# robot_PI4_F28379D_v1.net
KiCad netlist of a schematic drawn in EAGLE
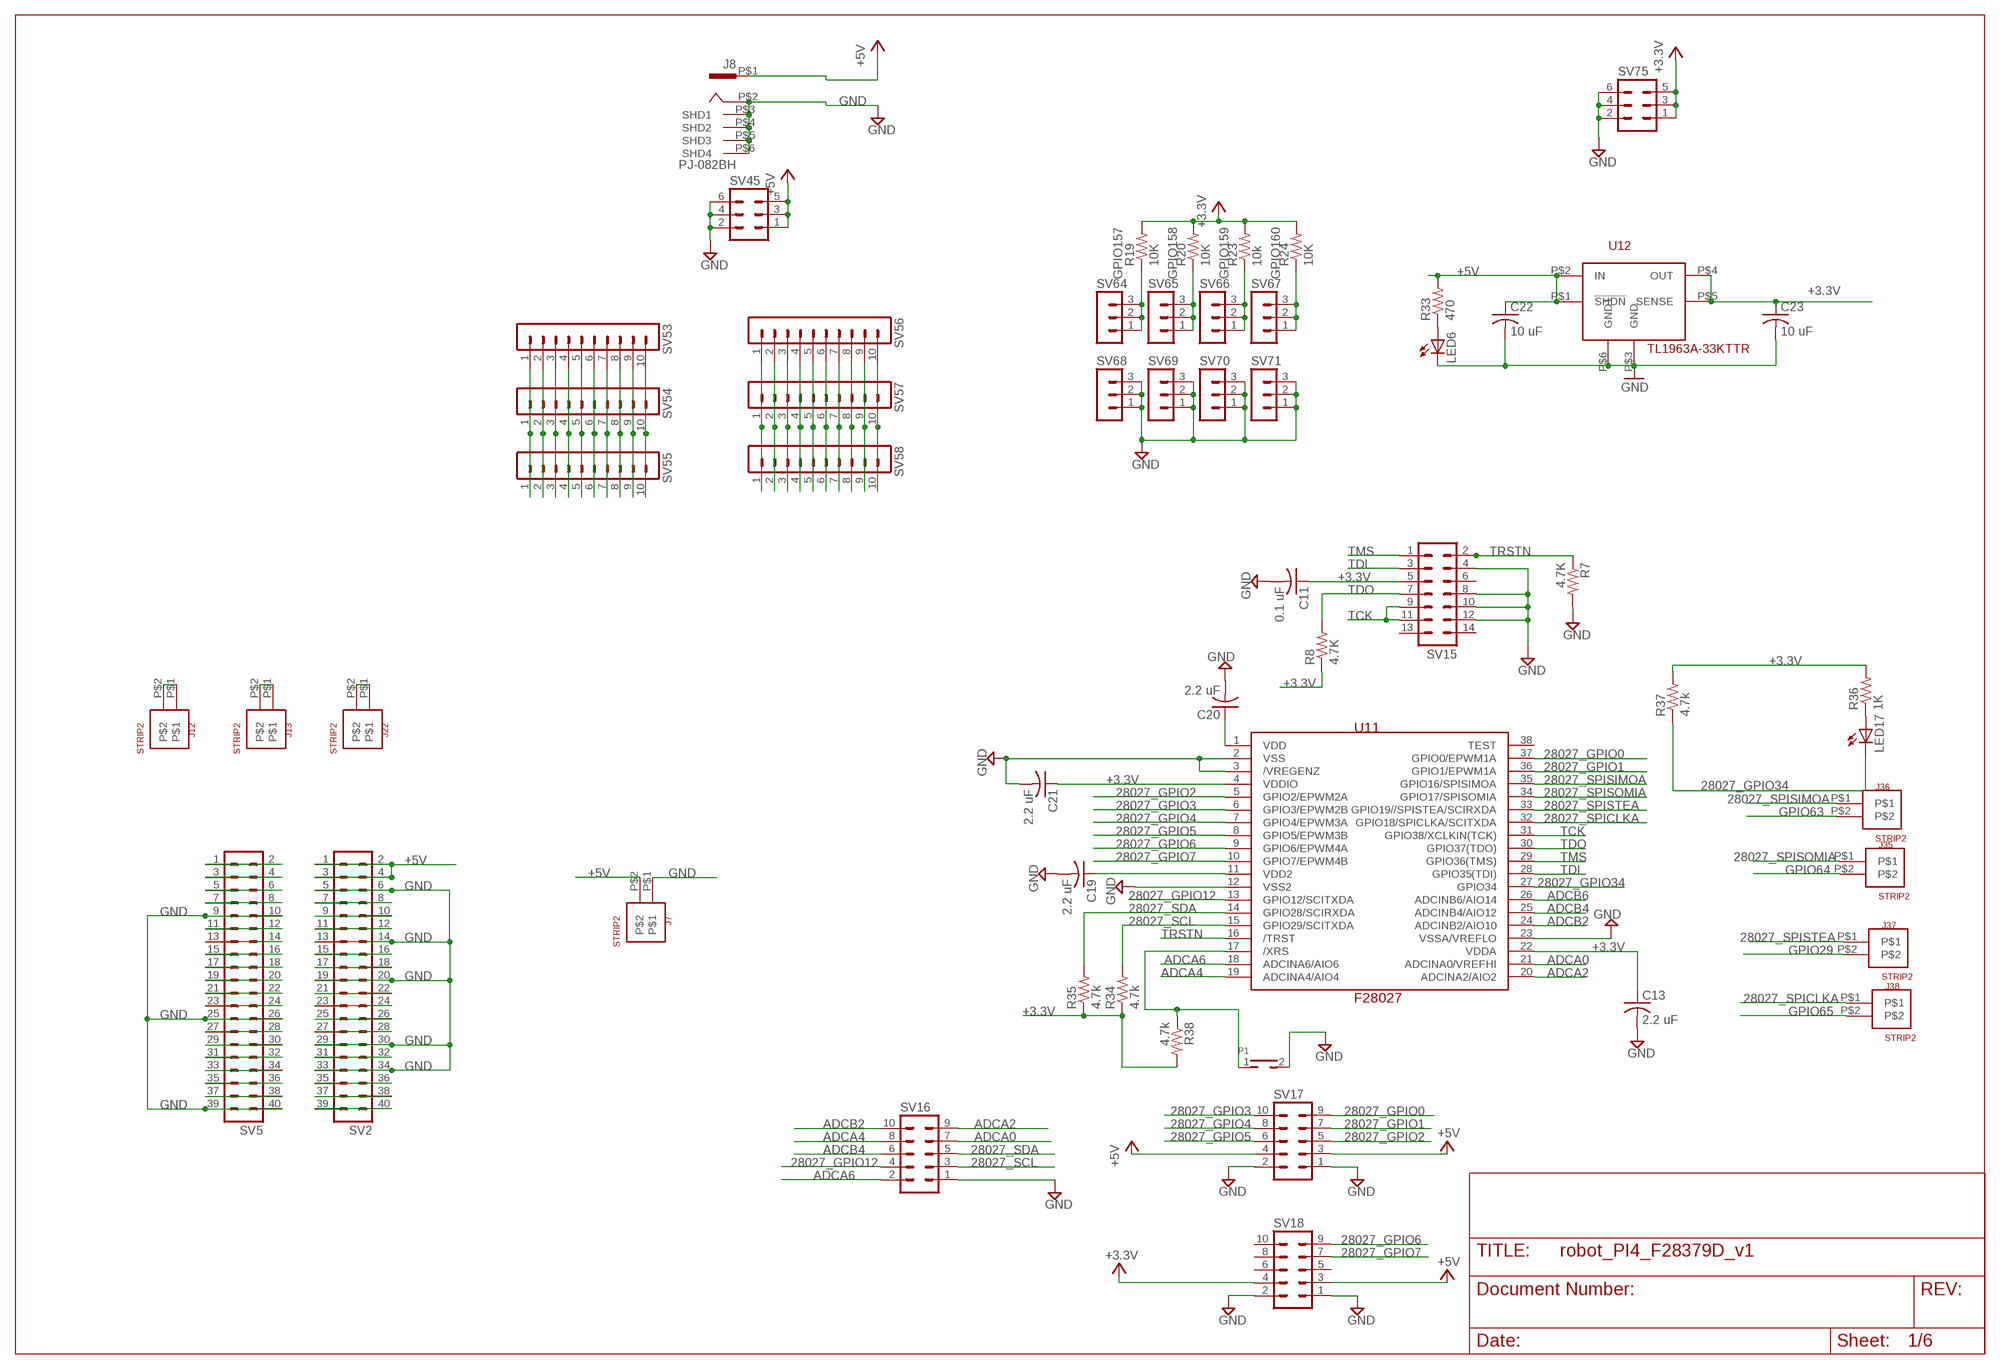
[diagram p0: schematic, sheet 1]
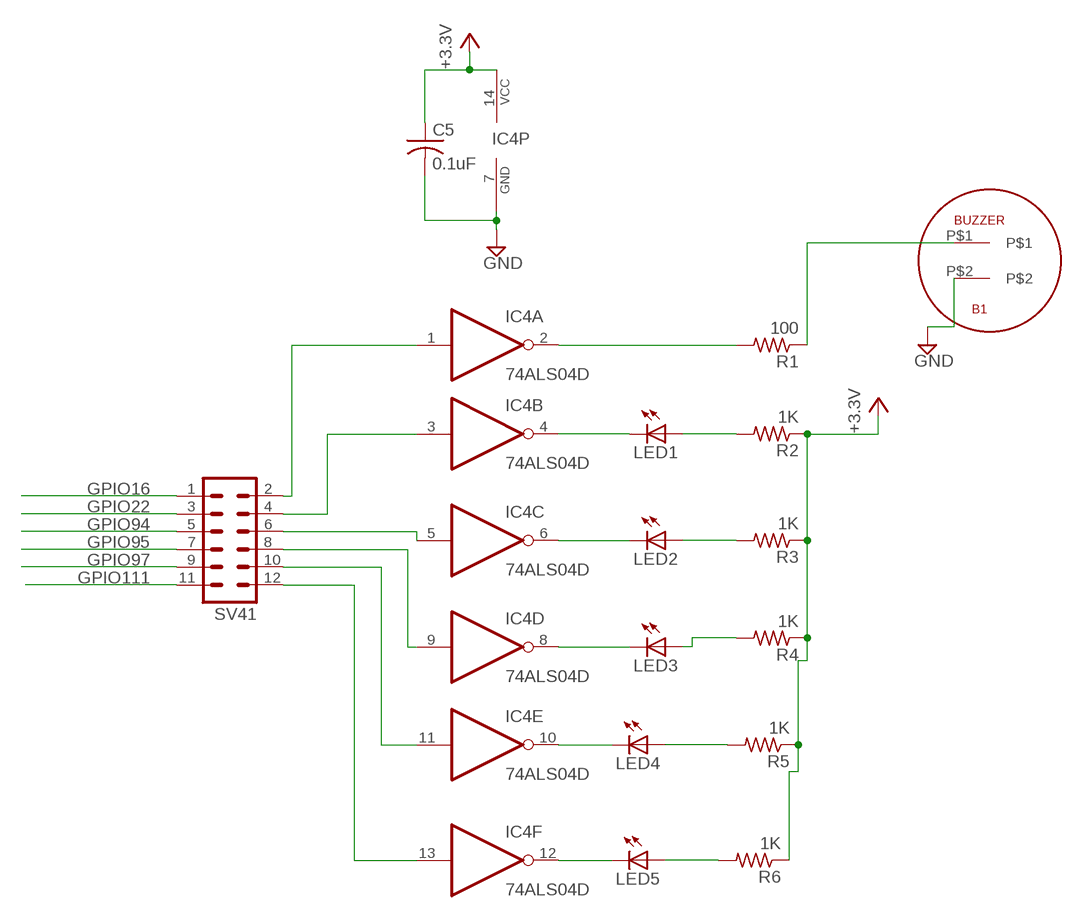
[diagram p1: schematic, sheet 2]
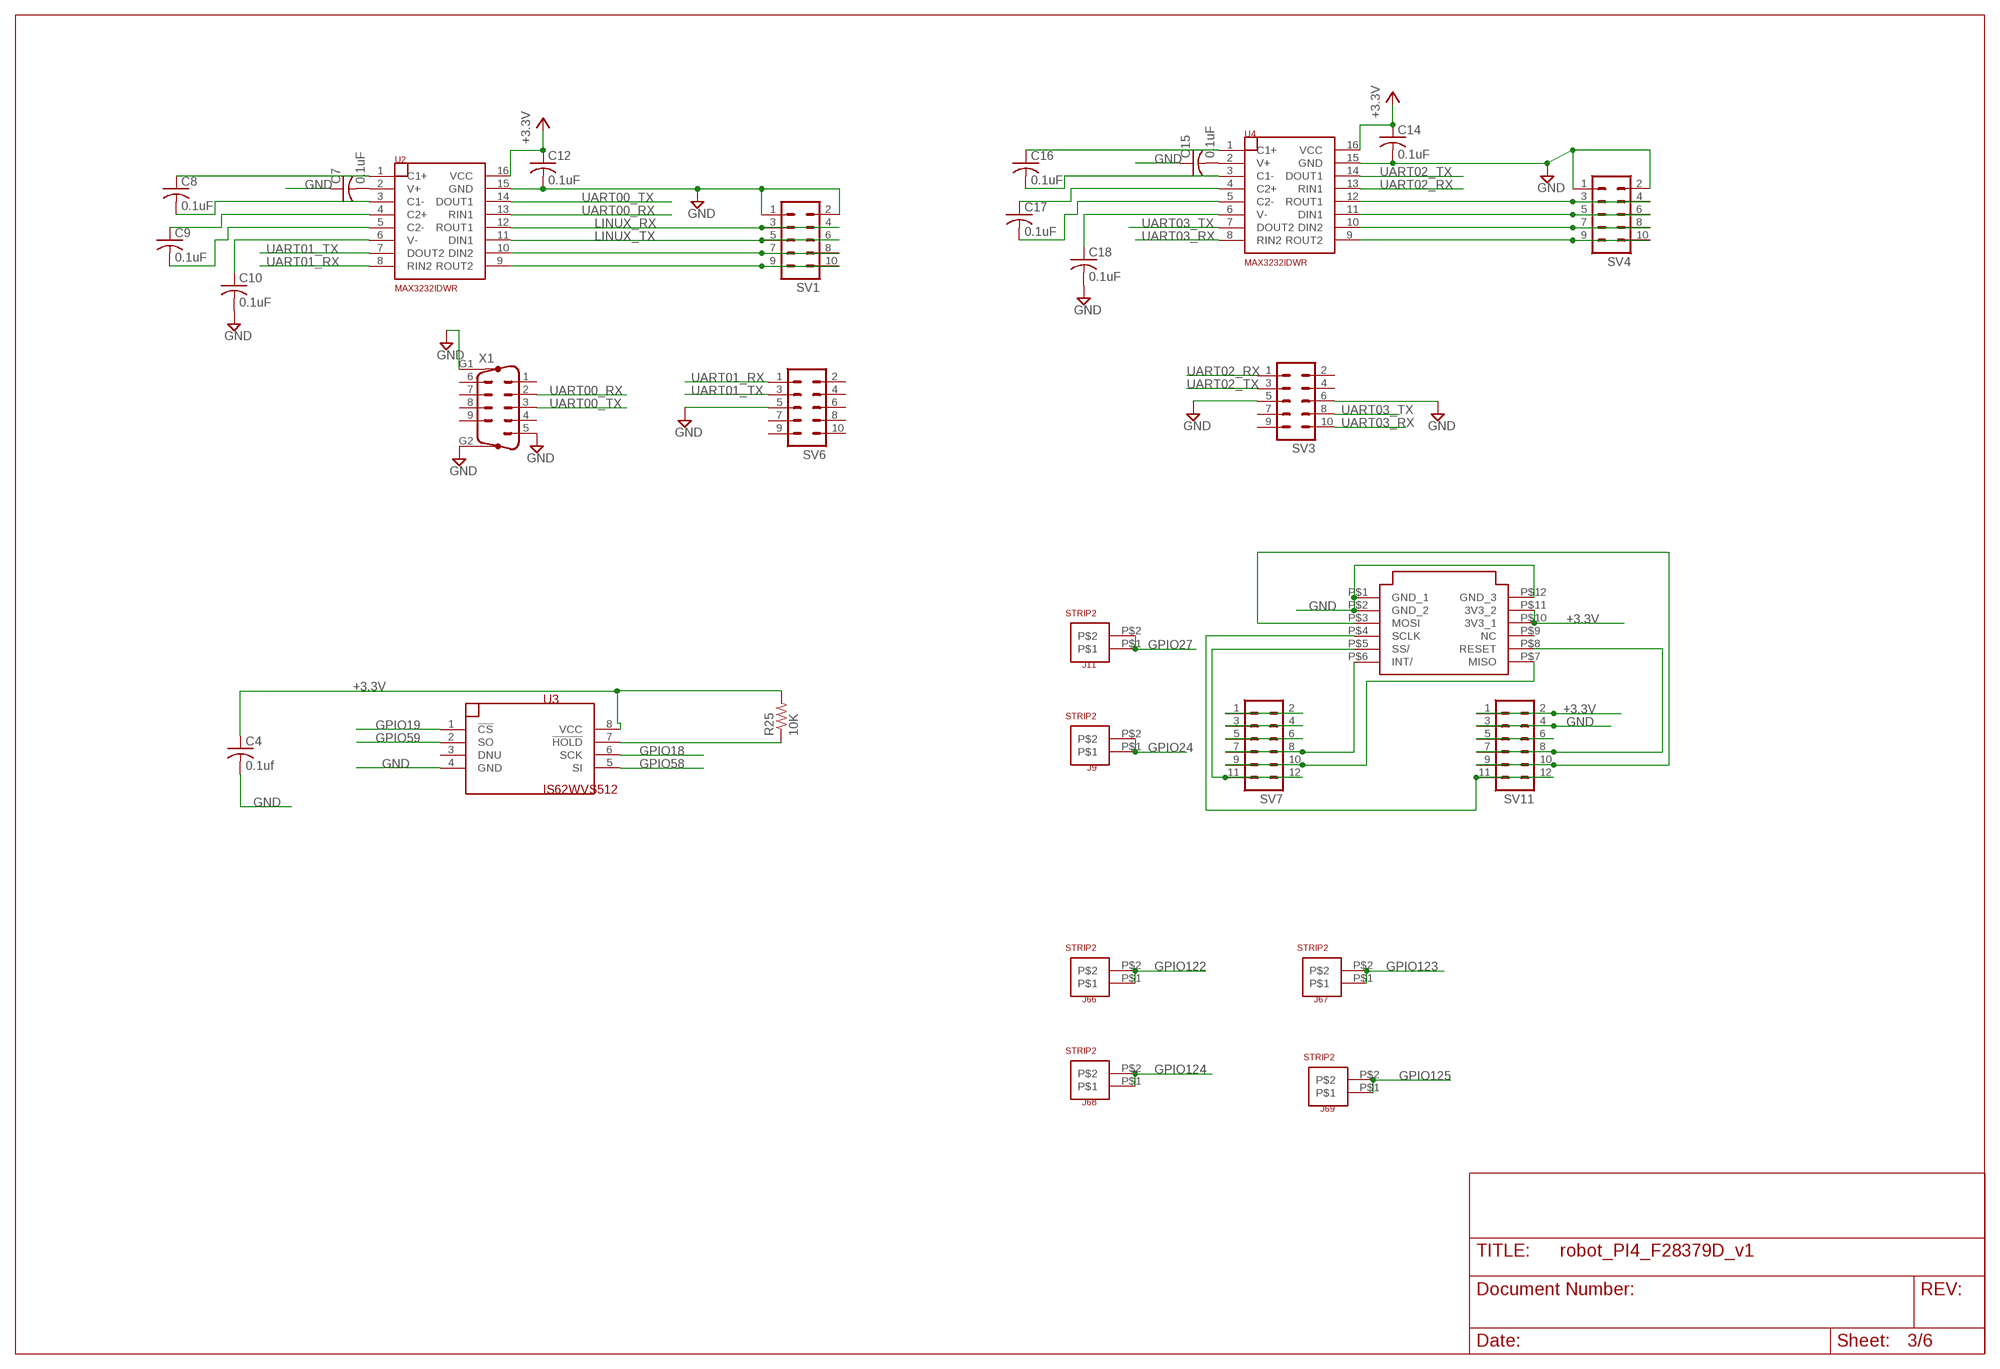
[diagram p2: schematic, sheet 3]
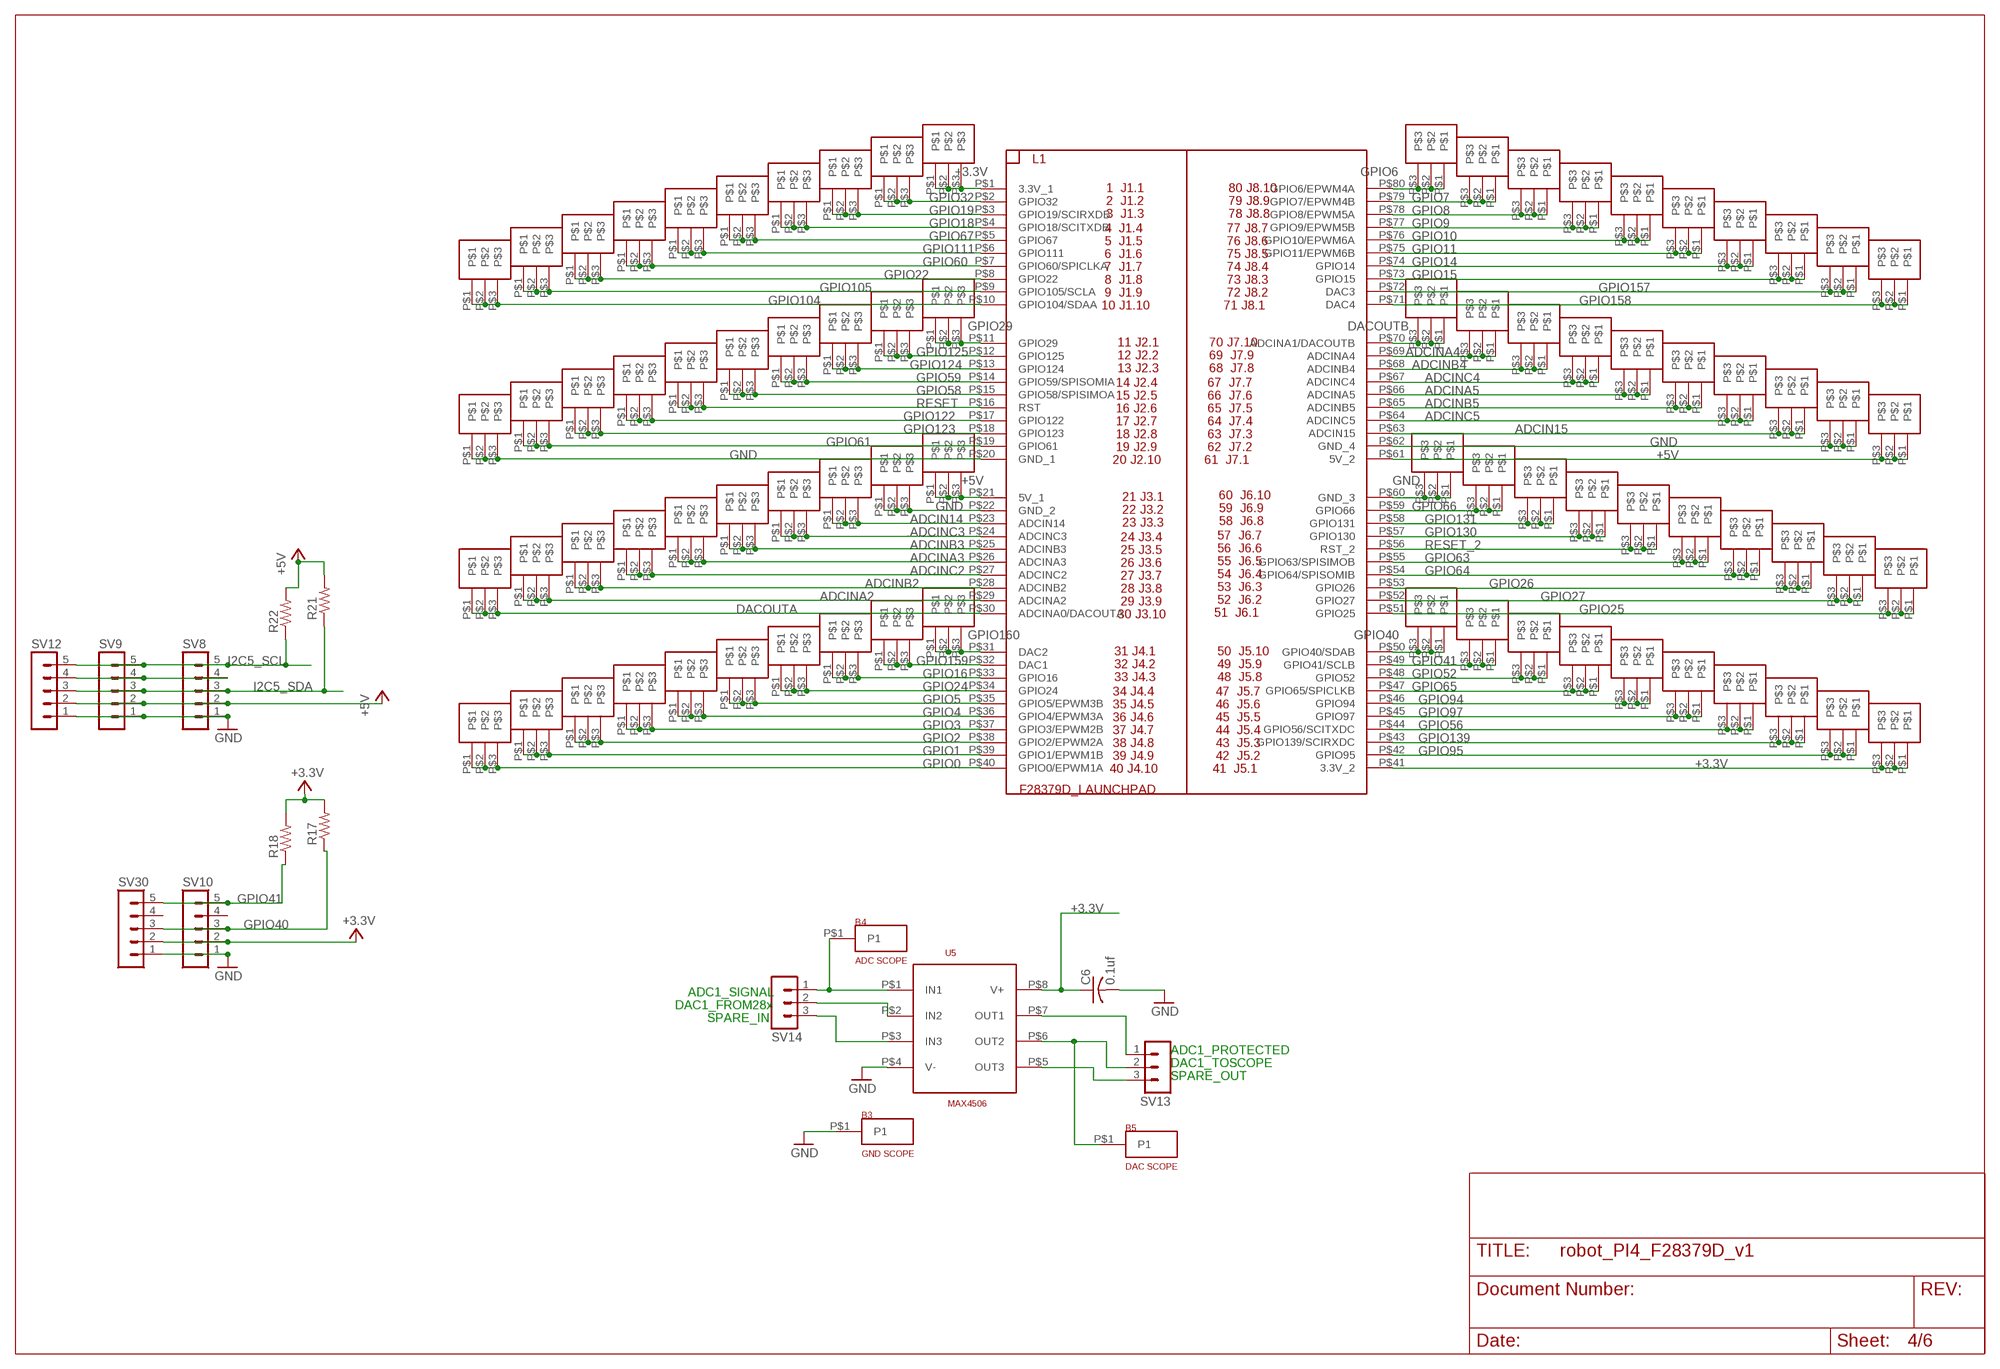
[diagram p3: schematic, sheet 4]
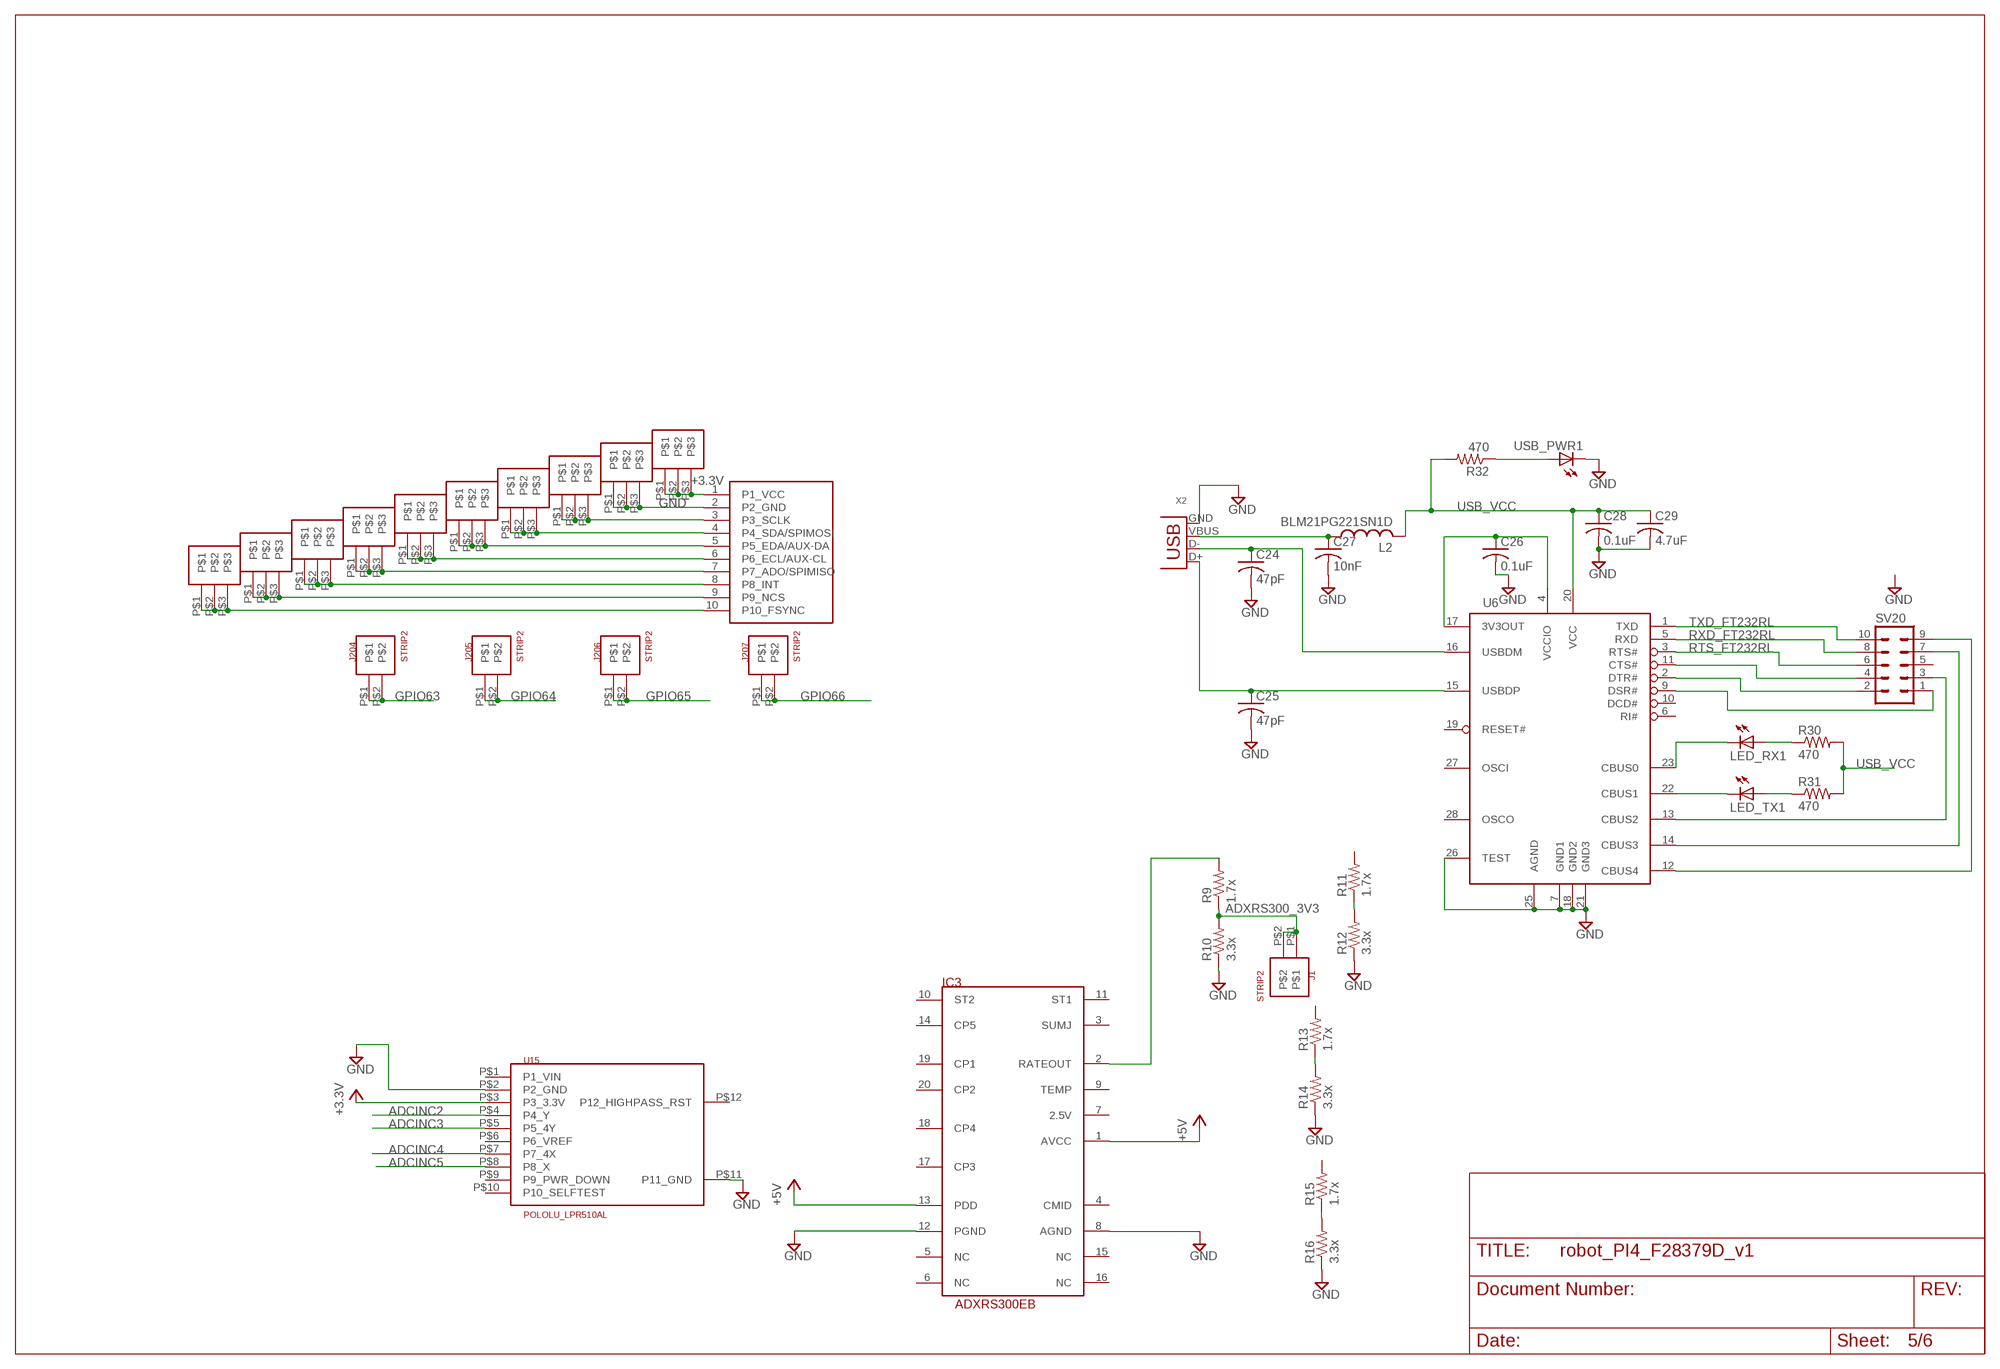
[diagram p4: schematic, sheet 5]
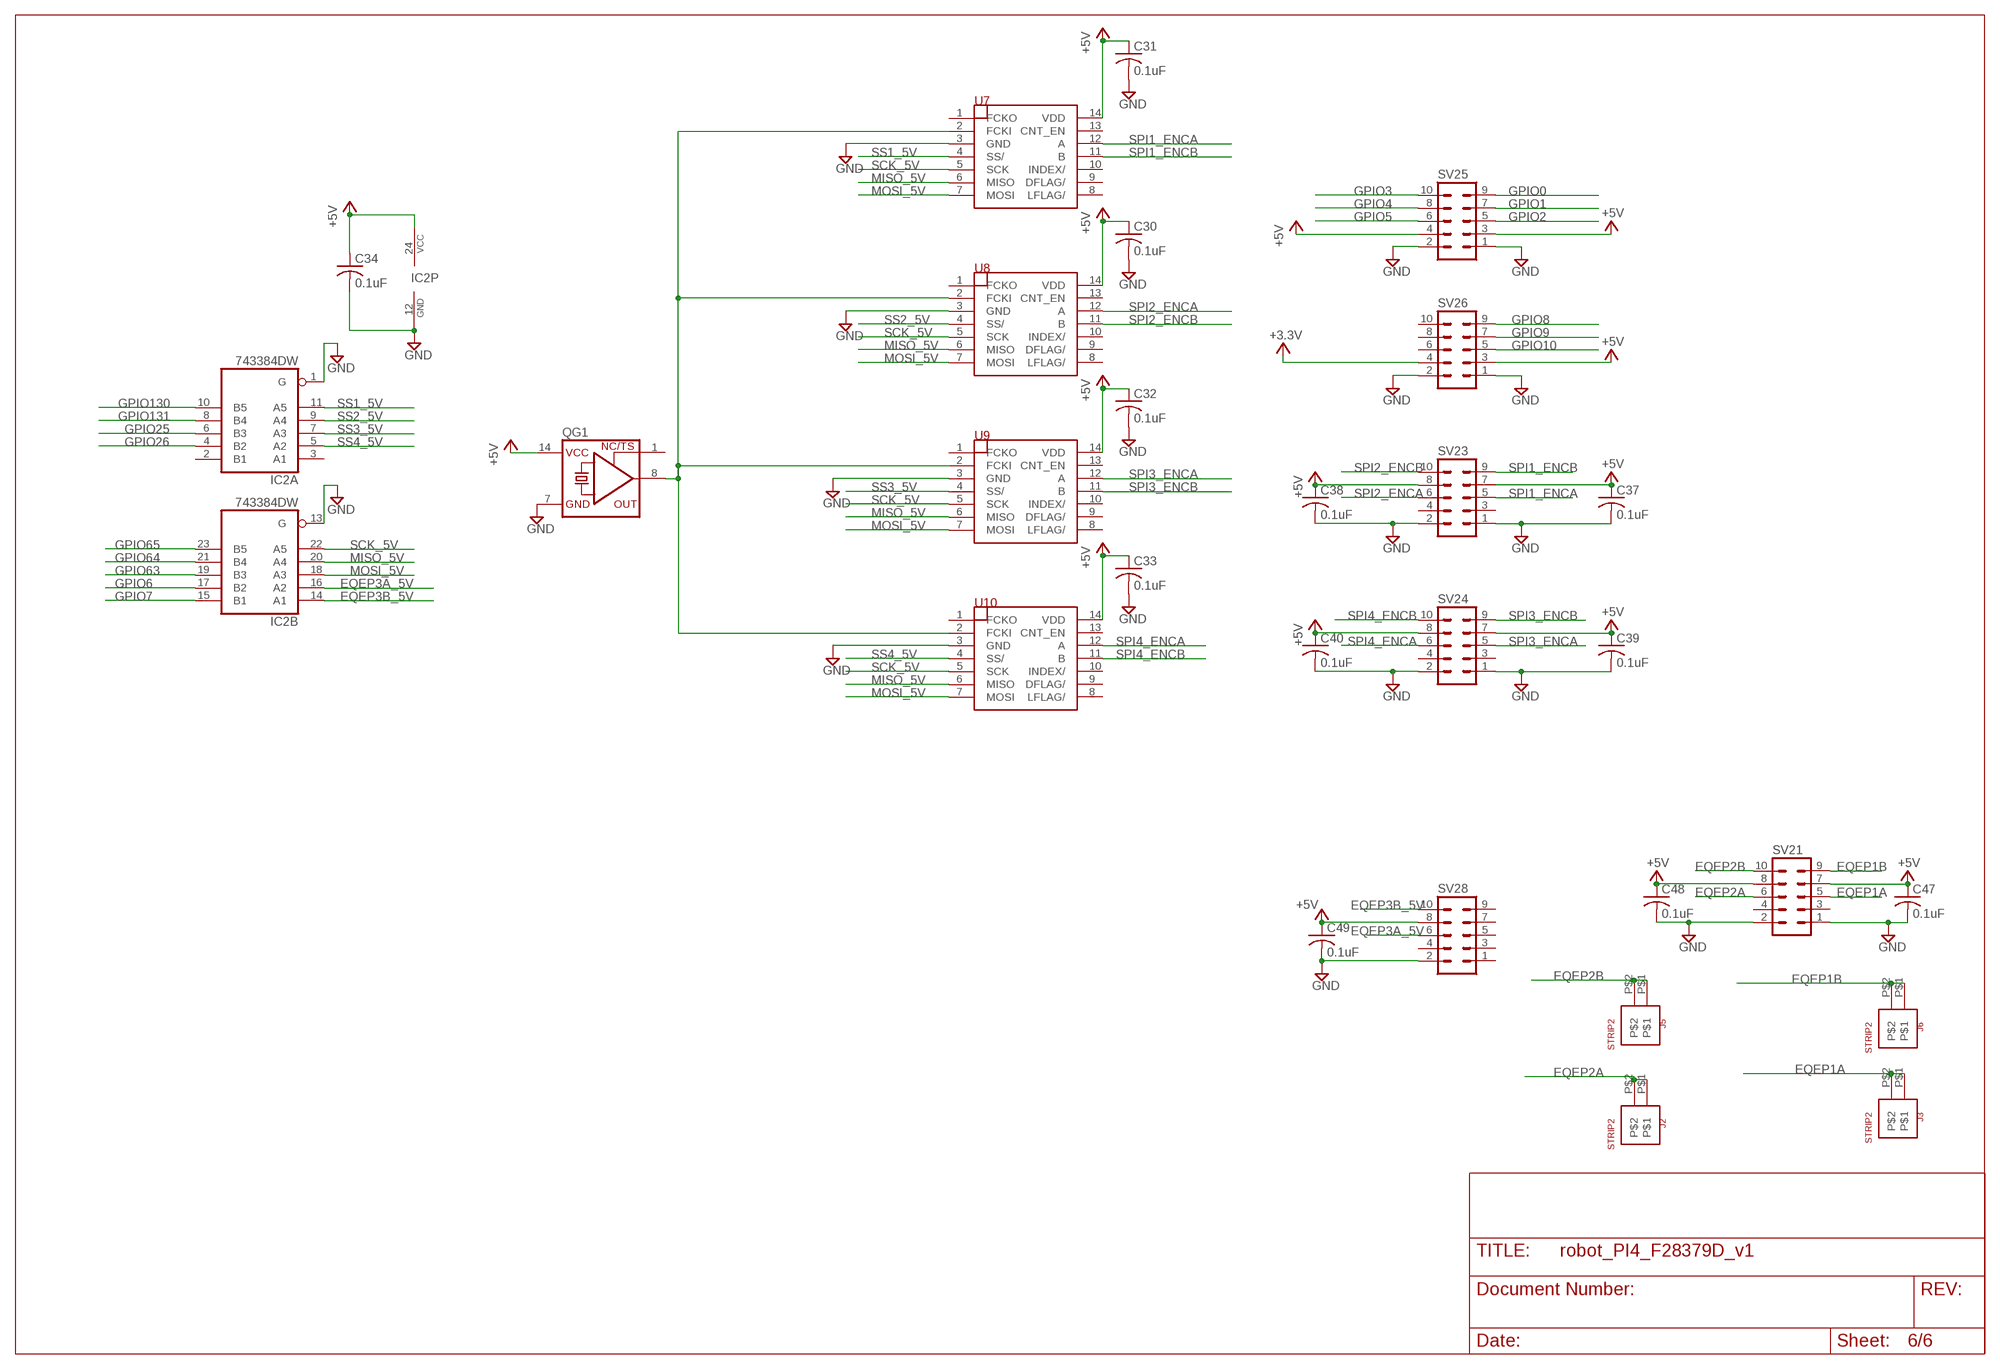
[diagram p5: schematic, sheet 6]

(export (version "E")
  (design (tool "Eeschema 10.0.6"))
  (components
    (comp (ref "C4")
      (value "0.1uf")
      (footprint "eagle-import:C1206")
      (libsource (lib "eagle-import") (part "C-USC1206"))
    )
    (comp (ref "C7")
      (value "0.1uF")
      (footprint "eagle-import:C0805K")
      (libsource (lib "eagle-import") (part "C-USC0805K"))
    )
    (comp (ref "C8")
      (value "0.1uF")
      (footprint "eagle-import:C0805K")
      (libsource (lib "eagle-import") (part "C-USC0805K"))
    )
    (comp (ref "C9")
      (value "0.1uF")
      (footprint "eagle-import:C0805K")
      (libsource (lib "eagle-import") (part "C-USC0805K"))
    )
    (comp (ref "C10")
      (value "0.1uF")
      (footprint "eagle-import:C0805K")
      (libsource (lib "eagle-import") (part "C-USC0805K"))
    )
    (comp (ref "C12")
      (value "0.1uF")
      (footprint "eagle-import:C0805K")
      (libsource (lib "eagle-import") (part "C-USC0805K"))
    )
    (comp (ref "C14")
      (value "0.1uF")
      (footprint "eagle-import:C0805K")
      (libsource (lib "eagle-import") (part "C-USC0805K"))
    )
    (comp (ref "C15")
      (value "0.1uF")
      (footprint "eagle-import:C0805K")
      (libsource (lib "eagle-import") (part "C-USC0805K"))
    )
    (comp (ref "C16")
      (value "0.1uF")
      (footprint "eagle-import:C0805K")
      (libsource (lib "eagle-import") (part "C-USC0805K"))
    )
    (comp (ref "C17")
      (value "0.1uF")
      (footprint "eagle-import:C0805K")
      (libsource (lib "eagle-import") (part "C-USC0805K"))
    )
    (comp (ref "C18")
      (value "0.1uF")
      (footprint "eagle-import:C0805K")
      (libsource (lib "eagle-import") (part "C-USC0805K"))
    )
    (comp (ref "ETH1")
      (value "USR_ES1_W5500")
      (footprint "eagle-import:USR_ES1_W5500")
      (libsource (lib "eagle-import") (part "USR_ES1_W5500"))
    )
    (comp (ref "J9")
      (value "STRIP2")
      (footprint "eagle-import:STRIP2")
      (libsource (lib "eagle-import") (part "STRIP2"))
    )
    (comp (ref "J11")
      (value "STRIP2")
      (footprint "eagle-import:STRIP2")
      (libsource (lib "eagle-import") (part "STRIP2"))
    )
    (comp (ref "J66")
      (value "STRIP2")
      (footprint "eagle-import:STRIP2")
      (libsource (lib "eagle-import") (part "STRIP2"))
    )
    (comp (ref "J67")
      (value "STRIP2")
      (footprint "eagle-import:STRIP2")
      (libsource (lib "eagle-import") (part "STRIP2"))
    )
    (comp (ref "J68")
      (value "STRIP2")
      (footprint "eagle-import:STRIP2")
      (libsource (lib "eagle-import") (part "STRIP2"))
    )
    (comp (ref "J69")
      (value "STRIP2")
      (footprint "eagle-import:STRIP2")
      (libsource (lib "eagle-import") (part "STRIP2"))
    )
    (comp (ref "R25")
      (value "10K")
      (footprint "eagle-import:M1206")
      (libsource (lib "eagle-import") (part "R-US_M1206"))
    )
    (comp (ref "SV1")
      (value "MA05-2")
      (footprint "eagle-import:MA05-2")
      (libsource (lib "eagle-import") (part "MA05-2"))
    )
    (comp (ref "SV3")
      (value "MA05-2")
      (footprint "eagle-import:MA05-2")
      (libsource (lib "eagle-import") (part "MA05-2"))
    )
    (comp (ref "SV4")
      (value "MA05-2")
      (footprint "eagle-import:MA05-2")
      (libsource (lib "eagle-import") (part "MA05-2"))
    )
    (comp (ref "SV6")
      (value "MA05-2")
      (footprint "eagle-import:MA05-2")
      (libsource (lib "eagle-import") (part "MA05-2"))
    )
    (comp (ref "SV7")
      (value "MA06-2")
      (footprint "eagle-import:MA06-2")
      (libsource (lib "eagle-import") (part "MA06-2"))
    )
    (comp (ref "SV11")
      (value "MA06-2")
      (footprint "eagle-import:MA06-2")
      (libsource (lib "eagle-import") (part "MA06-2"))
    )
    (comp (ref "U2")
      (value "MAX3232IDWR")
      (footprint "eagle-import:SO16W")
      (libsource (lib "eagle-import") (part "MAX3232IDWR"))
    )
    (comp (ref "U3")
      (value "IS62WVS512")
      (footprint "eagle-import:SO08")
      (libsource (lib "eagle-import") (part "IS62WVS512"))
    )
    (comp (ref "U4")
      (value "MAX3232IDWR")
      (footprint "eagle-import:SO16W")
      (libsource (lib "eagle-import") (part "MAX3232IDWR"))
    )
    (comp (ref "X1")
      (value "M09HP")
      (footprint "eagle-import:M09HP")
      (libsource (lib "eagle-import") (part "M09HP"))
    )
    (comp (ref "C24")
      (value "47pF")
      (footprint "eagle-import:C1206")
      (libsource (lib "eagle-import") (part "C-USC1206"))
    )
    (comp (ref "C25")
      (value "47pF")
      (footprint "eagle-import:C1206")
      (libsource (lib "eagle-import") (part "C-USC1206"))
    )
    (comp (ref "C26")
      (value "0.1uF")
      (footprint "eagle-import:C1206")
      (libsource (lib "eagle-import") (part "C-USC1206"))
    )
    (comp (ref "C27")
      (value "10nF")
      (footprint "eagle-import:C1206")
      (libsource (lib "eagle-import") (part "C-USC1206"))
    )
    (comp (ref "C28")
      (value "0.1uF")
      (footprint "eagle-import:C1206")
      (libsource (lib "eagle-import") (part "C-USC1206"))
    )
    (comp (ref "C29")
      (value "4.7uF")
      (footprint "eagle-import:C1206")
      (libsource (lib "eagle-import") (part "C-USC1206"))
    )
    (comp (ref "IC3")
      (value "ADXRS300EB")
      (footprint "eagle-import:DIL20")
      (libsource (lib "eagle-import") (part "ADXRS300EB"))
    )
    (comp (ref "J1")
      (value "STRIP2")
      (footprint "eagle-import:STRIP2")
      (libsource (lib "eagle-import") (part "STRIP2"))
    )
    (comp (ref "J123")
      (value "STRIP3")
      (footprint "eagle-import:STRIP3")
      (libsource (lib "eagle-import") (part "STRIP3"))
    )
    (comp (ref "J124")
      (value "STRIP3")
      (footprint "eagle-import:STRIP3")
      (libsource (lib "eagle-import") (part "STRIP3"))
    )
    (comp (ref "J125")
      (value "STRIP3")
      (footprint "eagle-import:STRIP3")
      (libsource (lib "eagle-import") (part "STRIP3"))
    )
    (comp (ref "J126")
      (value "STRIP3")
      (footprint "eagle-import:STRIP3")
      (libsource (lib "eagle-import") (part "STRIP3"))
    )
    (comp (ref "J127")
      (value "STRIP3")
      (footprint "eagle-import:STRIP3")
      (libsource (lib "eagle-import") (part "STRIP3"))
    )
    (comp (ref "J128")
      (value "STRIP3")
      (footprint "eagle-import:STRIP3")
      (libsource (lib "eagle-import") (part "STRIP3"))
    )
    (comp (ref "J129")
      (value "STRIP3")
      (footprint "eagle-import:STRIP3")
      (libsource (lib "eagle-import") (part "STRIP3"))
    )
    (comp (ref "J130")
      (value "STRIP3")
      (footprint "eagle-import:STRIP3")
      (libsource (lib "eagle-import") (part "STRIP3"))
    )
    (comp (ref "J131")
      (value "STRIP3")
      (footprint "eagle-import:STRIP3")
      (libsource (lib "eagle-import") (part "STRIP3"))
    )
    (comp (ref "J132")
      (value "STRIP3")
      (footprint "eagle-import:STRIP3")
      (libsource (lib "eagle-import") (part "STRIP3"))
    )
    (comp (ref "J204")
      (value "STRIP2")
      (footprint "eagle-import:STRIP2")
      (libsource (lib "eagle-import") (part "STRIP2"))
    )
    (comp (ref "J205")
      (value "STRIP2")
      (footprint "eagle-import:STRIP2")
      (libsource (lib "eagle-import") (part "STRIP2"))
    )
    (comp (ref "J206")
      (value "STRIP2")
      (footprint "eagle-import:STRIP2")
      (libsource (lib "eagle-import") (part "STRIP2"))
    )
    (comp (ref "J207")
      (value "STRIP2")
      (footprint "eagle-import:STRIP2")
      (libsource (lib "eagle-import") (part "STRIP2"))
    )
    (comp (ref "L2")
      (value "BLM21PG221SN1D")
      (footprint "eagle-import:L0805")
      (libsource (lib "eagle-import") (part "L-USL0805"))
    )
    (comp (ref "LED_RX1")
      (value "LED3MM")
      (footprint "eagle-import:LED3MM")
      (libsource (lib "eagle-import") (part "LED3MM"))
    )
    (comp (ref "LED_TX1")
      (value "LED3MM")
      (footprint "eagle-import:LED3MM")
      (libsource (lib "eagle-import") (part "LED3MM"))
    )
    (comp (ref "R9")
      (value "1.7x")
      (footprint "eagle-import:M1206")
      (libsource (lib "eagle-import") (part "R-US_M1206"))
    )
    (comp (ref "R10")
      (value "3.3x")
      (footprint "eagle-import:M1206")
      (libsource (lib "eagle-import") (part "R-US_M1206"))
    )
    (comp (ref "R11")
      (value "1.7x")
      (footprint "eagle-import:M1206")
      (libsource (lib "eagle-import") (part "R-US_M1206"))
    )
    (comp (ref "R12")
      (value "3.3x")
      (footprint "eagle-import:M1206")
      (libsource (lib "eagle-import") (part "R-US_M1206"))
    )
    (comp (ref "R13")
      (value "1.7x")
      (footprint "eagle-import:M1206")
      (libsource (lib "eagle-import") (part "R-US_M1206"))
    )
    (comp (ref "R14")
      (value "3.3x")
      (footprint "eagle-import:M1206")
      (libsource (lib "eagle-import") (part "R-US_M1206"))
    )
    (comp (ref "R15")
      (value "1.7x")
      (footprint "eagle-import:M1206")
      (libsource (lib "eagle-import") (part "R-US_M1206"))
    )
    (comp (ref "R16")
      (value "3.3x")
      (footprint "eagle-import:M1206")
      (libsource (lib "eagle-import") (part "R-US_M1206"))
    )
    (comp (ref "R30")
      (value "470")
      (footprint "eagle-import:M1206")
      (libsource (lib "eagle-import") (part "R-US_M1206"))
    )
    (comp (ref "R31")
      (value "470")
      (footprint "eagle-import:M1206")
      (libsource (lib "eagle-import") (part "R-US_M1206"))
    )
    (comp (ref "R32")
      (value "470")
      (footprint "eagle-import:M1206")
      (libsource (lib "eagle-import") (part "R-US_M1206"))
    )
    (comp (ref "SV20")
      (value "MA05-2")
      (footprint "eagle-import:MA05-2")
      (libsource (lib "eagle-import") (part "MA05-2"))
    )
    (comp (ref "U$1")
      (value "MPU-9250-BB")
      (footprint "eagle-import:MPU-9250-BB")
      (libsource (lib "eagle-import") (part "MPU-9250-BB"))
    )
    (comp (ref "U6")
      (value "FT232RL")
      (footprint "eagle-import:SSOP28DB")
      (libsource (lib "eagle-import") (part "FT232RL"))
    )
    (comp (ref "U15")
      (value "POLOLU_LPR510AL")
      (footprint "eagle-import:POLOLU_LPR510AL")
      (libsource (lib "eagle-import") (part "POLOLU_LPR510AL"))
    )
    (comp (ref "USB_PWR1")
      (value "LED3MM")
      (footprint "eagle-import:LED3MM")
      (libsource (lib "eagle-import") (part "LED3MM"))
    )
    (comp (ref "X2")
      (value "USB-B-H")
      (footprint "eagle-import:USB-B-H")
      (libsource (lib "eagle-import") (part "USB-B-H"))
    )
    (comp (ref "C30")
      (value "0.1uF")
      (footprint "eagle-import:C1206")
      (libsource (lib "eagle-import") (part "C-USC1206"))
    )
    (comp (ref "C31")
      (value "0.1uF")
      (footprint "eagle-import:C1206")
      (libsource (lib "eagle-import") (part "C-USC1206"))
    )
    (comp (ref "C32")
      (value "0.1uF")
      (footprint "eagle-import:C1206")
      (libsource (lib "eagle-import") (part "C-USC1206"))
    )
    (comp (ref "C33")
      (value "0.1uF")
      (footprint "eagle-import:C1206")
      (libsource (lib "eagle-import") (part "C-USC1206"))
    )
    (comp (ref "C34")
      (value "0.1uF")
      (footprint "eagle-import:C1206")
      (libsource (lib "eagle-import") (part "C-USC1206"))
    )
    (comp (ref "C37")
      (value "0.1uF")
      (footprint "eagle-import:C1206")
      (libsource (lib "eagle-import") (part "C-USC1206"))
    )
    (comp (ref "C38")
      (value "0.1uF")
      (footprint "eagle-import:C1206")
      (libsource (lib "eagle-import") (part "C-USC1206"))
    )
    (comp (ref "C39")
      (value "0.1uF")
      (footprint "eagle-import:C1206")
      (libsource (lib "eagle-import") (part "C-USC1206"))
    )
    (comp (ref "C40")
      (value "0.1uF")
      (footprint "eagle-import:C1206")
      (libsource (lib "eagle-import") (part "C-USC1206"))
    )
    (comp (ref "C47")
      (value "0.1uF")
      (footprint "eagle-import:C1206")
      (libsource (lib "eagle-import") (part "C-USC1206"))
    )
    (comp (ref "C48")
      (value "0.1uF")
      (footprint "eagle-import:C1206")
      (libsource (lib "eagle-import") (part "C-USC1206"))
    )
    (comp (ref "C49")
      (value "0.1uF")
      (footprint "eagle-import:C1206")
      (libsource (lib "eagle-import") (part "C-USC1206"))
    )
    (comp (ref "IC2")
      (value "743384DW")
      (footprint "eagle-import:SO24W")
      (libsource (lib "eagle-import") (part "743384DW"))
    )
    (comp (ref "J2")
      (value "STRIP2")
      (footprint "eagle-import:STRIP2")
      (libsource (lib "eagle-import") (part "STRIP2"))
    )
    (comp (ref "J3")
      (value "STRIP2")
      (footprint "eagle-import:STRIP2")
      (libsource (lib "eagle-import") (part "STRIP2"))
    )
    (comp (ref "J5")
      (value "STRIP2")
      (footprint "eagle-import:STRIP2")
      (libsource (lib "eagle-import") (part "STRIP2"))
    )
    (comp (ref "J6")
      (value "STRIP2")
      (footprint "eagle-import:STRIP2")
      (libsource (lib "eagle-import") (part "STRIP2"))
    )
    (comp (ref "QG1")
      (value "XO-14")
      (footprint "eagle-import:DIL14S")
      (libsource (lib "eagle-import") (part "XO-14"))
    )
    (comp (ref "SV21")
      (value "MA05-2")
      (footprint "eagle-import:MA05-2")
      (libsource (lib "eagle-import") (part "MA05-2"))
    )
    (comp (ref "SV23")
      (value "MA05-2")
      (footprint "eagle-import:MA05-2")
      (libsource (lib "eagle-import") (part "MA05-2"))
    )
    (comp (ref "SV24")
      (value "MA05-2")
      (footprint "eagle-import:MA05-2")
      (libsource (lib "eagle-import") (part "MA05-2"))
    )
    (comp (ref "SV25")
      (value "MA05-2")
      (footprint "eagle-import:MA05-2")
      (libsource (lib "eagle-import") (part "MA05-2"))
    )
    (comp (ref "SV26")
      (value "MA05-2")
      (footprint "eagle-import:MA05-2")
      (libsource (lib "eagle-import") (part "MA05-2"))
    )
    (comp (ref "SV28")
      (value "MA05-2")
      (footprint "eagle-import:MA05-2")
      (libsource (lib "eagle-import") (part "MA05-2"))
    )
    (comp (ref "U7")
      (value "LS7366R")
      (footprint "eagle-import:SO14")
      (libsource (lib "eagle-import") (part "LS7366R"))
    )
    (comp (ref "U8")
      (value "LS7366R")
      (footprint "eagle-import:SO14")
      (libsource (lib "eagle-import") (part "LS7366R"))
    )
    (comp (ref "U9")
      (value "LS7366R")
      (footprint "eagle-import:SO14")
      (libsource (lib "eagle-import") (part "LS7366R"))
    )
    (comp (ref "U10")
      (value "LS7366R")
      (footprint "eagle-import:SO14")
      (libsource (lib "eagle-import") (part "LS7366R"))
    )
    (comp (ref "B3")
      (value "GND SCOPE")
      (footprint "eagle-import:BANANA_MALE")
      (libsource (lib "eagle-import") (part "BANANA_MALE"))
    )
    (comp (ref "B4")
      (value "ADC SCOPE")
      (footprint "eagle-import:BANANA_MALE")
      (libsource (lib "eagle-import") (part "BANANA_MALE"))
    )
    (comp (ref "B5")
      (value "DAC SCOPE")
      (footprint "eagle-import:BANANA_MALE")
      (libsource (lib "eagle-import") (part "BANANA_MALE"))
    )
    (comp (ref "C6")
      (value "0.1uf")
      (footprint "eagle-import:C1206")
      (libsource (lib "eagle-import") (part "C-USC1206"))
    )
    (comp (ref "J10")
      (value "STRIP3")
      (footprint "eagle-import:STRIP3")
      (libsource (lib "eagle-import") (part "STRIP3"))
    )
    (comp (ref "J14")
      (value "STRIP3")
      (footprint "eagle-import:STRIP3")
      (libsource (lib "eagle-import") (part "STRIP3"))
    )
    (comp (ref "J15")
      (value "STRIP3")
      (footprint "eagle-import:STRIP3")
      (libsource (lib "eagle-import") (part "STRIP3"))
    )
    (comp (ref "J16")
      (value "STRIP3")
      (footprint "eagle-import:STRIP3")
      (libsource (lib "eagle-import") (part "STRIP3"))
    )
    (comp (ref "J17")
      (value "STRIP3")
      (footprint "eagle-import:STRIP3")
      (libsource (lib "eagle-import") (part "STRIP3"))
    )
    (comp (ref "J18")
      (value "STRIP3")
      (footprint "eagle-import:STRIP3")
      (libsource (lib "eagle-import") (part "STRIP3"))
    )
    (comp (ref "J19")
      (value "STRIP3")
      (footprint "eagle-import:STRIP3")
      (libsource (lib "eagle-import") (part "STRIP3"))
    )
    (comp (ref "J20")
      (value "STRIP3")
      (footprint "eagle-import:STRIP3")
      (libsource (lib "eagle-import") (part "STRIP3"))
    )
    (comp (ref "J21")
      (value "STRIP3")
      (footprint "eagle-import:STRIP3")
      (libsource (lib "eagle-import") (part "STRIP3"))
    )
    (comp (ref "J28")
      (value "STRIP3")
      (footprint "eagle-import:STRIP3")
      (libsource (lib "eagle-import") (part "STRIP3"))
    )
    (comp (ref "J29")
      (value "STRIP3")
      (footprint "eagle-import:STRIP3")
      (libsource (lib "eagle-import") (part "STRIP3"))
    )
    (comp (ref "J30")
      (value "STRIP3")
      (footprint "eagle-import:STRIP3")
      (libsource (lib "eagle-import") (part "STRIP3"))
    )
    (comp (ref "J31")
      (value "STRIP3")
      (footprint "eagle-import:STRIP3")
      (libsource (lib "eagle-import") (part "STRIP3"))
    )
    (comp (ref "J32")
      (value "STRIP3")
      (footprint "eagle-import:STRIP3")
      (libsource (lib "eagle-import") (part "STRIP3"))
    )
    (comp (ref "J33")
      (value "STRIP3")
      (footprint "eagle-import:STRIP3")
      (libsource (lib "eagle-import") (part "STRIP3"))
    )
    (comp (ref "J98")
      (value "STRIP3")
      (footprint "eagle-import:STRIP3")
      (libsource (lib "eagle-import") (part "STRIP3"))
    )
    (comp (ref "J99")
      (value "STRIP3")
      (footprint "eagle-import:STRIP3")
      (libsource (lib "eagle-import") (part "STRIP3"))
    )
    (comp (ref "J100")
      (value "STRIP3")
      (footprint "eagle-import:STRIP3")
      (libsource (lib "eagle-import") (part "STRIP3"))
    )
    (comp (ref "J101")
      (value "STRIP3")
      (footprint "eagle-import:STRIP3")
      (libsource (lib "eagle-import") (part "STRIP3"))
    )
    (comp (ref "J102")
      (value "STRIP3")
      (footprint "eagle-import:STRIP3")
      (libsource (lib "eagle-import") (part "STRIP3"))
    )
    (comp (ref "J103")
      (value "STRIP3")
      (footprint "eagle-import:STRIP3")
      (libsource (lib "eagle-import") (part "STRIP3"))
    )
    (comp (ref "J104")
      (value "STRIP3")
      (footprint "eagle-import:STRIP3")
      (libsource (lib "eagle-import") (part "STRIP3"))
    )
    (comp (ref "J105")
      (value "STRIP3")
      (footprint "eagle-import:STRIP3")
      (libsource (lib "eagle-import") (part "STRIP3"))
    )
    (comp (ref "J106")
      (value "STRIP3")
      (footprint "eagle-import:STRIP3")
      (libsource (lib "eagle-import") (part "STRIP3"))
    )
    (comp (ref "J107")
      (value "STRIP3")
      (footprint "eagle-import:STRIP3")
      (libsource (lib "eagle-import") (part "STRIP3"))
    )
    (comp (ref "J108")
      (value "STRIP3")
      (footprint "eagle-import:STRIP3")
      (libsource (lib "eagle-import") (part "STRIP3"))
    )
    (comp (ref "J109")
      (value "STRIP3")
      (footprint "eagle-import:STRIP3")
      (libsource (lib "eagle-import") (part "STRIP3"))
    )
    (comp (ref "J110")
      (value "STRIP3")
      (footprint "eagle-import:STRIP3")
      (libsource (lib "eagle-import") (part "STRIP3"))
    )
    (comp (ref "J111")
      (value "STRIP3")
      (footprint "eagle-import:STRIP3")
      (libsource (lib "eagle-import") (part "STRIP3"))
    )
    (comp (ref "J112")
      (value "STRIP3")
      (footprint "eagle-import:STRIP3")
      (libsource (lib "eagle-import") (part "STRIP3"))
    )
    (comp (ref "J113")
      (value "STRIP3")
      (footprint "eagle-import:STRIP3")
      (libsource (lib "eagle-import") (part "STRIP3"))
    )
    (comp (ref "J114")
      (value "STRIP3")
      (footprint "eagle-import:STRIP3")
      (libsource (lib "eagle-import") (part "STRIP3"))
    )
    (comp (ref "J115")
      (value "STRIP3")
      (footprint "eagle-import:STRIP3")
      (libsource (lib "eagle-import") (part "STRIP3"))
    )
    (comp (ref "J116")
      (value "STRIP3")
      (footprint "eagle-import:STRIP3")
      (libsource (lib "eagle-import") (part "STRIP3"))
    )
    (comp (ref "J117")
      (value "STRIP3")
      (footprint "eagle-import:STRIP3")
      (libsource (lib "eagle-import") (part "STRIP3"))
    )
    (comp (ref "J118")
      (value "STRIP3")
      (footprint "eagle-import:STRIP3")
      (libsource (lib "eagle-import") (part "STRIP3"))
    )
    (comp (ref "J119")
      (value "STRIP3")
      (footprint "eagle-import:STRIP3")
      (libsource (lib "eagle-import") (part "STRIP3"))
    )
    (comp (ref "J120")
      (value "STRIP3")
      (footprint "eagle-import:STRIP3")
      (libsource (lib "eagle-import") (part "STRIP3"))
    )
    (comp (ref "J121")
      (value "STRIP3")
      (footprint "eagle-import:STRIP3")
      (libsource (lib "eagle-import") (part "STRIP3"))
    )
    (comp (ref "J122")
      (value "STRIP3")
      (footprint "eagle-import:STRIP3")
      (libsource (lib "eagle-import") (part "STRIP3"))
    )
    (comp (ref "J133")
      (value "STRIP3")
      (footprint "eagle-import:STRIP3")
      (libsource (lib "eagle-import") (part "STRIP3"))
    )
    (comp (ref "J134")
      (value "STRIP3")
      (footprint "eagle-import:STRIP3")
      (libsource (lib "eagle-import") (part "STRIP3"))
    )
    (comp (ref "J135")
      (value "STRIP3")
      (footprint "eagle-import:STRIP3")
      (libsource (lib "eagle-import") (part "STRIP3"))
    )
    (comp (ref "J136")
      (value "STRIP3")
      (footprint "eagle-import:STRIP3")
      (libsource (lib "eagle-import") (part "STRIP3"))
    )
    (comp (ref "J137")
      (value "STRIP3")
      (footprint "eagle-import:STRIP3")
      (libsource (lib "eagle-import") (part "STRIP3"))
    )
    (comp (ref "J138")
      (value "STRIP3")
      (footprint "eagle-import:STRIP3")
      (libsource (lib "eagle-import") (part "STRIP3"))
    )
    (comp (ref "J139")
      (value "STRIP3")
      (footprint "eagle-import:STRIP3")
      (libsource (lib "eagle-import") (part "STRIP3"))
    )
    (comp (ref "J140")
      (value "STRIP3")
      (footprint "eagle-import:STRIP3")
      (libsource (lib "eagle-import") (part "STRIP3"))
    )
    (comp (ref "J141")
      (value "STRIP3")
      (footprint "eagle-import:STRIP3")
      (libsource (lib "eagle-import") (part "STRIP3"))
    )
    (comp (ref "J142")
      (value "STRIP3")
      (footprint "eagle-import:STRIP3")
      (libsource (lib "eagle-import") (part "STRIP3"))
    )
    (comp (ref "J143")
      (value "STRIP3")
      (footprint "eagle-import:STRIP3")
      (libsource (lib "eagle-import") (part "STRIP3"))
    )
    (comp (ref "J144")
      (value "STRIP3")
      (footprint "eagle-import:STRIP3")
      (libsource (lib "eagle-import") (part "STRIP3"))
    )
    (comp (ref "J145")
      (value "STRIP3")
      (footprint "eagle-import:STRIP3")
      (libsource (lib "eagle-import") (part "STRIP3"))
    )
    (comp (ref "J146")
      (value "STRIP3")
      (footprint "eagle-import:STRIP3")
      (libsource (lib "eagle-import") (part "STRIP3"))
    )
    (comp (ref "J147")
      (value "STRIP3")
      (footprint "eagle-import:STRIP3")
      (libsource (lib "eagle-import") (part "STRIP3"))
    )
    (comp (ref "J148")
      (value "STRIP3")
      (footprint "eagle-import:STRIP3")
      (libsource (lib "eagle-import") (part "STRIP3"))
    )
    (comp (ref "J149")
      (value "STRIP3")
      (footprint "eagle-import:STRIP3")
      (libsource (lib "eagle-import") (part "STRIP3"))
    )
    (comp (ref "J150")
      (value "STRIP3")
      (footprint "eagle-import:STRIP3")
      (libsource (lib "eagle-import") (part "STRIP3"))
    )
    (comp (ref "J151")
      (value "STRIP3")
      (footprint "eagle-import:STRIP3")
      (libsource (lib "eagle-import") (part "STRIP3"))
    )
    (comp (ref "J152")
      (value "STRIP3")
      (footprint "eagle-import:STRIP3")
      (libsource (lib "eagle-import") (part "STRIP3"))
    )
    (comp (ref "J153")
      (value "STRIP3")
      (footprint "eagle-import:STRIP3")
      (libsource (lib "eagle-import") (part "STRIP3"))
    )
    (comp (ref "J154")
      (value "STRIP3")
      (footprint "eagle-import:STRIP3")
      (libsource (lib "eagle-import") (part "STRIP3"))
    )
    (comp (ref "J155")
      (value "STRIP3")
      (footprint "eagle-import:STRIP3")
      (libsource (lib "eagle-import") (part "STRIP3"))
    )
    (comp (ref "J156")
      (value "STRIP3")
      (footprint "eagle-import:STRIP3")
      (libsource (lib "eagle-import") (part "STRIP3"))
    )
    (comp (ref "J157")
      (value "STRIP3")
      (footprint "eagle-import:STRIP3")
      (libsource (lib "eagle-import") (part "STRIP3"))
    )
    (comp (ref "J158")
      (value "STRIP3")
      (footprint "eagle-import:STRIP3")
      (libsource (lib "eagle-import") (part "STRIP3"))
    )
    (comp (ref "J159")
      (value "STRIP3")
      (footprint "eagle-import:STRIP3")
      (libsource (lib "eagle-import") (part "STRIP3"))
    )
    (comp (ref "J160")
      (value "STRIP3")
      (footprint "eagle-import:STRIP3")
      (libsource (lib "eagle-import") (part "STRIP3"))
    )
    (comp (ref "J161")
      (value "STRIP3")
      (footprint "eagle-import:STRIP3")
      (libsource (lib "eagle-import") (part "STRIP3"))
    )
    (comp (ref "J162")
      (value "STRIP3")
      (footprint "eagle-import:STRIP3")
      (libsource (lib "eagle-import") (part "STRIP3"))
    )
    (comp (ref "J163")
      (value "STRIP3")
      (footprint "eagle-import:STRIP3")
      (libsource (lib "eagle-import") (part "STRIP3"))
    )
    (comp (ref "J164")
      (value "STRIP3")
      (footprint "eagle-import:STRIP3")
      (libsource (lib "eagle-import") (part "STRIP3"))
    )
    (comp (ref "J165")
      (value "STRIP3")
      (footprint "eagle-import:STRIP3")
      (libsource (lib "eagle-import") (part "STRIP3"))
    )
    (comp (ref "J166")
      (value "STRIP3")
      (footprint "eagle-import:STRIP3")
      (libsource (lib "eagle-import") (part "STRIP3"))
    )
    (comp (ref "J167")
      (value "STRIP3")
      (footprint "eagle-import:STRIP3")
      (libsource (lib "eagle-import") (part "STRIP3"))
    )
    (comp (ref "J168")
      (value "STRIP3")
      (footprint "eagle-import:STRIP3")
      (libsource (lib "eagle-import") (part "STRIP3"))
    )
    (comp (ref "J169")
      (value "STRIP3")
      (footprint "eagle-import:STRIP3")
      (libsource (lib "eagle-import") (part "STRIP3"))
    )
    (comp (ref "J170")
      (value "STRIP3")
      (footprint "eagle-import:STRIP3")
      (libsource (lib "eagle-import") (part "STRIP3"))
    )
    (comp (ref "J176")
      (value "STRIP3")
      (footprint "eagle-import:STRIP3")
      (libsource (lib "eagle-import") (part "STRIP3"))
    )
    (comp (ref "J177")
      (value "STRIP3")
      (footprint "eagle-import:STRIP3")
      (libsource (lib "eagle-import") (part "STRIP3"))
    )
    (comp (ref "L1")
      (value "F28379D_LAUNCHPAD")
      (footprint "eagle-import:F28379D_LAUNCHPAD")
      (libsource (lib "eagle-import") (part "F28379D_LAUNCHPAD"))
    )
    (comp (ref "R17")
      (value "R-US_R1206")
      (footprint "eagle-import:R1206")
      (libsource (lib "eagle-import") (part "R-US_R1206"))
    )
    (comp (ref "R18")
      (value "R-US_R1206")
      (footprint "eagle-import:R1206")
      (libsource (lib "eagle-import") (part "R-US_R1206"))
    )
    (comp (ref "R21")
      (value "R-US_R1206")
      (footprint "eagle-import:R1206")
      (libsource (lib "eagle-import") (part "R-US_R1206"))
    )
    (comp (ref "R22")
      (value "R-US_R1206")
      (footprint "eagle-import:R1206")
      (libsource (lib "eagle-import") (part "R-US_R1206"))
    )
    (comp (ref "SV8")
      (value "MA05-1")
      (footprint "eagle-import:MA05-1")
      (libsource (lib "eagle-import") (part "MA05-1"))
    )
    (comp (ref "SV9")
      (value "MA05-1")
      (footprint "eagle-import:MA05-1")
      (libsource (lib "eagle-import") (part "MA05-1"))
    )
    (comp (ref "SV10")
      (value "MA05-1")
      (footprint "eagle-import:MA05-1")
      (libsource (lib "eagle-import") (part "MA05-1"))
    )
    (comp (ref "SV12")
      (value "MA05-1")
      (footprint "eagle-import:MA05-1")
      (libsource (lib "eagle-import") (part "MA05-1"))
    )
    (comp (ref "SV13")
      (value "MA03-1")
      (footprint "eagle-import:MA03-1")
      (libsource (lib "eagle-import") (part "MA03-1"))
    )
    (comp (ref "SV14")
      (value "MA03-1")
      (footprint "eagle-import:MA03-1")
      (libsource (lib "eagle-import") (part "MA03-1"))
    )
    (comp (ref "SV30")
      (value "MA05-1")
      (footprint "eagle-import:MA05-1")
      (libsource (lib "eagle-import") (part "MA05-1"))
    )
    (comp (ref "U5")
      (value "MAX4506")
      (footprint "eagle-import:SOIC-8")
      (libsource (lib "eagle-import") (part "MAX4506-SOIC8"))
    )
    (comp (ref "C11")
      (value "0.1 uF")
      (footprint "eagle-import:C1206")
      (libsource (lib "eagle-import") (part "C-USC1206"))
    )
    (comp (ref "C13")
      (value "2.2 uF")
      (footprint "eagle-import:C1206")
      (libsource (lib "eagle-import") (part "C-USC1206"))
    )
    (comp (ref "C19")
      (value "2.2 uF")
      (footprint "eagle-import:C1206")
      (libsource (lib "eagle-import") (part "C-USC1206"))
    )
    (comp (ref "C20")
      (value "2.2 uF")
      (footprint "eagle-import:C1206")
      (libsource (lib "eagle-import") (part "C-USC1206"))
    )
    (comp (ref "C21")
      (value "2.2 uF")
      (footprint "eagle-import:C1206")
      (libsource (lib "eagle-import") (part "C-USC1206"))
    )
    (comp (ref "C22")
      (value "10 uF")
      (footprint "eagle-import:C1206")
      (libsource (lib "eagle-import") (part "C-USC1206"))
    )
    (comp (ref "C23")
      (value "10 uF")
      (footprint "eagle-import:C1206")
      (libsource (lib "eagle-import") (part "C-USC1206"))
    )
    (comp (ref "J7")
      (value "STRIP2")
      (footprint "eagle-import:STRIP2")
      (libsource (lib "eagle-import") (part "STRIP2"))
    )
    (comp (ref "J8")
      (value "PJ-082BH")
      (footprint "eagle-import:CUI_PJ-082BH")
      (fields (field (name "MANUFACTURER") "CUI Inc"))
      (libsource (lib "eagle-import") (part "PJ-082BH"))
    )
    (comp (ref "J12")
      (value "STRIP2")
      (footprint "eagle-import:STRIP2")
      (libsource (lib "eagle-import") (part "STRIP2"))
    )
    (comp (ref "J13")
      (value "STRIP2")
      (footprint "eagle-import:STRIP2")
      (libsource (lib "eagle-import") (part "STRIP2"))
    )
    (comp (ref "J22")
      (value "STRIP2")
      (footprint "eagle-import:STRIP2")
      (libsource (lib "eagle-import") (part "STRIP2"))
    )
    (comp (ref "J35")
      (value "STRIP2")
      (footprint "eagle-import:STRIP2")
      (libsource (lib "eagle-import") (part "STRIP2"))
    )
    (comp (ref "J36")
      (value "STRIP2")
      (footprint "eagle-import:STRIP2")
      (libsource (lib "eagle-import") (part "STRIP2"))
    )
    (comp (ref "J37")
      (value "STRIP2")
      (footprint "eagle-import:STRIP2")
      (libsource (lib "eagle-import") (part "STRIP2"))
    )
    (comp (ref "J38")
      (value "STRIP2")
      (footprint "eagle-import:STRIP2")
      (libsource (lib "eagle-import") (part "STRIP2"))
    )
    (comp (ref "LED6")
      (value "LEDCHIPLED_1206")
      (footprint "eagle-import:CHIPLED_1206")
      (libsource (lib "eagle-import") (part "LEDCHIPLED_1206"))
    )
    (comp (ref "LED17")
      (value "LEDCHIPLED_1206")
      (footprint "eagle-import:CHIPLED_1206")
      (libsource (lib "eagle-import") (part "LEDCHIPLED_1206"))
    )
    (comp (ref "P1")
      (value "TH_PUSHBOTTON")
      (footprint "eagle-import:TH_PUSHBUTTON")
      (libsource (lib "eagle-import") (part "TH_PUSHBOTTON"))
    )
    (comp (ref "R7")
      (value "4.7K")
      (footprint "eagle-import:M1206")
      (libsource (lib "eagle-import") (part "R-US_M1206"))
    )
    (comp (ref "R8")
      (value "4.7K")
      (footprint "eagle-import:M1206")
      (libsource (lib "eagle-import") (part "R-US_M1206"))
    )
    (comp (ref "R19")
      (value "10K")
      (footprint "eagle-import:M1206")
      (libsource (lib "eagle-import") (part "R-US_M1206"))
    )
    (comp (ref "R20")
      (value "10K")
      (footprint "eagle-import:M1206")
      (libsource (lib "eagle-import") (part "R-US_M1206"))
    )
    (comp (ref "R23")
      (value "10k")
      (footprint "eagle-import:M1206")
      (libsource (lib "eagle-import") (part "R-US_M1206"))
    )
    (comp (ref "R24")
      (value "10K")
      (footprint "eagle-import:M1206")
      (libsource (lib "eagle-import") (part "R-US_M1206"))
    )
    (comp (ref "R33")
      (value "470")
      (footprint "eagle-import:M1206")
      (libsource (lib "eagle-import") (part "R-US_M1206"))
    )
    (comp (ref "R34")
      (value "4.7k")
      (footprint "eagle-import:M1206")
      (libsource (lib "eagle-import") (part "R-US_M1206"))
    )
    (comp (ref "R35")
      (value "4.7k")
      (footprint "eagle-import:M1206")
      (libsource (lib "eagle-import") (part "R-US_M1206"))
    )
    (comp (ref "R36")
      (value "1K")
      (footprint "eagle-import:M1206")
      (libsource (lib "eagle-import") (part "R-US_M1206"))
    )
    (comp (ref "R37")
      (value "4.7k")
      (footprint "eagle-import:M1206")
      (libsource (lib "eagle-import") (part "R-US_M1206"))
    )
    (comp (ref "R38")
      (value "4.7k")
      (footprint "eagle-import:M1206")
      (libsource (lib "eagle-import") (part "R-US_M1206"))
    )
    (comp (ref "SV2")
      (value "MA20-2")
      (footprint "eagle-import:MA20-2")
      (libsource (lib "eagle-import") (part "MA20-2"))
    )
    (comp (ref "SV5")
      (value "MA20-2")
      (footprint "eagle-import:MA20-2")
      (libsource (lib "eagle-import") (part "MA20-2"))
    )
    (comp (ref "SV15")
      (value "MA07-2")
      (footprint "eagle-import:MA07-2")
      (libsource (lib "eagle-import") (part "MA07-2"))
    )
    (comp (ref "SV16")
      (value "MA05-2")
      (footprint "eagle-import:MA05-2")
      (libsource (lib "eagle-import") (part "MA05-2"))
    )
    (comp (ref "SV17")
      (value "MA05-2")
      (footprint "eagle-import:MA05-2")
      (libsource (lib "eagle-import") (part "MA05-2"))
    )
    (comp (ref "SV18")
      (value "MA05-2")
      (footprint "eagle-import:MA05-2")
      (libsource (lib "eagle-import") (part "MA05-2"))
    )
    (comp (ref "SV45")
      (value "MA03-2")
      (footprint "eagle-import:MA03-2")
      (libsource (lib "eagle-import") (part "MA03-2"))
    )
    (comp (ref "SV53")
      (value "MA10-1")
      (footprint "eagle-import:MA10-1")
      (libsource (lib "eagle-import") (part "MA10-1"))
    )
    (comp (ref "SV54")
      (value "MA10-1")
      (footprint "eagle-import:MA10-1")
      (libsource (lib "eagle-import") (part "MA10-1"))
    )
    (comp (ref "SV55")
      (value "MA10-1")
      (footprint "eagle-import:MA10-1")
      (libsource (lib "eagle-import") (part "MA10-1"))
    )
    (comp (ref "SV56")
      (value "MA10-1")
      (footprint "eagle-import:MA10-1")
      (libsource (lib "eagle-import") (part "MA10-1"))
    )
    (comp (ref "SV57")
      (value "MA10-1")
      (footprint "eagle-import:MA10-1")
      (libsource (lib "eagle-import") (part "MA10-1"))
    )
    (comp (ref "SV58")
      (value "MA10-1")
      (footprint "eagle-import:MA10-1")
      (libsource (lib "eagle-import") (part "MA10-1"))
    )
    (comp (ref "SV64")
      (value "MA03-1")
      (footprint "eagle-import:MA03-1")
      (libsource (lib "eagle-import") (part "MA03-1"))
    )
    (comp (ref "SV65")
      (value "MA03-1")
      (footprint "eagle-import:MA03-1")
      (libsource (lib "eagle-import") (part "MA03-1"))
    )
    (comp (ref "SV66")
      (value "MA03-1")
      (footprint "eagle-import:MA03-1")
      (libsource (lib "eagle-import") (part "MA03-1"))
    )
    (comp (ref "SV67")
      (value "MA03-1")
      (footprint "eagle-import:MA03-1")
      (libsource (lib "eagle-import") (part "MA03-1"))
    )
    (comp (ref "SV68")
      (value "MA03-1")
      (footprint "eagle-import:MA03-1")
      (libsource (lib "eagle-import") (part "MA03-1"))
    )
    (comp (ref "SV69")
      (value "MA03-1")
      (footprint "eagle-import:MA03-1")
      (libsource (lib "eagle-import") (part "MA03-1"))
    )
    (comp (ref "SV70")
      (value "MA03-1")
      (footprint "eagle-import:MA03-1")
      (libsource (lib "eagle-import") (part "MA03-1"))
    )
    (comp (ref "SV71")
      (value "MA03-1")
      (footprint "eagle-import:MA03-1")
      (libsource (lib "eagle-import") (part "MA03-1"))
    )
    (comp (ref "SV75")
      (value "MA03-2")
      (footprint "eagle-import:MA03-2")
      (libsource (lib "eagle-import") (part "MA03-2"))
    )
    (comp (ref "U11")
      (value "F28027")
      (footprint "eagle-import:DA38")
      (libsource (lib "eagle-import") (part "TMS320F28027DAS"))
    )
    (comp (ref "U12")
      (value "TL1963A-33KTTR")
      (footprint "eagle-import:TL1963AKTTR")
      (libsource (lib "eagle-import") (part "TL1963A-33KTTR"))
    )
    (comp (ref "B1")
      (value "BUZZER")
      (footprint "eagle-import:BUZZER")
      (libsource (lib "eagle-import") (part "BUZZER"))
    )
    (comp (ref "C5")
      (value "0.1uF")
      (footprint "eagle-import:C0805")
      (libsource (lib "eagle-import") (part "C-USC0805"))
    )
    (comp (ref "IC4")
      (value "74ALS04D")
      (footprint "eagle-import:SO14")
      (libsource (lib "eagle-import") (part "7404DALS"))
    )
    (comp (ref "LED1")
      (value "LEDCHIPLED_1206")
      (footprint "eagle-import:CHIPLED_1206")
      (libsource (lib "eagle-import") (part "LEDCHIPLED_1206"))
    )
    (comp (ref "LED2")
      (value "LEDCHIPLED_1206")
      (footprint "eagle-import:CHIPLED_1206")
      (libsource (lib "eagle-import") (part "LEDCHIPLED_1206"))
    )
    (comp (ref "LED3")
      (value "LEDCHIPLED_1206")
      (footprint "eagle-import:CHIPLED_1206")
      (libsource (lib "eagle-import") (part "LEDCHIPLED_1206"))
    )
    (comp (ref "LED4")
      (value "LEDCHIPLED_1206")
      (footprint "eagle-import:CHIPLED_1206")
      (libsource (lib "eagle-import") (part "LEDCHIPLED_1206"))
    )
    (comp (ref "LED5")
      (value "LEDCHIPLED_1206")
      (footprint "eagle-import:CHIPLED_1206")
      (libsource (lib "eagle-import") (part "LEDCHIPLED_1206"))
    )
    (comp (ref "R1")
      (value "100")
      (footprint "eagle-import:R1206")
      (libsource (lib "eagle-import") (part "R-US_R1206"))
    )
    (comp (ref "R2")
      (value "1K")
      (footprint "eagle-import:R1206")
      (libsource (lib "eagle-import") (part "R-US_R1206"))
    )
    (comp (ref "R3")
      (value "1K")
      (footprint "eagle-import:R1206")
      (libsource (lib "eagle-import") (part "R-US_R1206"))
    )
    (comp (ref "R4")
      (value "1K")
      (footprint "eagle-import:R1206")
      (libsource (lib "eagle-import") (part "R-US_R1206"))
    )
    (comp (ref "R5")
      (value "1K")
      (footprint "eagle-import:R1206")
      (libsource (lib "eagle-import") (part "R-US_R1206"))
    )
    (comp (ref "R6")
      (value "1K")
      (footprint "eagle-import:R1206")
      (libsource (lib "eagle-import") (part "R-US_R1206"))
    )
    (comp (ref "SV41")
      (value "MA06-2")
      (footprint "eagle-import:MA06-2")
      (libsource (lib "eagle-import") (part "MA06-2"))
    )
  )
  (nets
    (net (code "1") (name "+3.3V") (class "Default")
      (node (ref "C11") (pin "1") (pinfunction "1_1") (pintype "passive"))
      (node (ref "C12") (pin "1") (pinfunction "1_1") (pintype "passive"))
      (node (ref "C13") (pin "1") (pinfunction "1_1") (pintype "passive"))
      (node (ref "C14") (pin "1") (pinfunction "1_1") (pintype "passive"))
      (node (ref "C21") (pin "1") (pinfunction "1_1") (pintype "passive"))
      (node (ref "C23") (pin "1") (pinfunction "1_1") (pintype "passive"))
      (node (ref "C4") (pin "1") (pinfunction "1_1") (pintype "passive"))
      (node (ref "C5") (pin "1") (pinfunction "1_1") (pintype "passive"))
      (node (ref "C6") (pin "1") (pinfunction "1_1") (pintype "passive"))
      (node (ref "ETH1") (pin "P$10") (pinfunction "3V3_1_P$10") (pintype "bidirectional"))
      (node (ref "ETH1") (pin "P$11") (pinfunction "3V3_2_P$11") (pintype "bidirectional"))
      (node (ref "IC4") (pin "14") (pinfunction "VCC_14") (pintype "power_in"))
      (node (ref "J10") (pin "P$1") (pinfunction "P$1_P$1") (pintype "bidirectional"))
      (node (ref "J10") (pin "P$2") (pinfunction "P$2_P$2") (pintype "bidirectional"))
      (node (ref "J10") (pin "P$3") (pinfunction "P$3_P$3") (pintype "bidirectional"))
      (node (ref "J123") (pin "P$1") (pinfunction "P$1_P$1") (pintype "bidirectional"))
      (node (ref "J123") (pin "P$2") (pinfunction "P$2_P$2") (pintype "bidirectional"))
      (node (ref "J123") (pin "P$3") (pinfunction "P$3_P$3") (pintype "bidirectional"))
      (node (ref "J177") (pin "P$1") (pinfunction "P$1_P$1") (pintype "bidirectional"))
      (node (ref "J177") (pin "P$2") (pinfunction "P$2_P$2") (pintype "bidirectional"))
      (node (ref "J177") (pin "P$3") (pinfunction "P$3_P$3") (pintype "bidirectional"))
      (node (ref "L1") (pin "P$1") (pinfunction "3.3V_1_P$1") (pintype "bidirectional"))
      (node (ref "L1") (pin "P$41") (pinfunction "3.3V_2_P$41") (pintype "bidirectional"))
      (node (ref "R17") (pin "2") (pinfunction "2_2") (pintype "passive"))
      (node (ref "R18") (pin "2") (pinfunction "2_2") (pintype "passive"))
      (node (ref "R19") (pin "2") (pinfunction "2_2") (pintype "passive"))
      (node (ref "R2") (pin "1") (pinfunction "1_1") (pintype "passive"))
      (node (ref "R20") (pin "2") (pinfunction "2_2") (pintype "passive"))
      (node (ref "R23") (pin "2") (pinfunction "2_2") (pintype "passive"))
      (node (ref "R24") (pin "2") (pinfunction "2_2") (pintype "passive"))
      (node (ref "R25") (pin "2") (pinfunction "2_2") (pintype "passive"))
      (node (ref "R3") (pin "1") (pinfunction "1_1") (pintype "passive"))
      (node (ref "R34") (pin "1") (pinfunction "1_1") (pintype "passive"))
      (node (ref "R35") (pin "1") (pinfunction "1_1") (pintype "passive"))
      (node (ref "R36") (pin "2") (pinfunction "2_2") (pintype "passive"))
      (node (ref "R37") (pin "2") (pinfunction "2_2") (pintype "passive"))
      (node (ref "R38") (pin "2") (pinfunction "2_2") (pintype "passive"))
      (node (ref "R4") (pin "1") (pinfunction "1_1") (pintype "passive"))
      (node (ref "R5") (pin "1") (pinfunction "1_1") (pintype "passive"))
      (node (ref "R6") (pin "1") (pinfunction "1_1") (pintype "passive"))
      (node (ref "R8") (pin "1") (pinfunction "1_1") (pintype "passive"))
      (node (ref "SV10") (pin "2") (pinfunction "2_2") (pintype "passive"))
      (node (ref "SV11") (pin "1") (pinfunction "1_1") (pintype "passive"))
      (node (ref "SV11") (pin "2") (pinfunction "2_2") (pintype "passive"))
      (node (ref "SV15") (pin "5") (pinfunction "5_5") (pintype "passive"))
      (node (ref "SV18") (pin "4") (pinfunction "4_4") (pintype "passive"))
      (node (ref "SV26") (pin "4") (pinfunction "4_4") (pintype "passive"))
      (node (ref "SV30") (pin "2") (pinfunction "2_2") (pintype "passive"))
      (node (ref "SV75") (pin "1") (pinfunction "1_1") (pintype "passive"))
      (node (ref "SV75") (pin "3") (pinfunction "3_3") (pintype "passive"))
      (node (ref "SV75") (pin "5") (pinfunction "5_5") (pintype "passive"))
      (node (ref "U$1") (pin "1") (pinfunction "P1_VCC_1") (pintype "bidirectional"))
      (node (ref "U11") (pin "22") (pinfunction "VDDA_22") (pintype "bidirectional"))
      (node (ref "U11") (pin "4") (pinfunction "VDDIO_4") (pintype "bidirectional"))
      (node (ref "U12") (pin "P$4") (pinfunction "OUT_P$4") (pintype "bidirectional"))
      (node (ref "U12") (pin "P$5") (pinfunction "SENSE_P$5") (pintype "bidirectional"))
      (node (ref "U15") (pin "P$3") (pinfunction "P3_3.3V_P$3") (pintype "bidirectional"))
      (node (ref "U2") (pin "16") (pinfunction "VCC_16") (pintype "bidirectional"))
      (node (ref "U3") (pin "8") (pinfunction "VCC_8") (pintype "bidirectional"))
      (node (ref "U4") (pin "16") (pinfunction "VCC_16") (pintype "bidirectional"))
      (node (ref "U5") (pin "P$8") (pinfunction "V+_P$8") (pintype "bidirectional"))
    )
    (net (code "2") (name "+5V") (class "Default")
      (node (ref "C22") (pin "1") (pinfunction "1_1") (pintype "passive"))
      (node (ref "C30") (pin "1") (pinfunction "1_1") (pintype "passive"))
      (node (ref "C31") (pin "1") (pinfunction "1_1") (pintype "passive"))
      (node (ref "C32") (pin "1") (pinfunction "1_1") (pintype "passive"))
      (node (ref "C33") (pin "1") (pinfunction "1_1") (pintype "passive"))
      (node (ref "C34") (pin "1") (pinfunction "1_1") (pintype "passive"))
      (node (ref "C37") (pin "1") (pinfunction "1_1") (pintype "passive"))
      (node (ref "C38") (pin "1") (pinfunction "1_1") (pintype "passive"))
      (node (ref "C39") (pin "1") (pinfunction "1_1") (pintype "passive"))
      (node (ref "C40") (pin "1") (pinfunction "1_1") (pintype "passive"))
      (node (ref "C47") (pin "1") (pinfunction "1_1") (pintype "passive"))
      (node (ref "C48") (pin "1") (pinfunction "1_1") (pintype "passive"))
      (node (ref "C49") (pin "1") (pinfunction "1_1") (pintype "passive"))
      (node (ref "IC2") (pin "24") (pinfunction "VCC_24") (pintype "power_in"))
      (node (ref "IC3") (pin "1") (pinfunction "AVCC_1") (pintype "bidirectional"))
      (node (ref "IC3") (pin "13") (pinfunction "PDD_13") (pintype "bidirectional"))
      (node (ref "J103") (pin "P$1") (pinfunction "P$1_P$1") (pintype "bidirectional"))
      (node (ref "J103") (pin "P$2") (pinfunction "P$2_P$2") (pintype "bidirectional"))
      (node (ref "J103") (pin "P$3") (pinfunction "P$3_P$3") (pintype "bidirectional"))
      (node (ref "J152") (pin "P$1") (pinfunction "P$1_P$1") (pintype "bidirectional"))
      (node (ref "J152") (pin "P$2") (pinfunction "P$2_P$2") (pintype "bidirectional"))
      (node (ref "J152") (pin "P$3") (pinfunction "P$3_P$3") (pintype "bidirectional"))
      (node (ref "J7") (pin "P$2") (pinfunction "P$2_P$2") (pintype "bidirectional"))
      (node (ref "J8") (pin "P$1") (pinfunction "1_P$1") (pintype "passive"))
      (node (ref "L1") (pin "P$21") (pinfunction "5V_1_P$21") (pintype "bidirectional"))
      (node (ref "L1") (pin "P$61") (pinfunction "5V_2_P$61") (pintype "bidirectional"))
      (node (ref "QG1") (pin "14") (pinfunction "VCC_14") (pintype "power_in"))
      (node (ref "R21") (pin "2") (pinfunction "2_2") (pintype "passive"))
      (node (ref "R22") (pin "2") (pinfunction "2_2") (pintype "passive"))
      (node (ref "R33") (pin "2") (pinfunction "2_2") (pintype "passive"))
      (node (ref "SV12") (pin "2") (pinfunction "2_2") (pintype "passive"))
      (node (ref "SV17") (pin "3") (pinfunction "3_3") (pintype "passive"))
      (node (ref "SV17") (pin "4") (pinfunction "4_4") (pintype "passive"))
      (node (ref "SV18") (pin "3") (pinfunction "3_3") (pintype "passive"))
      (node (ref "SV2") (pin "1") (pinfunction "1_1") (pintype "passive"))
      (node (ref "SV2") (pin "2") (pinfunction "2_2") (pintype "passive"))
      (node (ref "SV2") (pin "3") (pinfunction "3_3") (pintype "passive"))
      (node (ref "SV2") (pin "4") (pinfunction "4_4") (pintype "passive"))
      (node (ref "SV21") (pin "7") (pinfunction "7_7") (pintype "passive"))
      (node (ref "SV21") (pin "8") (pinfunction "8_8") (pintype "passive"))
      (node (ref "SV23") (pin "7") (pinfunction "7_7") (pintype "passive"))
      (node (ref "SV23") (pin "8") (pinfunction "8_8") (pintype "passive"))
      (node (ref "SV24") (pin "7") (pinfunction "7_7") (pintype "passive"))
      (node (ref "SV24") (pin "8") (pinfunction "8_8") (pintype "passive"))
      (node (ref "SV25") (pin "3") (pinfunction "3_3") (pintype "passive"))
      (node (ref "SV25") (pin "4") (pinfunction "4_4") (pintype "passive"))
      (node (ref "SV26") (pin "3") (pinfunction "3_3") (pintype "passive"))
      (node (ref "SV28") (pin "8") (pinfunction "8_8") (pintype "passive"))
      (node (ref "SV45") (pin "1") (pinfunction "1_1") (pintype "passive"))
      (node (ref "SV45") (pin "3") (pinfunction "3_3") (pintype "passive"))
      (node (ref "SV45") (pin "5") (pinfunction "5_5") (pintype "passive"))
      (node (ref "SV8") (pin "2") (pinfunction "2_2") (pintype "passive"))
      (node (ref "SV9") (pin "2") (pinfunction "2_2") (pintype "passive"))
      (node (ref "U10") (pin "14") (pinfunction "VDD_14") (pintype "bidirectional"))
      (node (ref "U12") (pin "P$1") (pinfunction "~{SHDN}_P$1") (pintype "bidirectional"))
      (node (ref "U12") (pin "P$2") (pinfunction "IN_P$2") (pintype "bidirectional"))
      (node (ref "U7") (pin "14") (pinfunction "VDD_14") (pintype "bidirectional"))
      (node (ref "U8") (pin "14") (pinfunction "VDD_14") (pintype "bidirectional"))
      (node (ref "U9") (pin "14") (pinfunction "VDD_14") (pintype "bidirectional"))
    )
    (net (code "3") (name "28027_GPIO0") (class "Default")
      (node (ref "SV17") (pin "9") (pinfunction "9_9") (pintype "passive"))
      (node (ref "U11") (pin "37") (pinfunction "GPIO0/EPWM1A_37") (pintype "bidirectional"))
    )
    (net (code "4") (name "28027_GPIO1") (class "Default")
      (node (ref "SV17") (pin "7") (pinfunction "7_7") (pintype "passive"))
      (node (ref "U11") (pin "36") (pinfunction "GPIO1/EPWM1A_36") (pintype "bidirectional"))
    )
    (net (code "5") (name "28027_GPIO2") (class "Default")
      (node (ref "SV17") (pin "5") (pinfunction "5_5") (pintype "passive"))
      (node (ref "U11") (pin "5") (pinfunction "GPIO2/EPWM2A_5") (pintype "bidirectional"))
    )
    (net (code "6") (name "28027_GPIO3") (class "Default")
      (node (ref "SV17") (pin "10") (pinfunction "10_10") (pintype "passive"))
      (node (ref "U11") (pin "6") (pinfunction "GPIO3/EPWM2B_6") (pintype "bidirectional"))
    )
    (net (code "7") (name "28027_GPIO4") (class "Default")
      (node (ref "SV17") (pin "8") (pinfunction "8_8") (pintype "passive"))
      (node (ref "U11") (pin "7") (pinfunction "GPIO4/EPWM3A_7") (pintype "bidirectional"))
    )
    (net (code "8") (name "28027_GPIO5") (class "Default")
      (node (ref "SV17") (pin "6") (pinfunction "6_6") (pintype "passive"))
      (node (ref "U11") (pin "8") (pinfunction "GPIO5/EPWM3B_8") (pintype "bidirectional"))
    )
    (net (code "9") (name "28027_GPIO6") (class "Default")
      (node (ref "SV18") (pin "9") (pinfunction "9_9") (pintype "passive"))
      (node (ref "U11") (pin "9") (pinfunction "GPIO6/EPWM4A_9") (pintype "bidirectional"))
    )
    (net (code "10") (name "28027_GPIO7") (class "Default")
      (node (ref "SV18") (pin "7") (pinfunction "7_7") (pintype "passive"))
      (node (ref "U11") (pin "10") (pinfunction "GPIO7/EPWM4B_10") (pintype "bidirectional"))
    )
    (net (code "11") (name "28027_GPIO12") (class "Default")
      (node (ref "SV16") (pin "4") (pinfunction "4_4") (pintype "passive"))
      (node (ref "U11") (pin "13") (pinfunction "GPIO12/SCITXDA_13") (pintype "bidirectional"))
    )
    (net (code "12") (name "28027_GPIO34") (class "Default")
      (node (ref "LED17") (pin "C") (pinfunction "C_C") (pintype "passive"))
      (node (ref "R37") (pin "1") (pinfunction "1_1") (pintype "passive"))
      (node (ref "U11") (pin "27") (pinfunction "GPIO34_27") (pintype "bidirectional"))
    )
    (net (code "13") (name "28027_SCL") (class "Default")
      (node (ref "R34") (pin "2") (pinfunction "2_2") (pintype "passive"))
      (node (ref "SV16") (pin "3") (pinfunction "3_3") (pintype "passive"))
      (node (ref "U11") (pin "15") (pinfunction "GPIO29/SCITXDA_15") (pintype "bidirectional"))
    )
    (net (code "14") (name "28027_SDA") (class "Default")
      (node (ref "R35") (pin "2") (pinfunction "2_2") (pintype "passive"))
      (node (ref "SV16") (pin "5") (pinfunction "5_5") (pintype "passive"))
      (node (ref "U11") (pin "14") (pinfunction "GPIO28/SCIRXDA_14") (pintype "bidirectional"))
    )
    (net (code "15") (name "28027_SPICLKA") (class "Default")
      (node (ref "J38") (pin "P$1") (pinfunction "P$1_P$1") (pintype "bidirectional"))
      (node (ref "U11") (pin "32") (pinfunction "GPIO18/SPICLKA/SCITXDA_32") (pintype "bidirectional"))
    )
    (net (code "16") (name "28027_SPISIMOA") (class "Default")
      (node (ref "J36") (pin "P$1") (pinfunction "P$1_P$1") (pintype "bidirectional"))
      (node (ref "U11") (pin "35") (pinfunction "GPIO16/SPISIMOA_35") (pintype "bidirectional"))
    )
    (net (code "17") (name "28027_SPISOMIA") (class "Default")
      (node (ref "J35") (pin "P$1") (pinfunction "P$1_P$1") (pintype "bidirectional"))
      (node (ref "U11") (pin "34") (pinfunction "GPIO17/SPISOMIA_34") (pintype "bidirectional"))
    )
    (net (code "18") (name "28027_SPISTEA") (class "Default")
      (node (ref "J37") (pin "P$1") (pinfunction "P$1_P$1") (pintype "bidirectional"))
      (node (ref "U11") (pin "33") (pinfunction "GPIO19//SPISTEA/SCIRXDA_33") (pintype "bidirectional"))
    )
    (net (code "19") (name "ADCA0") (class "Default")
      (node (ref "SV16") (pin "7") (pinfunction "7_7") (pintype "passive"))
      (node (ref "U11") (pin "21") (pinfunction "ADCINA0/VREFHI_21") (pintype "bidirectional"))
    )
    (net (code "20") (name "ADCA2") (class "Default")
      (node (ref "SV16") (pin "9") (pinfunction "9_9") (pintype "passive"))
      (node (ref "U11") (pin "20") (pinfunction "ADCINA2/AIO2_20") (pintype "bidirectional"))
    )
    (net (code "21") (name "ADCA4") (class "Default")
      (node (ref "SV16") (pin "8") (pinfunction "8_8") (pintype "passive"))
      (node (ref "U11") (pin "19") (pinfunction "ADCINA4/AIO4_19") (pintype "bidirectional"))
    )
    (net (code "22") (name "ADCA6") (class "Default")
      (node (ref "SV16") (pin "2") (pinfunction "2_2") (pintype "passive"))
      (node (ref "U11") (pin "18") (pinfunction "ADCINA6/AIO6_18") (pintype "bidirectional"))
    )
    (net (code "23") (name "ADCB2") (class "Default")
      (node (ref "SV16") (pin "10") (pinfunction "10_10") (pintype "passive"))
      (node (ref "U11") (pin "24") (pinfunction "ADCINB2/AIO10_24") (pintype "bidirectional"))
    )
    (net (code "24") (name "ADCB4") (class "Default")
      (node (ref "SV16") (pin "6") (pinfunction "6_6") (pintype "passive"))
      (node (ref "U11") (pin "25") (pinfunction "ADCINB4/AIO12_25") (pintype "bidirectional"))
    )
    (net (code "25") (name "ADCB6") (class "Default")
      (node (ref "U11") (pin "26") (pinfunction "ADCINB6/AIO14_26") (pintype "bidirectional"))
    )
    (net (code "26") (name "ADCIN14") (class "Default")
      (node (ref "J105") (pin "P$1") (pinfunction "P$1_P$1") (pintype "bidirectional"))
      (node (ref "J105") (pin "P$2") (pinfunction "P$2_P$2") (pintype "bidirectional"))
      (node (ref "J105") (pin "P$3") (pinfunction "P$3_P$3") (pintype "bidirectional"))
      (node (ref "L1") (pin "P$23") (pinfunction "ADCIN14_P$23") (pintype "bidirectional"))
    )
    (net (code "27") (name "ADCIN15") (class "Default")
      (node (ref "J150") (pin "P$1") (pinfunction "P$1_P$1") (pintype "bidirectional"))
      (node (ref "J150") (pin "P$2") (pinfunction "P$2_P$2") (pintype "bidirectional"))
      (node (ref "J150") (pin "P$3") (pinfunction "P$3_P$3") (pintype "bidirectional"))
      (node (ref "L1") (pin "P$63") (pinfunction "ADCIN15_P$63") (pintype "bidirectional"))
    )
    (net (code "28") (name "ADCINA2") (class "Default")
      (node (ref "J111") (pin "P$1") (pinfunction "P$1_P$1") (pintype "bidirectional"))
      (node (ref "J111") (pin "P$2") (pinfunction "P$2_P$2") (pintype "bidirectional"))
      (node (ref "J111") (pin "P$3") (pinfunction "P$3_P$3") (pintype "bidirectional"))
      (node (ref "L1") (pin "P$29") (pinfunction "ADCINA2_P$29") (pintype "bidirectional"))
    )
    (net (code "29") (name "ADCINA3") (class "Default")
      (node (ref "J108") (pin "P$1") (pinfunction "P$1_P$1") (pintype "bidirectional"))
      (node (ref "J108") (pin "P$2") (pinfunction "P$2_P$2") (pintype "bidirectional"))
      (node (ref "J108") (pin "P$3") (pinfunction "P$3_P$3") (pintype "bidirectional"))
      (node (ref "L1") (pin "P$26") (pinfunction "ADCINA3_P$26") (pintype "bidirectional"))
    )
    (net (code "30") (name "ADCINA4") (class "Default")
      (node (ref "J144") (pin "P$1") (pinfunction "P$1_P$1") (pintype "bidirectional"))
      (node (ref "J144") (pin "P$2") (pinfunction "P$2_P$2") (pintype "bidirectional"))
      (node (ref "J144") (pin "P$3") (pinfunction "P$3_P$3") (pintype "bidirectional"))
      (node (ref "L1") (pin "P$69") (pinfunction "ADCINA4_P$69") (pintype "bidirectional"))
    )
    (net (code "31") (name "ADCINA5") (class "Default")
      (node (ref "J147") (pin "P$1") (pinfunction "P$1_P$1") (pintype "bidirectional"))
      (node (ref "J147") (pin "P$2") (pinfunction "P$2_P$2") (pintype "bidirectional"))
      (node (ref "J147") (pin "P$3") (pinfunction "P$3_P$3") (pintype "bidirectional"))
      (node (ref "L1") (pin "P$66") (pinfunction "ADCINA5_P$66") (pintype "bidirectional"))
    )
    (net (code "32") (name "ADCINB2") (class "Default")
      (node (ref "J110") (pin "P$1") (pinfunction "P$1_P$1") (pintype "bidirectional"))
      (node (ref "J110") (pin "P$2") (pinfunction "P$2_P$2") (pintype "bidirectional"))
      (node (ref "J110") (pin "P$3") (pinfunction "P$3_P$3") (pintype "bidirectional"))
      (node (ref "L1") (pin "P$28") (pinfunction "ADCINB2_P$28") (pintype "bidirectional"))
    )
    (net (code "33") (name "ADCINB3") (class "Default")
      (node (ref "J107") (pin "P$1") (pinfunction "P$1_P$1") (pintype "bidirectional"))
      (node (ref "J107") (pin "P$2") (pinfunction "P$2_P$2") (pintype "bidirectional"))
      (node (ref "J107") (pin "P$3") (pinfunction "P$3_P$3") (pintype "bidirectional"))
      (node (ref "L1") (pin "P$25") (pinfunction "ADCINB3_P$25") (pintype "bidirectional"))
    )
    (net (code "34") (name "ADCINB4") (class "Default")
      (node (ref "J145") (pin "P$1") (pinfunction "P$1_P$1") (pintype "bidirectional"))
      (node (ref "J145") (pin "P$2") (pinfunction "P$2_P$2") (pintype "bidirectional"))
      (node (ref "J145") (pin "P$3") (pinfunction "P$3_P$3") (pintype "bidirectional"))
      (node (ref "L1") (pin "P$68") (pinfunction "ADCINB4_P$68") (pintype "bidirectional"))
    )
    (net (code "35") (name "ADCINB5") (class "Default")
      (node (ref "J148") (pin "P$1") (pinfunction "P$1_P$1") (pintype "bidirectional"))
      (node (ref "J148") (pin "P$2") (pinfunction "P$2_P$2") (pintype "bidirectional"))
      (node (ref "J148") (pin "P$3") (pinfunction "P$3_P$3") (pintype "bidirectional"))
      (node (ref "L1") (pin "P$65") (pinfunction "ADCINB5_P$65") (pintype "bidirectional"))
    )
    (net (code "36") (name "ADCINC2") (class "Default")
      (node (ref "J109") (pin "P$1") (pinfunction "P$1_P$1") (pintype "bidirectional"))
      (node (ref "J109") (pin "P$2") (pinfunction "P$2_P$2") (pintype "bidirectional"))
      (node (ref "J109") (pin "P$3") (pinfunction "P$3_P$3") (pintype "bidirectional"))
      (node (ref "L1") (pin "P$27") (pinfunction "ADCINC2_P$27") (pintype "bidirectional"))
      (node (ref "U15") (pin "P$4") (pinfunction "P4_Y_P$4") (pintype "bidirectional"))
    )
    (net (code "37") (name "ADCINC3") (class "Default")
      (node (ref "J106") (pin "P$1") (pinfunction "P$1_P$1") (pintype "bidirectional"))
      (node (ref "J106") (pin "P$2") (pinfunction "P$2_P$2") (pintype "bidirectional"))
      (node (ref "J106") (pin "P$3") (pinfunction "P$3_P$3") (pintype "bidirectional"))
      (node (ref "L1") (pin "P$24") (pinfunction "ADCINC3_P$24") (pintype "bidirectional"))
      (node (ref "U15") (pin "P$5") (pinfunction "P5_4Y_P$5") (pintype "bidirectional"))
    )
    (net (code "38") (name "ADCINC4") (class "Default")
      (node (ref "J146") (pin "P$1") (pinfunction "P$1_P$1") (pintype "bidirectional"))
      (node (ref "J146") (pin "P$2") (pinfunction "P$2_P$2") (pintype "bidirectional"))
      (node (ref "J146") (pin "P$3") (pinfunction "P$3_P$3") (pintype "bidirectional"))
      (node (ref "L1") (pin "P$67") (pinfunction "ADCINC4_P$67") (pintype "bidirectional"))
      (node (ref "U15") (pin "P$7") (pinfunction "P7_4X_P$7") (pintype "bidirectional"))
    )
    (net (code "39") (name "ADCINC5") (class "Default")
      (node (ref "J149") (pin "P$1") (pinfunction "P$1_P$1") (pintype "bidirectional"))
      (node (ref "J149") (pin "P$2") (pinfunction "P$2_P$2") (pintype "bidirectional"))
      (node (ref "J149") (pin "P$3") (pinfunction "P$3_P$3") (pintype "bidirectional"))
      (node (ref "L1") (pin "P$64") (pinfunction "ADCINC5_P$64") (pintype "bidirectional"))
      (node (ref "U15") (pin "P$8") (pinfunction "P8_X_P$8") (pintype "bidirectional"))
    )
    (net (code "40") (name "ADXRS300_3V3") (class "Default")
      (node (ref "J1") (pin "P$1") (pinfunction "P$1_P$1") (pintype "bidirectional"))
      (node (ref "J1") (pin "P$2") (pinfunction "P$2_P$2") (pintype "bidirectional"))
      (node (ref "R10") (pin "2") (pinfunction "2_2") (pintype "passive"))
      (node (ref "R9") (pin "1") (pinfunction "1_1") (pintype "passive"))
    )
    (net (code "41") (name "DACOUTA") (class "Default")
      (node (ref "J112") (pin "P$1") (pinfunction "P$1_P$1") (pintype "bidirectional"))
      (node (ref "J112") (pin "P$2") (pinfunction "P$2_P$2") (pintype "bidirectional"))
      (node (ref "J112") (pin "P$3") (pinfunction "P$3_P$3") (pintype "bidirectional"))
      (node (ref "L1") (pin "P$30") (pinfunction "ADCINA0/DACOUTA_P$30") (pintype "bidirectional"))
    )
    (net (code "42") (name "DACOUTB") (class "Default")
      (node (ref "J143") (pin "P$1") (pinfunction "P$1_P$1") (pintype "bidirectional"))
      (node (ref "J143") (pin "P$2") (pinfunction "P$2_P$2") (pintype "bidirectional"))
      (node (ref "J143") (pin "P$3") (pinfunction "P$3_P$3") (pintype "bidirectional"))
      (node (ref "L1") (pin "P$70") (pinfunction "ADCINA1/DACOUTB_P$70") (pintype "bidirectional"))
    )
    (net (code "43") (name "EQEP1A") (class "Default")
      (node (ref "J3") (pin "P$1") (pinfunction "P$1_P$1") (pintype "bidirectional"))
      (node (ref "J3") (pin "P$2") (pinfunction "P$2_P$2") (pintype "bidirectional"))
      (node (ref "SV21") (pin "5") (pinfunction "5_5") (pintype "passive"))
    )
    (net (code "44") (name "EQEP1B") (class "Default")
      (node (ref "J6") (pin "P$1") (pinfunction "P$1_P$1") (pintype "bidirectional"))
      (node (ref "J6") (pin "P$2") (pinfunction "P$2_P$2") (pintype "bidirectional"))
      (node (ref "SV21") (pin "9") (pinfunction "9_9") (pintype "passive"))
    )
    (net (code "45") (name "EQEP2A") (class "Default")
      (node (ref "J2") (pin "P$1") (pinfunction "P$1_P$1") (pintype "bidirectional"))
      (node (ref "J2") (pin "P$2") (pinfunction "P$2_P$2") (pintype "bidirectional"))
      (node (ref "SV21") (pin "6") (pinfunction "6_6") (pintype "passive"))
    )
    (net (code "46") (name "EQEP2B") (class "Default")
      (node (ref "J5") (pin "P$1") (pinfunction "P$1_P$1") (pintype "bidirectional"))
      (node (ref "J5") (pin "P$2") (pinfunction "P$2_P$2") (pintype "bidirectional"))
      (node (ref "SV21") (pin "10") (pinfunction "10_10") (pintype "passive"))
    )
    (net (code "47") (name "EQEP3A_5V") (class "Default")
      (node (ref "IC2") (pin "16") (pinfunction "A2_16") (pintype "bidirectional"))
      (node (ref "SV28") (pin "6") (pinfunction "6_6") (pintype "passive"))
    )
    (net (code "48") (name "EQEP3B_5V") (class "Default")
      (node (ref "IC2") (pin "14") (pinfunction "A1_14") (pintype "bidirectional"))
      (node (ref "SV28") (pin "10") (pinfunction "10_10") (pintype "passive"))
    )
    (net (code "49") (name "GND") (class "Default")
      (node (ref "B1") (pin "P$2") (pinfunction "P$2_P$2") (pintype "bidirectional"))
      (node (ref "B3") (pin "P$1") (pinfunction "P1_P$1") (pintype "bidirectional"))
      (node (ref "C10") (pin "2") (pinfunction "2_2") (pintype "passive"))
      (node (ref "C11") (pin "2") (pinfunction "2_2") (pintype "passive"))
      (node (ref "C12") (pin "2") (pinfunction "2_2") (pintype "passive"))
      (node (ref "C13") (pin "2") (pinfunction "2_2") (pintype "passive"))
      (node (ref "C14") (pin "2") (pinfunction "2_2") (pintype "passive"))
      (node (ref "C15") (pin "1") (pinfunction "1_1") (pintype "passive"))
      (node (ref "C18") (pin "2") (pinfunction "2_2") (pintype "passive"))
      (node (ref "C19") (pin "2") (pinfunction "2_2") (pintype "passive"))
      (node (ref "C20") (pin "2") (pinfunction "2_2") (pintype "passive"))
      (node (ref "C21") (pin "2") (pinfunction "2_2") (pintype "passive"))
      (node (ref "C22") (pin "2") (pinfunction "2_2") (pintype "passive"))
      (node (ref "C23") (pin "2") (pinfunction "2_2") (pintype "passive"))
      (node (ref "C24") (pin "2") (pinfunction "2_2") (pintype "passive"))
      (node (ref "C25") (pin "2") (pinfunction "2_2") (pintype "passive"))
      (node (ref "C26") (pin "2") (pinfunction "2_2") (pintype "passive"))
      (node (ref "C27") (pin "2") (pinfunction "2_2") (pintype "passive"))
      (node (ref "C28") (pin "2") (pinfunction "2_2") (pintype "passive"))
      (node (ref "C29") (pin "2") (pinfunction "2_2") (pintype "passive"))
      (node (ref "C30") (pin "2") (pinfunction "2_2") (pintype "passive"))
      (node (ref "C31") (pin "2") (pinfunction "2_2") (pintype "passive"))
      (node (ref "C32") (pin "2") (pinfunction "2_2") (pintype "passive"))
      (node (ref "C33") (pin "2") (pinfunction "2_2") (pintype "passive"))
      (node (ref "C34") (pin "2") (pinfunction "2_2") (pintype "passive"))
      (node (ref "C37") (pin "2") (pinfunction "2_2") (pintype "passive"))
      (node (ref "C38") (pin "2") (pinfunction "2_2") (pintype "passive"))
      (node (ref "C39") (pin "2") (pinfunction "2_2") (pintype "passive"))
      (node (ref "C4") (pin "2") (pinfunction "2_2") (pintype "passive"))
      (node (ref "C40") (pin "2") (pinfunction "2_2") (pintype "passive"))
      (node (ref "C47") (pin "2") (pinfunction "2_2") (pintype "passive"))
      (node (ref "C48") (pin "2") (pinfunction "2_2") (pintype "passive"))
      (node (ref "C49") (pin "2") (pinfunction "2_2") (pintype "passive"))
      (node (ref "C5") (pin "2") (pinfunction "2_2") (pintype "passive"))
      (node (ref "C6") (pin "2") (pinfunction "2_2") (pintype "passive"))
      (node (ref "C7") (pin "1") (pinfunction "1_1") (pintype "passive"))
      (node (ref "ETH1") (pin "P$1") (pinfunction "GND_1_P$1") (pintype "bidirectional"))
      (node (ref "ETH1") (pin "P$12") (pinfunction "GND_3_P$12") (pintype "bidirectional"))
      (node (ref "ETH1") (pin "P$2") (pinfunction "GND_2_P$2") (pintype "bidirectional"))
      (node (ref "IC2") (pin "1") (pinfunction "G_1") (pintype "input"))
      (node (ref "IC2") (pin "12") (pinfunction "GND_12") (pintype "power_in"))
      (node (ref "IC2") (pin "13") (pinfunction "G_13") (pintype "input"))
      (node (ref "IC3") (pin "12") (pinfunction "PGND_12") (pintype "bidirectional"))
      (node (ref "IC3") (pin "8") (pinfunction "AGND_8") (pintype "bidirectional"))
      (node (ref "IC4") (pin "7") (pinfunction "GND_7") (pintype "power_in"))
      (node (ref "J102") (pin "P$1") (pinfunction "P$1_P$1") (pintype "bidirectional"))
      (node (ref "J102") (pin "P$2") (pinfunction "P$2_P$2") (pintype "bidirectional"))
      (node (ref "J102") (pin "P$3") (pinfunction "P$3_P$3") (pintype "bidirectional"))
      (node (ref "J104") (pin "P$1") (pinfunction "P$1_P$1") (pintype "bidirectional"))
      (node (ref "J104") (pin "P$2") (pinfunction "P$2_P$2") (pintype "bidirectional"))
      (node (ref "J104") (pin "P$3") (pinfunction "P$3_P$3") (pintype "bidirectional"))
      (node (ref "J124") (pin "P$1") (pinfunction "P$1_P$1") (pintype "bidirectional"))
      (node (ref "J124") (pin "P$2") (pinfunction "P$2_P$2") (pintype "bidirectional"))
      (node (ref "J124") (pin "P$3") (pinfunction "P$3_P$3") (pintype "bidirectional"))
      (node (ref "J151") (pin "P$1") (pinfunction "P$1_P$1") (pintype "bidirectional"))
      (node (ref "J151") (pin "P$2") (pinfunction "P$2_P$2") (pintype "bidirectional"))
      (node (ref "J151") (pin "P$3") (pinfunction "P$3_P$3") (pintype "bidirectional"))
      (node (ref "J153") (pin "P$1") (pinfunction "P$1_P$1") (pintype "bidirectional"))
      (node (ref "J153") (pin "P$2") (pinfunction "P$2_P$2") (pintype "bidirectional"))
      (node (ref "J153") (pin "P$3") (pinfunction "P$3_P$3") (pintype "bidirectional"))
      (node (ref "J7") (pin "P$1") (pinfunction "P$1_P$1") (pintype "bidirectional"))
      (node (ref "J8") (pin "P$2") (pinfunction "2_P$2") (pintype "passive"))
      (node (ref "J8") (pin "P$3") (pinfunction "SHD1_P$3") (pintype "bidirectional"))
      (node (ref "J8") (pin "P$4") (pinfunction "SHD2_P$4") (pintype "bidirectional"))
      (node (ref "J8") (pin "P$5") (pinfunction "SHD3_P$5") (pintype "bidirectional"))
      (node (ref "J8") (pin "P$6") (pinfunction "SHD4_P$6") (pintype "bidirectional"))
      (node (ref "L1") (pin "P$20") (pinfunction "GND_1_P$20") (pintype "bidirectional"))
      (node (ref "L1") (pin "P$22") (pinfunction "GND_2_P$22") (pintype "bidirectional"))
      (node (ref "L1") (pin "P$60") (pinfunction "GND_3_P$60") (pintype "bidirectional"))
      (node (ref "L1") (pin "P$62") (pinfunction "GND_4_P$62") (pintype "bidirectional"))
      (node (ref "LED6") (pin "C") (pinfunction "C_C") (pintype "passive"))
      (node (ref "P1") (pin "2") (pinfunction "2_2") (pintype "bidirectional"))
      (node (ref "QG1") (pin "7") (pinfunction "GND_7") (pintype "power_in"))
      (node (ref "R10") (pin "1") (pinfunction "1_1") (pintype "passive"))
      (node (ref "R12") (pin "1") (pinfunction "1_1") (pintype "passive"))
      (node (ref "R14") (pin "1") (pinfunction "1_1") (pintype "passive"))
      (node (ref "R16") (pin "1") (pinfunction "1_1") (pintype "passive"))
      (node (ref "R7") (pin "2") (pinfunction "2_2") (pintype "passive"))
      (node (ref "SV1") (pin "1") (pinfunction "1_1") (pintype "passive"))
      (node (ref "SV1") (pin "2") (pinfunction "2_2") (pintype "passive"))
      (node (ref "SV10") (pin "1") (pinfunction "1_1") (pintype "passive"))
      (node (ref "SV11") (pin "3") (pinfunction "3_3") (pintype "passive"))
      (node (ref "SV11") (pin "4") (pinfunction "4_4") (pintype "passive"))
      (node (ref "SV12") (pin "1") (pinfunction "1_1") (pintype "passive"))
      (node (ref "SV15") (pin "10") (pinfunction "10_10") (pintype "passive"))
      (node (ref "SV15") (pin "12") (pinfunction "12_12") (pintype "passive"))
      (node (ref "SV15") (pin "4") (pinfunction "4_4") (pintype "passive"))
      (node (ref "SV15") (pin "8") (pinfunction "8_8") (pintype "passive"))
      (node (ref "SV16") (pin "1") (pinfunction "1_1") (pintype "passive"))
      (node (ref "SV17") (pin "1") (pinfunction "1_1") (pintype "passive"))
      (node (ref "SV17") (pin "2") (pinfunction "2_2") (pintype "passive"))
      (node (ref "SV18") (pin "1") (pinfunction "1_1") (pintype "passive"))
      (node (ref "SV18") (pin "2") (pinfunction "2_2") (pintype "passive"))
      (node (ref "SV2") (pin "13") (pinfunction "13_13") (pintype "passive"))
      (node (ref "SV2") (pin "14") (pinfunction "14_14") (pintype "passive"))
      (node (ref "SV2") (pin "19") (pinfunction "19_19") (pintype "passive"))
      (node (ref "SV2") (pin "20") (pinfunction "20_20") (pintype "passive"))
      (node (ref "SV2") (pin "29") (pinfunction "29_29") (pintype "passive"))
      (node (ref "SV2") (pin "30") (pinfunction "30_30") (pintype "passive"))
      (node (ref "SV2") (pin "33") (pinfunction "33_33") (pintype "passive"))
      (node (ref "SV2") (pin "34") (pinfunction "34_34") (pintype "passive"))
      (node (ref "SV2") (pin "5") (pinfunction "5_5") (pintype "passive"))
      (node (ref "SV2") (pin "6") (pinfunction "6_6") (pintype "passive"))
      (node (ref "SV21") (pin "1") (pinfunction "1_1") (pintype "passive"))
      (node (ref "SV21") (pin "2") (pinfunction "2_2") (pintype "passive"))
      (node (ref "SV23") (pin "1") (pinfunction "1_1") (pintype "passive"))
      (node (ref "SV23") (pin "2") (pinfunction "2_2") (pintype "passive"))
      (node (ref "SV24") (pin "1") (pinfunction "1_1") (pintype "passive"))
      (node (ref "SV24") (pin "2") (pinfunction "2_2") (pintype "passive"))
      (node (ref "SV25") (pin "1") (pinfunction "1_1") (pintype "passive"))
      (node (ref "SV25") (pin "2") (pinfunction "2_2") (pintype "passive"))
      (node (ref "SV26") (pin "1") (pinfunction "1_1") (pintype "passive"))
      (node (ref "SV26") (pin "2") (pinfunction "2_2") (pintype "passive"))
      (node (ref "SV28") (pin "2") (pinfunction "2_2") (pintype "passive"))
      (node (ref "SV3") (pin "5") (pinfunction "5_5") (pintype "passive"))
      (node (ref "SV3") (pin "6") (pinfunction "6_6") (pintype "passive"))
      (node (ref "SV30") (pin "1") (pinfunction "1_1") (pintype "passive"))
      (node (ref "SV4") (pin "1") (pinfunction "1_1") (pintype "passive"))
      (node (ref "SV4") (pin "2") (pinfunction "2_2") (pintype "passive"))
      (node (ref "SV45") (pin "2") (pinfunction "2_2") (pintype "passive"))
      (node (ref "SV45") (pin "4") (pinfunction "4_4") (pintype "passive"))
      (node (ref "SV45") (pin "6") (pinfunction "6_6") (pintype "passive"))
      (node (ref "SV5") (pin "10") (pinfunction "10_10") (pintype "passive"))
      (node (ref "SV5") (pin "25") (pinfunction "25_25") (pintype "passive"))
      (node (ref "SV5") (pin "26") (pinfunction "26_26") (pintype "passive"))
      (node (ref "SV5") (pin "39") (pinfunction "39_39") (pintype "passive"))
      (node (ref "SV5") (pin "40") (pinfunction "40_40") (pintype "passive"))
      (node (ref "SV5") (pin "9") (pinfunction "9_9") (pintype "passive"))
      (node (ref "SV6") (pin "5") (pinfunction "5_5") (pintype "passive"))
      (node (ref "SV68") (pin "1") (pinfunction "1_1") (pintype "passive"))
      (node (ref "SV68") (pin "2") (pinfunction "2_2") (pintype "passive"))
      (node (ref "SV68") (pin "3") (pinfunction "3_3") (pintype "passive"))
      (node (ref "SV69") (pin "1") (pinfunction "1_1") (pintype "passive"))
      (node (ref "SV69") (pin "2") (pinfunction "2_2") (pintype "passive"))
      (node (ref "SV69") (pin "3") (pinfunction "3_3") (pintype "passive"))
      (node (ref "SV70") (pin "1") (pinfunction "1_1") (pintype "passive"))
      (node (ref "SV70") (pin "2") (pinfunction "2_2") (pintype "passive"))
      (node (ref "SV70") (pin "3") (pinfunction "3_3") (pintype "passive"))
      (node (ref "SV71") (pin "1") (pinfunction "1_1") (pintype "passive"))
      (node (ref "SV71") (pin "2") (pinfunction "2_2") (pintype "passive"))
      (node (ref "SV71") (pin "3") (pinfunction "3_3") (pintype "passive"))
      (node (ref "SV75") (pin "2") (pinfunction "2_2") (pintype "passive"))
      (node (ref "SV75") (pin "4") (pinfunction "4_4") (pintype "passive"))
      (node (ref "SV75") (pin "6") (pinfunction "6_6") (pintype "passive"))
      (node (ref "SV8") (pin "1") (pinfunction "1_1") (pintype "passive"))
      (node (ref "SV9") (pin "1") (pinfunction "1_1") (pintype "passive"))
      (node (ref "U$1") (pin "2") (pinfunction "P2_GND_2") (pintype "bidirectional"))
      (node (ref "U10") (pin "3") (pinfunction "GND_3") (pintype "bidirectional"))
      (node (ref "U11") (pin "12") (pinfunction "VSS2_12") (pintype "bidirectional"))
      (node (ref "U11") (pin "2") (pinfunction "VSS_2") (pintype "bidirectional"))
      (node (ref "U11") (pin "23") (pinfunction "VSSA/VREFLO_23") (pintype "bidirectional"))
      (node (ref "U11") (pin "3") (pinfunction "/VREGENZ_3") (pintype "bidirectional"))
      (node (ref "U12") (pin "P$3") (pinfunction "GND_P$3") (pintype "bidirectional"))
      (node (ref "U12") (pin "P$6") (pinfunction "GND1_P$6") (pintype "bidirectional"))
      (node (ref "U15") (pin "P$11") (pinfunction "P11_GND_P$11") (pintype "bidirectional"))
      (node (ref "U15") (pin "P$2") (pinfunction "P2_GND_P$2") (pintype "bidirectional"))
      (node (ref "U2") (pin "15") (pinfunction "GND_15") (pintype "bidirectional"))
      (node (ref "U3") (pin "4") (pinfunction "GND_4") (pintype "bidirectional"))
      (node (ref "U4") (pin "15") (pinfunction "GND_15") (pintype "bidirectional"))
      (node (ref "U5") (pin "P$4") (pinfunction "V-_P$4") (pintype "bidirectional"))
      (node (ref "U6") (pin "18") (pinfunction "GND2_18") (pintype "power_in"))
      (node (ref "U6") (pin "21") (pinfunction "GND3_21") (pintype "power_in"))
      (node (ref "U6") (pin "25") (pinfunction "AGND_25") (pintype "power_in"))
      (node (ref "U6") (pin "26") (pinfunction "TEST_26") (pintype "input"))
      (node (ref "U6") (pin "7") (pinfunction "GND1_7") (pintype "power_in"))
      (node (ref "U7") (pin "3") (pinfunction "GND_3") (pintype "bidirectional"))
      (node (ref "U8") (pin "3") (pinfunction "GND_3") (pintype "bidirectional"))
      (node (ref "U9") (pin "3") (pinfunction "GND_3") (pintype "bidirectional"))
      (node (ref "USB_PWR1") (pin "K") (pinfunction "C_K") (pintype "passive"))
      (node (ref "X1") (pin "5") (pinfunction "5_5") (pintype "passive"))
      (node (ref "X1") (pin "G1") (pinfunction "G1_G1") (pintype "passive"))
      (node (ref "X1") (pin "G2") (pinfunction "G2_G2") (pintype "passive"))
      (node (ref "X2") (pin "GND") (pinfunction "GND_GND") (pintype "bidirectional"))
    )
    (net (code "50") (name "GPIO0") (class "Default")
      (node (ref "J122") (pin "P$1") (pinfunction "P$1_P$1") (pintype "bidirectional"))
      (node (ref "J122") (pin "P$2") (pinfunction "P$2_P$2") (pintype "bidirectional"))
      (node (ref "J122") (pin "P$3") (pinfunction "P$3_P$3") (pintype "bidirectional"))
      (node (ref "L1") (pin "P$40") (pinfunction "GPIO0/EPWM1A_P$40") (pintype "bidirectional"))
      (node (ref "SV25") (pin "9") (pinfunction "9_9") (pintype "passive"))
    )
    (net (code "51") (name "GPIO1") (class "Default")
      (node (ref "J121") (pin "P$1") (pinfunction "P$1_P$1") (pintype "bidirectional"))
      (node (ref "J121") (pin "P$2") (pinfunction "P$2_P$2") (pintype "bidirectional"))
      (node (ref "J121") (pin "P$3") (pinfunction "P$3_P$3") (pintype "bidirectional"))
      (node (ref "L1") (pin "P$39") (pinfunction "GPIO1/EPWM1B_P$39") (pintype "bidirectional"))
      (node (ref "SV25") (pin "7") (pinfunction "7_7") (pintype "passive"))
    )
    (net (code "52") (name "GPIO2") (class "Default")
      (node (ref "J120") (pin "P$1") (pinfunction "P$1_P$1") (pintype "bidirectional"))
      (node (ref "J120") (pin "P$2") (pinfunction "P$2_P$2") (pintype "bidirectional"))
      (node (ref "J120") (pin "P$3") (pinfunction "P$3_P$3") (pintype "bidirectional"))
      (node (ref "L1") (pin "P$38") (pinfunction "GPIO2/EPWM2A_P$38") (pintype "bidirectional"))
      (node (ref "SV25") (pin "5") (pinfunction "5_5") (pintype "passive"))
    )
    (net (code "53") (name "GPIO3") (class "Default")
      (node (ref "J119") (pin "P$1") (pinfunction "P$1_P$1") (pintype "bidirectional"))
      (node (ref "J119") (pin "P$2") (pinfunction "P$2_P$2") (pintype "bidirectional"))
      (node (ref "J119") (pin "P$3") (pinfunction "P$3_P$3") (pintype "bidirectional"))
      (node (ref "L1") (pin "P$37") (pinfunction "GPIO3/EPWM2B_P$37") (pintype "bidirectional"))
      (node (ref "SV25") (pin "10") (pinfunction "10_10") (pintype "passive"))
    )
    (net (code "54") (name "GPIO4") (class "Default")
      (node (ref "J118") (pin "P$1") (pinfunction "P$1_P$1") (pintype "bidirectional"))
      (node (ref "J118") (pin "P$2") (pinfunction "P$2_P$2") (pintype "bidirectional"))
      (node (ref "J118") (pin "P$3") (pinfunction "P$3_P$3") (pintype "bidirectional"))
      (node (ref "L1") (pin "P$36") (pinfunction "GPIO4/EPWM3A_P$36") (pintype "bidirectional"))
      (node (ref "SV25") (pin "8") (pinfunction "8_8") (pintype "passive"))
    )
    (net (code "55") (name "GPIO5") (class "Default")
      (node (ref "J117") (pin "P$1") (pinfunction "P$1_P$1") (pintype "bidirectional"))
      (node (ref "J117") (pin "P$2") (pinfunction "P$2_P$2") (pintype "bidirectional"))
      (node (ref "J117") (pin "P$3") (pinfunction "P$3_P$3") (pintype "bidirectional"))
      (node (ref "L1") (pin "P$35") (pinfunction "GPIO5/EPWM3B_P$35") (pintype "bidirectional"))
      (node (ref "SV25") (pin "6") (pinfunction "6_6") (pintype "passive"))
    )
    (net (code "56") (name "GPIO6") (class "Default")
      (node (ref "IC2") (pin "17") (pinfunction "B2_17") (pintype "bidirectional"))
      (node (ref "J133") (pin "P$1") (pinfunction "P$1_P$1") (pintype "bidirectional"))
      (node (ref "J133") (pin "P$2") (pinfunction "P$2_P$2") (pintype "bidirectional"))
      (node (ref "J133") (pin "P$3") (pinfunction "P$3_P$3") (pintype "bidirectional"))
      (node (ref "L1") (pin "P$80") (pinfunction "GPIO6/EPWM4A_P$80") (pintype "bidirectional"))
    )
    (net (code "57") (name "GPIO7") (class "Default")
      (node (ref "IC2") (pin "15") (pinfunction "B1_15") (pintype "bidirectional"))
      (node (ref "J134") (pin "P$1") (pinfunction "P$1_P$1") (pintype "bidirectional"))
      (node (ref "J134") (pin "P$2") (pinfunction "P$2_P$2") (pintype "bidirectional"))
      (node (ref "J134") (pin "P$3") (pinfunction "P$3_P$3") (pintype "bidirectional"))
      (node (ref "L1") (pin "P$79") (pinfunction "GPIO7/EPWM4B_P$79") (pintype "bidirectional"))
    )
    (net (code "58") (name "GPIO8") (class "Default")
      (node (ref "J135") (pin "P$1") (pinfunction "P$1_P$1") (pintype "bidirectional"))
      (node (ref "J135") (pin "P$2") (pinfunction "P$2_P$2") (pintype "bidirectional"))
      (node (ref "J135") (pin "P$3") (pinfunction "P$3_P$3") (pintype "bidirectional"))
      (node (ref "L1") (pin "P$78") (pinfunction "GPIO8/EPWM5A_P$78") (pintype "bidirectional"))
      (node (ref "SV26") (pin "9") (pinfunction "9_9") (pintype "passive"))
    )
    (net (code "59") (name "GPIO9") (class "Default")
      (node (ref "J136") (pin "P$1") (pinfunction "P$1_P$1") (pintype "bidirectional"))
      (node (ref "J136") (pin "P$2") (pinfunction "P$2_P$2") (pintype "bidirectional"))
      (node (ref "J136") (pin "P$3") (pinfunction "P$3_P$3") (pintype "bidirectional"))
      (node (ref "L1") (pin "P$77") (pinfunction "GPIO9/EPWM5B_P$77") (pintype "bidirectional"))
      (node (ref "SV26") (pin "7") (pinfunction "7_7") (pintype "passive"))
    )
    (net (code "60") (name "GPIO10") (class "Default")
      (node (ref "J137") (pin "P$1") (pinfunction "P$1_P$1") (pintype "bidirectional"))
      (node (ref "J137") (pin "P$2") (pinfunction "P$2_P$2") (pintype "bidirectional"))
      (node (ref "J137") (pin "P$3") (pinfunction "P$3_P$3") (pintype "bidirectional"))
      (node (ref "L1") (pin "P$76") (pinfunction "GPIO10/EPWM6A_P$76") (pintype "bidirectional"))
      (node (ref "SV26") (pin "5") (pinfunction "5_5") (pintype "passive"))
    )
    (net (code "61") (name "GPIO11") (class "Default")
      (node (ref "J138") (pin "P$1") (pinfunction "P$1_P$1") (pintype "bidirectional"))
      (node (ref "J138") (pin "P$2") (pinfunction "P$2_P$2") (pintype "bidirectional"))
      (node (ref "J138") (pin "P$3") (pinfunction "P$3_P$3") (pintype "bidirectional"))
      (node (ref "L1") (pin "P$75") (pinfunction "GPIO11/EPWM6B_P$75") (pintype "bidirectional"))
    )
    (net (code "62") (name "GPIO14") (class "Default")
      (node (ref "J139") (pin "P$1") (pinfunction "P$1_P$1") (pintype "bidirectional"))
      (node (ref "J139") (pin "P$2") (pinfunction "P$2_P$2") (pintype "bidirectional"))
      (node (ref "J139") (pin "P$3") (pinfunction "P$3_P$3") (pintype "bidirectional"))
      (node (ref "L1") (pin "P$74") (pinfunction "GPIO14_P$74") (pintype "bidirectional"))
    )
    (net (code "63") (name "GPIO15") (class "Default")
      (node (ref "J140") (pin "P$1") (pinfunction "P$1_P$1") (pintype "bidirectional"))
      (node (ref "J140") (pin "P$2") (pinfunction "P$2_P$2") (pintype "bidirectional"))
      (node (ref "J140") (pin "P$3") (pinfunction "P$3_P$3") (pintype "bidirectional"))
      (node (ref "L1") (pin "P$73") (pinfunction "GPIO15_P$73") (pintype "bidirectional"))
    )
    (net (code "64") (name "GPIO16") (class "Default")
      (node (ref "J115") (pin "P$1") (pinfunction "P$1_P$1") (pintype "bidirectional"))
      (node (ref "J115") (pin "P$2") (pinfunction "P$2_P$2") (pintype "bidirectional"))
      (node (ref "J115") (pin "P$3") (pinfunction "P$3_P$3") (pintype "bidirectional"))
      (node (ref "L1") (pin "P$33") (pinfunction "GPIO16_P$33") (pintype "bidirectional"))
      (node (ref "SV41") (pin "1") (pinfunction "1_1") (pintype "passive"))
    )
    (net (code "65") (name "GPIO18") (class "Default")
      (node (ref "J16") (pin "P$1") (pinfunction "P$1_P$1") (pintype "bidirectional"))
      (node (ref "J16") (pin "P$2") (pinfunction "P$2_P$2") (pintype "bidirectional"))
      (node (ref "J16") (pin "P$3") (pinfunction "P$3_P$3") (pintype "bidirectional"))
      (node (ref "L1") (pin "P$4") (pinfunction "GPIO18/SCITXDB_P$4") (pintype "bidirectional"))
      (node (ref "U3") (pin "6") (pinfunction "SCK_6") (pintype "bidirectional"))
    )
    (net (code "66") (name "GPIO19") (class "Default")
      (node (ref "J15") (pin "P$1") (pinfunction "P$1_P$1") (pintype "bidirectional"))
      (node (ref "J15") (pin "P$2") (pinfunction "P$2_P$2") (pintype "bidirectional"))
      (node (ref "J15") (pin "P$3") (pinfunction "P$3_P$3") (pintype "bidirectional"))
      (node (ref "L1") (pin "P$3") (pinfunction "GPIO19/SCIRXDB_P$3") (pintype "bidirectional"))
      (node (ref "U3") (pin "1") (pinfunction "~{CS}_1") (pintype "bidirectional"))
    )
    (net (code "67") (name "GPIO22") (class "Default")
      (node (ref "J20") (pin "P$1") (pinfunction "P$1_P$1") (pintype "bidirectional"))
      (node (ref "J20") (pin "P$2") (pinfunction "P$2_P$2") (pintype "bidirectional"))
      (node (ref "J20") (pin "P$3") (pinfunction "P$3_P$3") (pintype "bidirectional"))
      (node (ref "L1") (pin "P$8") (pinfunction "GPIO22_P$8") (pintype "bidirectional"))
      (node (ref "SV41") (pin "3") (pinfunction "3_3") (pintype "passive"))
    )
    (net (code "68") (name "GPIO24") (class "Default")
      (node (ref "J116") (pin "P$1") (pinfunction "P$1_P$1") (pintype "bidirectional"))
      (node (ref "J116") (pin "P$2") (pinfunction "P$2_P$2") (pintype "bidirectional"))
      (node (ref "J116") (pin "P$3") (pinfunction "P$3_P$3") (pintype "bidirectional"))
      (node (ref "J9") (pin "P$1") (pinfunction "P$1_P$1") (pintype "bidirectional"))
      (node (ref "J9") (pin "P$2") (pinfunction "P$2_P$2") (pintype "bidirectional"))
      (node (ref "L1") (pin "P$34") (pinfunction "GPIO24_P$34") (pintype "bidirectional"))
    )
    (net (code "69") (name "GPIO25") (class "Default")
      (node (ref "IC2") (pin "6") (pinfunction "B3_6") (pintype "bidirectional"))
      (node (ref "J162") (pin "P$1") (pinfunction "P$1_P$1") (pintype "bidirectional"))
      (node (ref "J162") (pin "P$2") (pinfunction "P$2_P$2") (pintype "bidirectional"))
      (node (ref "J162") (pin "P$3") (pinfunction "P$3_P$3") (pintype "bidirectional"))
      (node (ref "L1") (pin "P$51") (pinfunction "GPIO25_P$51") (pintype "bidirectional"))
    )
    (net (code "70") (name "GPIO26") (class "Default")
      (node (ref "IC2") (pin "4") (pinfunction "B2_4") (pintype "bidirectional"))
      (node (ref "J160") (pin "P$1") (pinfunction "P$1_P$1") (pintype "bidirectional"))
      (node (ref "J160") (pin "P$2") (pinfunction "P$2_P$2") (pintype "bidirectional"))
      (node (ref "J160") (pin "P$3") (pinfunction "P$3_P$3") (pintype "bidirectional"))
      (node (ref "L1") (pin "P$53") (pinfunction "GPIO26_P$53") (pintype "bidirectional"))
    )
    (net (code "71") (name "GPIO27") (class "Default")
      (node (ref "J11") (pin "P$1") (pinfunction "P$1_P$1") (pintype "bidirectional"))
      (node (ref "J11") (pin "P$2") (pinfunction "P$2_P$2") (pintype "bidirectional"))
      (node (ref "J161") (pin "P$1") (pinfunction "P$1_P$1") (pintype "bidirectional"))
      (node (ref "J161") (pin "P$2") (pinfunction "P$2_P$2") (pintype "bidirectional"))
      (node (ref "J161") (pin "P$3") (pinfunction "P$3_P$3") (pintype "bidirectional"))
      (node (ref "L1") (pin "P$52") (pinfunction "GPIO27_P$52") (pintype "bidirectional"))
    )
    (net (code "72") (name "GPIO29") (class "Default")
      (node (ref "J29") (pin "P$1") (pinfunction "P$1_P$1") (pintype "bidirectional"))
      (node (ref "J29") (pin "P$2") (pinfunction "P$2_P$2") (pintype "bidirectional"))
      (node (ref "J29") (pin "P$3") (pinfunction "P$3_P$3") (pintype "bidirectional"))
      (node (ref "J37") (pin "P$2") (pinfunction "P$2_P$2") (pintype "bidirectional"))
      (node (ref "L1") (pin "P$11") (pinfunction "GPIO29_P$11") (pintype "bidirectional"))
    )
    (net (code "73") (name "GPIO32") (class "Default")
      (node (ref "J14") (pin "P$1") (pinfunction "P$1_P$1") (pintype "bidirectional"))
      (node (ref "J14") (pin "P$2") (pinfunction "P$2_P$2") (pintype "bidirectional"))
      (node (ref "J14") (pin "P$3") (pinfunction "P$3_P$3") (pintype "bidirectional"))
      (node (ref "L1") (pin "P$2") (pinfunction "GPIO32_P$2") (pintype "bidirectional"))
    )
    (net (code "74") (name "GPIO40") (class "Default")
      (node (ref "J163") (pin "P$1") (pinfunction "P$1_P$1") (pintype "bidirectional"))
      (node (ref "J163") (pin "P$2") (pinfunction "P$2_P$2") (pintype "bidirectional"))
      (node (ref "J163") (pin "P$3") (pinfunction "P$3_P$3") (pintype "bidirectional"))
      (node (ref "L1") (pin "P$50") (pinfunction "GPIO40/SDAB_P$50") (pintype "bidirectional"))
      (node (ref "R17") (pin "1") (pinfunction "1_1") (pintype "passive"))
      (node (ref "SV10") (pin "3") (pinfunction "3_3") (pintype "passive"))
      (node (ref "SV30") (pin "3") (pinfunction "3_3") (pintype "passive"))
    )
    (net (code "75") (name "GPIO41") (class "Default")
      (node (ref "J164") (pin "P$1") (pinfunction "P$1_P$1") (pintype "bidirectional"))
      (node (ref "J164") (pin "P$2") (pinfunction "P$2_P$2") (pintype "bidirectional"))
      (node (ref "J164") (pin "P$3") (pinfunction "P$3_P$3") (pintype "bidirectional"))
      (node (ref "L1") (pin "P$49") (pinfunction "GPIO41/SCLB_P$49") (pintype "bidirectional"))
      (node (ref "R18") (pin "1") (pinfunction "1_1") (pintype "passive"))
      (node (ref "SV10") (pin "5") (pinfunction "5_5") (pintype "passive"))
      (node (ref "SV30") (pin "5") (pinfunction "5_5") (pintype "passive"))
    )
    (net (code "76") (name "GPIO52") (class "Default")
      (node (ref "J165") (pin "P$1") (pinfunction "P$1_P$1") (pintype "bidirectional"))
      (node (ref "J165") (pin "P$2") (pinfunction "P$2_P$2") (pintype "bidirectional"))
      (node (ref "J165") (pin "P$3") (pinfunction "P$3_P$3") (pintype "bidirectional"))
      (node (ref "L1") (pin "P$48") (pinfunction "GPIO52_P$48") (pintype "bidirectional"))
    )
    (net (code "77") (name "GPIO56") (class "Default")
      (node (ref "J169") (pin "P$1") (pinfunction "P$1_P$1") (pintype "bidirectional"))
      (node (ref "J169") (pin "P$2") (pinfunction "P$2_P$2") (pintype "bidirectional"))
      (node (ref "J169") (pin "P$3") (pinfunction "P$3_P$3") (pintype "bidirectional"))
      (node (ref "L1") (pin "P$44") (pinfunction "GPIO56/SCITXDC_P$44") (pintype "bidirectional"))
    )
    (net (code "78") (name "GPIO58") (class "Default")
      (node (ref "J33") (pin "P$1") (pinfunction "P$1_P$1") (pintype "bidirectional"))
      (node (ref "J33") (pin "P$2") (pinfunction "P$2_P$2") (pintype "bidirectional"))
      (node (ref "J33") (pin "P$3") (pinfunction "P$3_P$3") (pintype "bidirectional"))
      (node (ref "L1") (pin "P$15") (pinfunction "GPIO58/SPISIMOA_P$15") (pintype "bidirectional"))
      (node (ref "U3") (pin "5") (pinfunction "SI_5") (pintype "bidirectional"))
    )
    (net (code "79") (name "GPIO59") (class "Default")
      (node (ref "J32") (pin "P$1") (pinfunction "P$1_P$1") (pintype "bidirectional"))
      (node (ref "J32") (pin "P$2") (pinfunction "P$2_P$2") (pintype "bidirectional"))
      (node (ref "J32") (pin "P$3") (pinfunction "P$3_P$3") (pintype "bidirectional"))
      (node (ref "L1") (pin "P$14") (pinfunction "GPIO59/SPISOMIA_P$14") (pintype "bidirectional"))
      (node (ref "U3") (pin "2") (pinfunction "SO_2") (pintype "bidirectional"))
    )
    (net (code "80") (name "GPIO60") (class "Default")
      (node (ref "J19") (pin "P$1") (pinfunction "P$1_P$1") (pintype "bidirectional"))
      (node (ref "J19") (pin "P$2") (pinfunction "P$2_P$2") (pintype "bidirectional"))
      (node (ref "J19") (pin "P$3") (pinfunction "P$3_P$3") (pintype "bidirectional"))
      (node (ref "L1") (pin "P$7") (pinfunction "GPIO60/SPICLKA_P$7") (pintype "bidirectional"))
    )
    (net (code "81") (name "GPIO61") (class "Default")
      (node (ref "J101") (pin "P$1") (pinfunction "P$1_P$1") (pintype "bidirectional"))
      (node (ref "J101") (pin "P$2") (pinfunction "P$2_P$2") (pintype "bidirectional"))
      (node (ref "J101") (pin "P$3") (pinfunction "P$3_P$3") (pintype "bidirectional"))
      (node (ref "L1") (pin "P$19") (pinfunction "GPIO61_P$19") (pintype "bidirectional"))
    )
    (net (code "82") (name "GPIO63") (class "Default")
      (node (ref "IC2") (pin "19") (pinfunction "B3_19") (pintype "bidirectional"))
      (node (ref "J158") (pin "P$1") (pinfunction "P$1_P$1") (pintype "bidirectional"))
      (node (ref "J158") (pin "P$2") (pinfunction "P$2_P$2") (pintype "bidirectional"))
      (node (ref "J158") (pin "P$3") (pinfunction "P$3_P$3") (pintype "bidirectional"))
      (node (ref "J204") (pin "P$1") (pinfunction "P$1_P$1") (pintype "bidirectional"))
      (node (ref "J204") (pin "P$2") (pinfunction "P$2_P$2") (pintype "bidirectional"))
      (node (ref "J36") (pin "P$2") (pinfunction "P$2_P$2") (pintype "bidirectional"))
      (node (ref "L1") (pin "P$55") (pinfunction "GPIO63/SPISIMOB_P$55") (pintype "bidirectional"))
    )
    (net (code "83") (name "GPIO64") (class "Default")
      (node (ref "IC2") (pin "21") (pinfunction "B4_21") (pintype "bidirectional"))
      (node (ref "J159") (pin "P$1") (pinfunction "P$1_P$1") (pintype "bidirectional"))
      (node (ref "J159") (pin "P$2") (pinfunction "P$2_P$2") (pintype "bidirectional"))
      (node (ref "J159") (pin "P$3") (pinfunction "P$3_P$3") (pintype "bidirectional"))
      (node (ref "J205") (pin "P$1") (pinfunction "P$1_P$1") (pintype "bidirectional"))
      (node (ref "J205") (pin "P$2") (pinfunction "P$2_P$2") (pintype "bidirectional"))
      (node (ref "J35") (pin "P$2") (pinfunction "P$2_P$2") (pintype "bidirectional"))
      (node (ref "L1") (pin "P$54") (pinfunction "GPIO64/SPISOMIB_P$54") (pintype "bidirectional"))
    )
    (net (code "84") (name "GPIO65") (class "Default")
      (node (ref "IC2") (pin "23") (pinfunction "B5_23") (pintype "bidirectional"))
      (node (ref "J166") (pin "P$1") (pinfunction "P$1_P$1") (pintype "bidirectional"))
      (node (ref "J166") (pin "P$2") (pinfunction "P$2_P$2") (pintype "bidirectional"))
      (node (ref "J166") (pin "P$3") (pinfunction "P$3_P$3") (pintype "bidirectional"))
      (node (ref "J206") (pin "P$1") (pinfunction "P$1_P$1") (pintype "bidirectional"))
      (node (ref "J206") (pin "P$2") (pinfunction "P$2_P$2") (pintype "bidirectional"))
      (node (ref "J38") (pin "P$2") (pinfunction "P$2_P$2") (pintype "bidirectional"))
      (node (ref "L1") (pin "P$47") (pinfunction "GPIO65/SPICLKB_P$47") (pintype "bidirectional"))
    )
    (net (code "85") (name "GPIO66") (class "Default")
      (node (ref "J154") (pin "P$1") (pinfunction "P$1_P$1") (pintype "bidirectional"))
      (node (ref "J154") (pin "P$2") (pinfunction "P$2_P$2") (pintype "bidirectional"))
      (node (ref "J154") (pin "P$3") (pinfunction "P$3_P$3") (pintype "bidirectional"))
      (node (ref "J207") (pin "P$1") (pinfunction "P$1_P$1") (pintype "bidirectional"))
      (node (ref "J207") (pin "P$2") (pinfunction "P$2_P$2") (pintype "bidirectional"))
      (node (ref "L1") (pin "P$59") (pinfunction "GPIO66_P$59") (pintype "bidirectional"))
    )
    (net (code "86") (name "GPIO67") (class "Default")
      (node (ref "J17") (pin "P$1") (pinfunction "P$1_P$1") (pintype "bidirectional"))
      (node (ref "J17") (pin "P$2") (pinfunction "P$2_P$2") (pintype "bidirectional"))
      (node (ref "J17") (pin "P$3") (pinfunction "P$3_P$3") (pintype "bidirectional"))
      (node (ref "L1") (pin "P$5") (pinfunction "GPIO67_P$5") (pintype "bidirectional"))
    )
    (net (code "87") (name "GPIO94") (class "Default")
      (node (ref "J167") (pin "P$1") (pinfunction "P$1_P$1") (pintype "bidirectional"))
      (node (ref "J167") (pin "P$2") (pinfunction "P$2_P$2") (pintype "bidirectional"))
      (node (ref "J167") (pin "P$3") (pinfunction "P$3_P$3") (pintype "bidirectional"))
      (node (ref "L1") (pin "P$46") (pinfunction "GPIO94_P$46") (pintype "bidirectional"))
      (node (ref "SV41") (pin "5") (pinfunction "5_5") (pintype "passive"))
    )
    (net (code "88") (name "GPIO95") (class "Default")
      (node (ref "J176") (pin "P$1") (pinfunction "P$1_P$1") (pintype "bidirectional"))
      (node (ref "J176") (pin "P$2") (pinfunction "P$2_P$2") (pintype "bidirectional"))
      (node (ref "J176") (pin "P$3") (pinfunction "P$3_P$3") (pintype "bidirectional"))
      (node (ref "L1") (pin "P$42") (pinfunction "GPIO95_P$42") (pintype "bidirectional"))
      (node (ref "SV41") (pin "7") (pinfunction "7_7") (pintype "passive"))
    )
    (net (code "89") (name "GPIO97") (class "Default")
      (node (ref "J168") (pin "P$1") (pinfunction "P$1_P$1") (pintype "bidirectional"))
      (node (ref "J168") (pin "P$2") (pinfunction "P$2_P$2") (pintype "bidirectional"))
      (node (ref "J168") (pin "P$3") (pinfunction "P$3_P$3") (pintype "bidirectional"))
      (node (ref "L1") (pin "P$45") (pinfunction "GPIO97_P$45") (pintype "bidirectional"))
      (node (ref "SV41") (pin "9") (pinfunction "9_9") (pintype "passive"))
    )
    (net (code "90") (name "GPIO104") (class "Default")
      (node (ref "J28") (pin "P$1") (pinfunction "P$1_P$1") (pintype "bidirectional"))
      (node (ref "J28") (pin "P$2") (pinfunction "P$2_P$2") (pintype "bidirectional"))
      (node (ref "J28") (pin "P$3") (pinfunction "P$3_P$3") (pintype "bidirectional"))
      (node (ref "L1") (pin "P$10") (pinfunction "GPIO104/SDAA_P$10") (pintype "bidirectional"))
    )
    (net (code "91") (name "GPIO105") (class "Default")
      (node (ref "J21") (pin "P$1") (pinfunction "P$1_P$1") (pintype "bidirectional"))
      (node (ref "J21") (pin "P$2") (pinfunction "P$2_P$2") (pintype "bidirectional"))
      (node (ref "J21") (pin "P$3") (pinfunction "P$3_P$3") (pintype "bidirectional"))
      (node (ref "L1") (pin "P$9") (pinfunction "GPIO105/SCLA_P$9") (pintype "bidirectional"))
    )
    (net (code "92") (name "GPIO111") (class "Default")
      (node (ref "J18") (pin "P$1") (pinfunction "P$1_P$1") (pintype "bidirectional"))
      (node (ref "J18") (pin "P$2") (pinfunction "P$2_P$2") (pintype "bidirectional"))
      (node (ref "J18") (pin "P$3") (pinfunction "P$3_P$3") (pintype "bidirectional"))
      (node (ref "L1") (pin "P$6") (pinfunction "GPIO111_P$6") (pintype "bidirectional"))
      (node (ref "SV41") (pin "11") (pinfunction "11_11") (pintype "passive"))
    )
    (net (code "93") (name "GPIO122") (class "Default")
      (node (ref "J66") (pin "P$1") (pinfunction "P$1_P$1") (pintype "bidirectional"))
      (node (ref "J66") (pin "P$2") (pinfunction "P$2_P$2") (pintype "bidirectional"))
      (node (ref "J99") (pin "P$1") (pinfunction "P$1_P$1") (pintype "bidirectional"))
      (node (ref "J99") (pin "P$2") (pinfunction "P$2_P$2") (pintype "bidirectional"))
      (node (ref "J99") (pin "P$3") (pinfunction "P$3_P$3") (pintype "bidirectional"))
      (node (ref "L1") (pin "P$17") (pinfunction "GPIO122_P$17") (pintype "bidirectional"))
    )
    (net (code "94") (name "GPIO123") (class "Default")
      (node (ref "J100") (pin "P$1") (pinfunction "P$1_P$1") (pintype "bidirectional"))
      (node (ref "J100") (pin "P$2") (pinfunction "P$2_P$2") (pintype "bidirectional"))
      (node (ref "J100") (pin "P$3") (pinfunction "P$3_P$3") (pintype "bidirectional"))
      (node (ref "J67") (pin "P$1") (pinfunction "P$1_P$1") (pintype "bidirectional"))
      (node (ref "J67") (pin "P$2") (pinfunction "P$2_P$2") (pintype "bidirectional"))
      (node (ref "L1") (pin "P$18") (pinfunction "GPIO123_P$18") (pintype "bidirectional"))
    )
    (net (code "95") (name "GPIO124") (class "Default")
      (node (ref "J31") (pin "P$1") (pinfunction "P$1_P$1") (pintype "bidirectional"))
      (node (ref "J31") (pin "P$2") (pinfunction "P$2_P$2") (pintype "bidirectional"))
      (node (ref "J31") (pin "P$3") (pinfunction "P$3_P$3") (pintype "bidirectional"))
      (node (ref "J68") (pin "P$1") (pinfunction "P$1_P$1") (pintype "bidirectional"))
      (node (ref "J68") (pin "P$2") (pinfunction "P$2_P$2") (pintype "bidirectional"))
      (node (ref "L1") (pin "P$13") (pinfunction "GPIO124_P$13") (pintype "bidirectional"))
    )
    (net (code "96") (name "GPIO125") (class "Default")
      (node (ref "J30") (pin "P$1") (pinfunction "P$1_P$1") (pintype "bidirectional"))
      (node (ref "J30") (pin "P$2") (pinfunction "P$2_P$2") (pintype "bidirectional"))
      (node (ref "J30") (pin "P$3") (pinfunction "P$3_P$3") (pintype "bidirectional"))
      (node (ref "J69") (pin "P$1") (pinfunction "P$1_P$1") (pintype "bidirectional"))
      (node (ref "J69") (pin "P$2") (pinfunction "P$2_P$2") (pintype "bidirectional"))
      (node (ref "L1") (pin "P$12") (pinfunction "GPIO125_P$12") (pintype "bidirectional"))
    )
    (net (code "97") (name "GPIO130") (class "Default")
      (node (ref "IC2") (pin "10") (pinfunction "B5_10") (pintype "bidirectional"))
      (node (ref "J156") (pin "P$1") (pinfunction "P$1_P$1") (pintype "bidirectional"))
      (node (ref "J156") (pin "P$2") (pinfunction "P$2_P$2") (pintype "bidirectional"))
      (node (ref "J156") (pin "P$3") (pinfunction "P$3_P$3") (pintype "bidirectional"))
      (node (ref "L1") (pin "P$57") (pinfunction "GPIO130_P$57") (pintype "bidirectional"))
    )
    (net (code "98") (name "GPIO131") (class "Default")
      (node (ref "IC2") (pin "8") (pinfunction "B4_8") (pintype "bidirectional"))
      (node (ref "J155") (pin "P$1") (pinfunction "P$1_P$1") (pintype "bidirectional"))
      (node (ref "J155") (pin "P$2") (pinfunction "P$2_P$2") (pintype "bidirectional"))
      (node (ref "J155") (pin "P$3") (pinfunction "P$3_P$3") (pintype "bidirectional"))
      (node (ref "L1") (pin "P$58") (pinfunction "GPIO131_P$58") (pintype "bidirectional"))
    )
    (net (code "99") (name "GPIO139") (class "Default")
      (node (ref "J170") (pin "P$1") (pinfunction "P$1_P$1") (pintype "bidirectional"))
      (node (ref "J170") (pin "P$2") (pinfunction "P$2_P$2") (pintype "bidirectional"))
      (node (ref "J170") (pin "P$3") (pinfunction "P$3_P$3") (pintype "bidirectional"))
      (node (ref "L1") (pin "P$43") (pinfunction "GPIO139/SCIRXDC_P$43") (pintype "bidirectional"))
    )
    (net (code "100") (name "GPIO157") (class "Default")
      (node (ref "J141") (pin "P$1") (pinfunction "P$1_P$1") (pintype "bidirectional"))
      (node (ref "J141") (pin "P$2") (pinfunction "P$2_P$2") (pintype "bidirectional"))
      (node (ref "J141") (pin "P$3") (pinfunction "P$3_P$3") (pintype "bidirectional"))
      (node (ref "L1") (pin "P$72") (pinfunction "DAC3_P$72") (pintype "bidirectional"))
      (node (ref "R19") (pin "1") (pinfunction "1_1") (pintype "passive"))
      (node (ref "SV64") (pin "1") (pinfunction "1_1") (pintype "passive"))
      (node (ref "SV64") (pin "2") (pinfunction "2_2") (pintype "passive"))
      (node (ref "SV64") (pin "3") (pinfunction "3_3") (pintype "passive"))
    )
    (net (code "101") (name "GPIO158") (class "Default")
      (node (ref "J142") (pin "P$1") (pinfunction "P$1_P$1") (pintype "bidirectional"))
      (node (ref "J142") (pin "P$2") (pinfunction "P$2_P$2") (pintype "bidirectional"))
      (node (ref "J142") (pin "P$3") (pinfunction "P$3_P$3") (pintype "bidirectional"))
      (node (ref "L1") (pin "P$71") (pinfunction "DAC4_P$71") (pintype "bidirectional"))
      (node (ref "R20") (pin "1") (pinfunction "1_1") (pintype "passive"))
      (node (ref "SV65") (pin "1") (pinfunction "1_1") (pintype "passive"))
      (node (ref "SV65") (pin "2") (pinfunction "2_2") (pintype "passive"))
      (node (ref "SV65") (pin "3") (pinfunction "3_3") (pintype "passive"))
    )
    (net (code "102") (name "GPIO159") (class "Default")
      (node (ref "J114") (pin "P$1") (pinfunction "P$1_P$1") (pintype "bidirectional"))
      (node (ref "J114") (pin "P$2") (pinfunction "P$2_P$2") (pintype "bidirectional"))
      (node (ref "J114") (pin "P$3") (pinfunction "P$3_P$3") (pintype "bidirectional"))
      (node (ref "L1") (pin "P$32") (pinfunction "DAC1_P$32") (pintype "bidirectional"))
      (node (ref "R23") (pin "1") (pinfunction "1_1") (pintype "passive"))
      (node (ref "SV66") (pin "1") (pinfunction "1_1") (pintype "passive"))
      (node (ref "SV66") (pin "2") (pinfunction "2_2") (pintype "passive"))
      (node (ref "SV66") (pin "3") (pinfunction "3_3") (pintype "passive"))
    )
    (net (code "103") (name "GPIO160") (class "Default")
      (node (ref "J113") (pin "P$1") (pinfunction "P$1_P$1") (pintype "bidirectional"))
      (node (ref "J113") (pin "P$2") (pinfunction "P$2_P$2") (pintype "bidirectional"))
      (node (ref "J113") (pin "P$3") (pinfunction "P$3_P$3") (pintype "bidirectional"))
      (node (ref "L1") (pin "P$31") (pinfunction "DAC2_P$31") (pintype "bidirectional"))
      (node (ref "R24") (pin "1") (pinfunction "1_1") (pintype "passive"))
      (node (ref "SV67") (pin "1") (pinfunction "1_1") (pintype "passive"))
      (node (ref "SV67") (pin "2") (pinfunction "2_2") (pintype "passive"))
      (node (ref "SV67") (pin "3") (pinfunction "3_3") (pintype "passive"))
    )
    (net (code "104") (name "I2C5_SCL") (class "Default")
      (node (ref "R22") (pin "1") (pinfunction "1_1") (pintype "passive"))
      (node (ref "SV12") (pin "5") (pinfunction "5_5") (pintype "passive"))
      (node (ref "SV8") (pin "5") (pinfunction "5_5") (pintype "passive"))
      (node (ref "SV9") (pin "5") (pinfunction "5_5") (pintype "passive"))
    )
    (net (code "105") (name "I2C5_SDA") (class "Default")
      (node (ref "R21") (pin "1") (pinfunction "1_1") (pintype "passive"))
      (node (ref "SV12") (pin "3") (pinfunction "3_3") (pintype "passive"))
      (node (ref "SV8") (pin "3") (pinfunction "3_3") (pintype "passive"))
      (node (ref "SV9") (pin "3") (pinfunction "3_3") (pintype "passive"))
    )
    (net (code "106") (name "LINUX_RX") (class "Default")
      (node (ref "SV1") (pin "3") (pinfunction "3_3") (pintype "passive"))
      (node (ref "SV1") (pin "4") (pinfunction "4_4") (pintype "passive"))
      (node (ref "U2") (pin "12") (pinfunction "ROUT1_12") (pintype "bidirectional"))
    )
    (net (code "107") (name "LINUX_TX") (class "Default")
      (node (ref "SV1") (pin "5") (pinfunction "5_5") (pintype "passive"))
      (node (ref "SV1") (pin "6") (pinfunction "6_6") (pintype "passive"))
      (node (ref "U2") (pin "11") (pinfunction "DIN1_11") (pintype "bidirectional"))
    )
    (net (code "108") (name "MISO_5V") (class "Default")
      (node (ref "IC2") (pin "20") (pinfunction "A4_20") (pintype "bidirectional"))
      (node (ref "U10") (pin "6") (pinfunction "MISO_6") (pintype "bidirectional"))
      (node (ref "U7") (pin "6") (pinfunction "MISO_6") (pintype "bidirectional"))
      (node (ref "U8") (pin "6") (pinfunction "MISO_6") (pintype "bidirectional"))
      (node (ref "U9") (pin "6") (pinfunction "MISO_6") (pintype "bidirectional"))
    )
    (net (code "109") (name "MOSI_5V") (class "Default")
      (node (ref "IC2") (pin "18") (pinfunction "A3_18") (pintype "bidirectional"))
      (node (ref "U10") (pin "7") (pinfunction "MOSI_7") (pintype "bidirectional"))
      (node (ref "U7") (pin "7") (pinfunction "MOSI_7") (pintype "bidirectional"))
      (node (ref "U8") (pin "7") (pinfunction "MOSI_7") (pintype "bidirectional"))
      (node (ref "U9") (pin "7") (pinfunction "MOSI_7") (pintype "bidirectional"))
    )
    (net (code "110") (name "Net-(B1-PadP$1)") (class "Default")
      (node (ref "B1") (pin "P$1") (pinfunction "P$1_P$1") (pintype "bidirectional"))
      (node (ref "R1") (pin "1") (pinfunction "1_1") (pintype "passive"))
    )
    (net (code "111") (name "Net-(B4-P1)") (class "Default")
      (node (ref "B4") (pin "P$1") (pinfunction "P1_P$1") (pintype "bidirectional"))
      (node (ref "SV14") (pin "1") (pinfunction "1_1") (pintype "passive"))
      (node (ref "U5") (pin "P$1") (pinfunction "IN1_P$1") (pintype "bidirectional"))
    )
    (net (code "112") (name "Net-(B5-P1)") (class "Default")
      (node (ref "B5") (pin "P$1") (pinfunction "P1_P$1") (pintype "bidirectional"))
      (node (ref "SV13") (pin "2") (pinfunction "2_2") (pintype "passive"))
      (node (ref "U5") (pin "P$6") (pinfunction "OUT2_P$6") (pintype "bidirectional"))
    )
    (net (code "113") (name "Net-(C27-Pad1)") (class "Default")
      (node (ref "C27") (pin "1") (pinfunction "1_1") (pintype "passive"))
      (node (ref "L2") (pin "1") (pinfunction "1_1") (pintype "passive"))
      (node (ref "X2") (pin "VBUS") (pinfunction "VBUS_VBUS") (pintype "bidirectional"))
    )
    (net (code "114") (name "Net-(ETH1-INT{slash})") (class "Default")
      (node (ref "ETH1") (pin "P$6") (pinfunction "INT/_P$6") (pintype "bidirectional"))
      (node (ref "SV7") (pin "7") (pinfunction "7_7") (pintype "passive"))
      (node (ref "SV7") (pin "8") (pinfunction "8_8") (pintype "passive"))
    )
    (net (code "115") (name "Net-(ETH1-MISO)") (class "Default")
      (node (ref "ETH1") (pin "P$7") (pinfunction "MISO_P$7") (pintype "bidirectional"))
      (node (ref "SV7") (pin "10") (pinfunction "10_10") (pintype "passive"))
      (node (ref "SV7") (pin "9") (pinfunction "9_9") (pintype "passive"))
    )
    (net (code "116") (name "Net-(ETH1-MOSI)") (class "Default")
      (node (ref "ETH1") (pin "P$3") (pinfunction "MOSI_P$3") (pintype "bidirectional"))
      (node (ref "SV11") (pin "10") (pinfunction "10_10") (pintype "passive"))
      (node (ref "SV11") (pin "9") (pinfunction "9_9") (pintype "passive"))
    )
    (net (code "117") (name "Net-(ETH1-RESET)") (class "Default")
      (node (ref "ETH1") (pin "P$8") (pinfunction "RESET_P$8") (pintype "bidirectional"))
      (node (ref "SV11") (pin "7") (pinfunction "7_7") (pintype "passive"))
      (node (ref "SV11") (pin "8") (pinfunction "8_8") (pintype "passive"))
    )
    (net (code "118") (name "Net-(ETH1-SCLK)") (class "Default")
      (node (ref "ETH1") (pin "P$4") (pinfunction "SCLK_P$4") (pintype "bidirectional"))
      (node (ref "SV11") (pin "11") (pinfunction "11_11") (pintype "passive"))
      (node (ref "SV11") (pin "12") (pinfunction "12_12") (pintype "passive"))
    )
    (net (code "119") (name "Net-(ETH1-SS{slash})") (class "Default")
      (node (ref "ETH1") (pin "P$5") (pinfunction "SS/_P$5") (pintype "bidirectional"))
      (node (ref "SV7") (pin "11") (pinfunction "11_11") (pintype "passive"))
      (node (ref "SV7") (pin "12") (pinfunction "12_12") (pintype "passive"))
    )
    (net (code "120") (name "Net-(IC3-RATEOUT)") (class "Default")
      (node (ref "IC3") (pin "2") (pinfunction "RATEOUT_2") (pintype "bidirectional"))
      (node (ref "R9") (pin "2") (pinfunction "2_2") (pintype "passive"))
    )
    (net (code "121") (name "Net-(IC4A-I)") (class "Default")
      (node (ref "IC4") (pin "1") (pinfunction "I_1") (pintype "input"))
      (node (ref "SV41") (pin "2") (pinfunction "2_2") (pintype "passive"))
    )
    (net (code "122") (name "Net-(IC4A-O)") (class "Default")
      (node (ref "IC4") (pin "2") (pinfunction "O_2") (pintype "output"))
      (node (ref "R1") (pin "2") (pinfunction "2_2") (pintype "passive"))
    )
    (net (code "123") (name "Net-(IC4B-I)") (class "Default")
      (node (ref "IC4") (pin "3") (pinfunction "I_3") (pintype "input"))
      (node (ref "SV41") (pin "4") (pinfunction "4_4") (pintype "passive"))
    )
    (net (code "124") (name "Net-(IC4B-O)") (class "Default")
      (node (ref "IC4") (pin "4") (pinfunction "O_4") (pintype "output"))
      (node (ref "LED1") (pin "C") (pinfunction "C_C") (pintype "passive"))
    )
    (net (code "125") (name "Net-(IC4C-I)") (class "Default")
      (node (ref "IC4") (pin "5") (pinfunction "I_5") (pintype "input"))
      (node (ref "SV41") (pin "6") (pinfunction "6_6") (pintype "passive"))
    )
    (net (code "126") (name "Net-(IC4C-O)") (class "Default")
      (node (ref "IC4") (pin "6") (pinfunction "O_6") (pintype "output"))
      (node (ref "LED2") (pin "C") (pinfunction "C_C") (pintype "passive"))
    )
    (net (code "127") (name "Net-(IC4D-I)") (class "Default")
      (node (ref "IC4") (pin "9") (pinfunction "I_9") (pintype "input"))
      (node (ref "SV41") (pin "8") (pinfunction "8_8") (pintype "passive"))
    )
    (net (code "128") (name "Net-(IC4D-O)") (class "Default")
      (node (ref "IC4") (pin "8") (pinfunction "O_8") (pintype "output"))
      (node (ref "LED3") (pin "C") (pinfunction "C_C") (pintype "passive"))
    )
    (net (code "129") (name "Net-(IC4E-I)") (class "Default")
      (node (ref "IC4") (pin "11") (pinfunction "I_11") (pintype "input"))
      (node (ref "SV41") (pin "10") (pinfunction "10_10") (pintype "passive"))
    )
    (net (code "130") (name "Net-(IC4E-O)") (class "Default")
      (node (ref "IC4") (pin "10") (pinfunction "O_10") (pintype "output"))
      (node (ref "LED4") (pin "C") (pinfunction "C_C") (pintype "passive"))
    )
    (net (code "131") (name "Net-(IC4F-I)") (class "Default")
      (node (ref "IC4") (pin "13") (pinfunction "I_13") (pintype "input"))
      (node (ref "SV41") (pin "12") (pinfunction "12_12") (pintype "passive"))
    )
    (net (code "132") (name "Net-(IC4F-O)") (class "Default")
      (node (ref "IC4") (pin "12") (pinfunction "O_12") (pintype "output"))
      (node (ref "LED5") (pin "C") (pinfunction "C_C") (pintype "passive"))
    )
    (net (code "133") (name "Net-(J12-PadP$1)") (class "Default")
      (node (ref "J12") (pin "P$1") (pinfunction "P$1_P$1") (pintype "bidirectional"))
      (node (ref "J12") (pin "P$2") (pinfunction "P$2_P$2") (pintype "bidirectional"))
    )
    (net (code "134") (name "Net-(J13-PadP$1)") (class "Default")
      (node (ref "J13") (pin "P$1") (pinfunction "P$1_P$1") (pintype "bidirectional"))
      (node (ref "J13") (pin "P$2") (pinfunction "P$2_P$2") (pintype "bidirectional"))
    )
    (net (code "135") (name "Net-(J22-PadP$1)") (class "Default")
      (node (ref "J22") (pin "P$1") (pinfunction "P$1_P$1") (pintype "bidirectional"))
      (node (ref "J22") (pin "P$2") (pinfunction "P$2_P$2") (pintype "bidirectional"))
    )
    (net (code "136") (name "Net-(LED1-PadA)") (class "Default")
      (node (ref "LED1") (pin "A") (pinfunction "A_A") (pintype "passive"))
      (node (ref "R2") (pin "2") (pinfunction "2_2") (pintype "passive"))
    )
    (net (code "137") (name "Net-(LED2-PadA)") (class "Default")
      (node (ref "LED2") (pin "A") (pinfunction "A_A") (pintype "passive"))
      (node (ref "R3") (pin "2") (pinfunction "2_2") (pintype "passive"))
    )
    (net (code "138") (name "Net-(LED3-PadA)") (class "Default")
      (node (ref "LED3") (pin "A") (pinfunction "A_A") (pintype "passive"))
      (node (ref "R4") (pin "2") (pinfunction "2_2") (pintype "passive"))
    )
    (net (code "139") (name "Net-(LED4-PadA)") (class "Default")
      (node (ref "LED4") (pin "A") (pinfunction "A_A") (pintype "passive"))
      (node (ref "R5") (pin "2") (pinfunction "2_2") (pintype "passive"))
    )
    (net (code "140") (name "Net-(LED5-PadA)") (class "Default")
      (node (ref "LED5") (pin "A") (pinfunction "A_A") (pintype "passive"))
      (node (ref "R6") (pin "2") (pinfunction "2_2") (pintype "passive"))
    )
    (net (code "141") (name "Net-(LED6-PadA)") (class "Default")
      (node (ref "LED6") (pin "A") (pinfunction "A_A") (pintype "passive"))
      (node (ref "R33") (pin "1") (pinfunction "1_1") (pintype "passive"))
    )
    (net (code "142") (name "Net-(LED17-PadA)") (class "Default")
      (node (ref "LED17") (pin "A") (pinfunction "A_A") (pintype "passive"))
      (node (ref "R36") (pin "1") (pinfunction "1_1") (pintype "passive"))
    )
    (net (code "143") (name "Net-(LED_RX1-C)") (class "Default")
      (node (ref "LED_RX1") (pin "K") (pinfunction "C_K") (pintype "passive"))
      (node (ref "U6") (pin "23") (pinfunction "CBUS0_23") (pintype "bidirectional"))
    )
    (net (code "144") (name "Net-(LED_RX1-PadA)") (class "Default")
      (node (ref "LED_RX1") (pin "A") (pinfunction "A_A") (pintype "passive"))
      (node (ref "R30") (pin "1") (pinfunction "1_1") (pintype "passive"))
    )
    (net (code "145") (name "Net-(LED_TX1-C)") (class "Default")
      (node (ref "LED_TX1") (pin "K") (pinfunction "C_K") (pintype "passive"))
      (node (ref "U6") (pin "22") (pinfunction "CBUS1_22") (pintype "bidirectional"))
    )
    (net (code "146") (name "Net-(LED_TX1-PadA)") (class "Default")
      (node (ref "LED_TX1") (pin "A") (pinfunction "A_A") (pintype "passive"))
      (node (ref "R31") (pin "1") (pinfunction "1_1") (pintype "passive"))
    )
    (net (code "147") (name "Net-(QG1-OUT)") (class "Default")
      (node (ref "QG1") (pin "8") (pinfunction "OUT_8") (pintype "output"))
      (node (ref "U10") (pin "2") (pinfunction "FCKI_2") (pintype "bidirectional"))
      (node (ref "U7") (pin "2") (pinfunction "FCKI_2") (pintype "bidirectional"))
      (node (ref "U8") (pin "2") (pinfunction "FCKI_2") (pintype "bidirectional"))
      (node (ref "U9") (pin "2") (pinfunction "FCKI_2") (pintype "bidirectional"))
    )
    (net (code "148") (name "Net-(R11-Pad1)") (class "Default")
      (node (ref "R11") (pin "1") (pinfunction "1_1") (pintype "passive"))
      (node (ref "R12") (pin "2") (pinfunction "2_2") (pintype "passive"))
    )
    (net (code "149") (name "Net-(R13-Pad1)") (class "Default")
      (node (ref "R13") (pin "1") (pinfunction "1_1") (pintype "passive"))
      (node (ref "R14") (pin "2") (pinfunction "2_2") (pintype "passive"))
    )
    (net (code "150") (name "Net-(R15-Pad1)") (class "Default")
      (node (ref "R15") (pin "1") (pinfunction "1_1") (pintype "passive"))
      (node (ref "R16") (pin "2") (pinfunction "2_2") (pintype "passive"))
    )
    (net (code "151") (name "Net-(R32-Pad1)") (class "Default")
      (node (ref "R32") (pin "1") (pinfunction "1_1") (pintype "passive"))
      (node (ref "USB_PWR1") (pin "A") (pinfunction "A_A") (pintype "passive"))
    )
    (net (code "152") (name "Net-(SV2-Pad7)") (class "Default")
      (node (ref "SV2") (pin "7") (pinfunction "7_7") (pintype "passive"))
      (node (ref "SV2") (pin "8") (pinfunction "8_8") (pintype "passive"))
    )
    (net (code "153") (name "Net-(SV2-Pad10)") (class "Default")
      (node (ref "SV2") (pin "10") (pinfunction "10_10") (pintype "passive"))
      (node (ref "SV2") (pin "9") (pinfunction "9_9") (pintype "passive"))
    )
    (net (code "154") (name "Net-(SV2-Pad11)") (class "Default")
      (node (ref "SV2") (pin "11") (pinfunction "11_11") (pintype "passive"))
      (node (ref "SV2") (pin "12") (pinfunction "12_12") (pintype "passive"))
    )
    (net (code "155") (name "Net-(SV2-Pad15)") (class "Default")
      (node (ref "SV2") (pin "15") (pinfunction "15_15") (pintype "passive"))
      (node (ref "SV2") (pin "16") (pinfunction "16_16") (pintype "passive"))
    )
    (net (code "156") (name "Net-(SV2-Pad17)") (class "Default")
      (node (ref "SV2") (pin "17") (pinfunction "17_17") (pintype "passive"))
      (node (ref "SV2") (pin "18") (pinfunction "18_18") (pintype "passive"))
    )
    (net (code "157") (name "Net-(SV2-Pad21)") (class "Default")
      (node (ref "SV2") (pin "21") (pinfunction "21_21") (pintype "passive"))
      (node (ref "SV2") (pin "22") (pinfunction "22_22") (pintype "passive"))
    )
    (net (code "158") (name "Net-(SV2-Pad23)") (class "Default")
      (node (ref "SV2") (pin "23") (pinfunction "23_23") (pintype "passive"))
      (node (ref "SV2") (pin "24") (pinfunction "24_24") (pintype "passive"))
    )
    (net (code "159") (name "Net-(SV2-Pad25)") (class "Default")
      (node (ref "SV2") (pin "25") (pinfunction "25_25") (pintype "passive"))
      (node (ref "SV2") (pin "26") (pinfunction "26_26") (pintype "passive"))
    )
    (net (code "160") (name "Net-(SV2-Pad27)") (class "Default")
      (node (ref "SV2") (pin "27") (pinfunction "27_27") (pintype "passive"))
      (node (ref "SV2") (pin "28") (pinfunction "28_28") (pintype "passive"))
    )
    (net (code "161") (name "Net-(SV2-Pad31)") (class "Default")
      (node (ref "SV2") (pin "31") (pinfunction "31_31") (pintype "passive"))
      (node (ref "SV2") (pin "32") (pinfunction "32_32") (pintype "passive"))
    )
    (net (code "162") (name "Net-(SV2-Pad35)") (class "Default")
      (node (ref "SV2") (pin "35") (pinfunction "35_35") (pintype "passive"))
      (node (ref "SV2") (pin "36") (pinfunction "36_36") (pintype "passive"))
    )
    (net (code "163") (name "Net-(SV2-Pad37)") (class "Default")
      (node (ref "SV2") (pin "37") (pinfunction "37_37") (pintype "passive"))
      (node (ref "SV2") (pin "38") (pinfunction "38_38") (pintype "passive"))
    )
    (net (code "164") (name "Net-(SV2-Pad39)") (class "Default")
      (node (ref "SV2") (pin "39") (pinfunction "39_39") (pintype "passive"))
      (node (ref "SV2") (pin "40") (pinfunction "40_40") (pintype "passive"))
    )
    (net (code "165") (name "Net-(SV5-Pad1)") (class "Default")
      (node (ref "SV5") (pin "1") (pinfunction "1_1") (pintype "passive"))
      (node (ref "SV5") (pin "2") (pinfunction "2_2") (pintype "passive"))
    )
    (net (code "166") (name "Net-(SV5-Pad3)") (class "Default")
      (node (ref "SV5") (pin "3") (pinfunction "3_3") (pintype "passive"))
      (node (ref "SV5") (pin "4") (pinfunction "4_4") (pintype "passive"))
    )
    (net (code "167") (name "Net-(SV5-Pad5)") (class "Default")
      (node (ref "SV5") (pin "5") (pinfunction "5_5") (pintype "passive"))
      (node (ref "SV5") (pin "6") (pinfunction "6_6") (pintype "passive"))
    )
    (net (code "168") (name "Net-(SV5-Pad7)") (class "Default")
      (node (ref "SV5") (pin "7") (pinfunction "7_7") (pintype "passive"))
      (node (ref "SV5") (pin "8") (pinfunction "8_8") (pintype "passive"))
    )
    (net (code "169") (name "Net-(SV5-Pad11)") (class "Default")
      (node (ref "SV5") (pin "11") (pinfunction "11_11") (pintype "passive"))
      (node (ref "SV5") (pin "12") (pinfunction "12_12") (pintype "passive"))
    )
    (net (code "170") (name "Net-(SV5-Pad13)") (class "Default")
      (node (ref "SV5") (pin "13") (pinfunction "13_13") (pintype "passive"))
      (node (ref "SV5") (pin "14") (pinfunction "14_14") (pintype "passive"))
    )
    (net (code "171") (name "Net-(SV5-Pad15)") (class "Default")
      (node (ref "SV5") (pin "15") (pinfunction "15_15") (pintype "passive"))
      (node (ref "SV5") (pin "16") (pinfunction "16_16") (pintype "passive"))
    )
    (net (code "172") (name "Net-(SV5-Pad17)") (class "Default")
      (node (ref "SV5") (pin "17") (pinfunction "17_17") (pintype "passive"))
      (node (ref "SV5") (pin "18") (pinfunction "18_18") (pintype "passive"))
    )
    (net (code "173") (name "Net-(SV5-Pad19)") (class "Default")
      (node (ref "SV5") (pin "19") (pinfunction "19_19") (pintype "passive"))
      (node (ref "SV5") (pin "20") (pinfunction "20_20") (pintype "passive"))
    )
    (net (code "174") (name "Net-(SV5-Pad21)") (class "Default")
      (node (ref "SV5") (pin "21") (pinfunction "21_21") (pintype "passive"))
      (node (ref "SV5") (pin "22") (pinfunction "22_22") (pintype "passive"))
    )
    (net (code "175") (name "Net-(SV5-Pad23)") (class "Default")
      (node (ref "SV5") (pin "23") (pinfunction "23_23") (pintype "passive"))
      (node (ref "SV5") (pin "24") (pinfunction "24_24") (pintype "passive"))
    )
    (net (code "176") (name "Net-(SV5-Pad27)") (class "Default")
      (node (ref "SV5") (pin "27") (pinfunction "27_27") (pintype "passive"))
      (node (ref "SV5") (pin "28") (pinfunction "28_28") (pintype "passive"))
    )
    (net (code "177") (name "Net-(SV5-Pad29)") (class "Default")
      (node (ref "SV5") (pin "29") (pinfunction "29_29") (pintype "passive"))
      (node (ref "SV5") (pin "30") (pinfunction "30_30") (pintype "passive"))
    )
    (net (code "178") (name "Net-(SV5-Pad31)") (class "Default")
      (node (ref "SV5") (pin "31") (pinfunction "31_31") (pintype "passive"))
      (node (ref "SV5") (pin "32") (pinfunction "32_32") (pintype "passive"))
    )
    (net (code "179") (name "Net-(SV5-Pad33)") (class "Default")
      (node (ref "SV5") (pin "33") (pinfunction "33_33") (pintype "passive"))
      (node (ref "SV5") (pin "34") (pinfunction "34_34") (pintype "passive"))
    )
    (net (code "180") (name "Net-(SV5-Pad35)") (class "Default")
      (node (ref "SV5") (pin "35") (pinfunction "35_35") (pintype "passive"))
      (node (ref "SV5") (pin "36") (pinfunction "36_36") (pintype "passive"))
    )
    (net (code "181") (name "Net-(SV5-Pad37)") (class "Default")
      (node (ref "SV5") (pin "37") (pinfunction "37_37") (pintype "passive"))
      (node (ref "SV5") (pin "38") (pinfunction "38_38") (pintype "passive"))
    )
    (net (code "182") (name "Net-(SV7-Pad1)") (class "Default")
      (node (ref "SV7") (pin "1") (pinfunction "1_1") (pintype "passive"))
      (node (ref "SV7") (pin "2") (pinfunction "2_2") (pintype "passive"))
    )
    (net (code "183") (name "Net-(SV7-Pad3)") (class "Default")
      (node (ref "SV7") (pin "3") (pinfunction "3_3") (pintype "passive"))
      (node (ref "SV7") (pin "4") (pinfunction "4_4") (pintype "passive"))
    )
    (net (code "184") (name "Net-(SV7-Pad5)") (class "Default")
      (node (ref "SV7") (pin "5") (pinfunction "5_5") (pintype "passive"))
      (node (ref "SV7") (pin "6") (pinfunction "6_6") (pintype "passive"))
    )
    (net (code "185") (name "Net-(SV11-Pad5)") (class "Default")
      (node (ref "SV11") (pin "5") (pinfunction "5_5") (pintype "passive"))
      (node (ref "SV11") (pin "6") (pinfunction "6_6") (pintype "passive"))
    )
    (net (code "186") (name "Net-(SV12-Pad4)") (class "Default")
      (node (ref "SV12") (pin "4") (pinfunction "4_4") (pintype "passive"))
      (node (ref "SV8") (pin "4") (pinfunction "4_4") (pintype "passive"))
      (node (ref "SV9") (pin "4") (pinfunction "4_4") (pintype "passive"))
    )
    (net (code "187") (name "Net-(SV53-Pad1)") (class "Default")
      (node (ref "SV53") (pin "1") (pinfunction "1_1") (pintype "passive"))
      (node (ref "SV54") (pin "1") (pinfunction "1_1") (pintype "passive"))
      (node (ref "SV55") (pin "1") (pinfunction "1_1") (pintype "passive"))
    )
    (net (code "188") (name "Net-(SV53-Pad2)") (class "Default")
      (node (ref "SV53") (pin "2") (pinfunction "2_2") (pintype "passive"))
      (node (ref "SV54") (pin "2") (pinfunction "2_2") (pintype "passive"))
      (node (ref "SV55") (pin "2") (pinfunction "2_2") (pintype "passive"))
    )
    (net (code "189") (name "Net-(SV53-Pad3)") (class "Default")
      (node (ref "SV53") (pin "3") (pinfunction "3_3") (pintype "passive"))
      (node (ref "SV54") (pin "3") (pinfunction "3_3") (pintype "passive"))
      (node (ref "SV55") (pin "3") (pinfunction "3_3") (pintype "passive"))
    )
    (net (code "190") (name "Net-(SV53-Pad4)") (class "Default")
      (node (ref "SV53") (pin "4") (pinfunction "4_4") (pintype "passive"))
      (node (ref "SV54") (pin "4") (pinfunction "4_4") (pintype "passive"))
      (node (ref "SV55") (pin "4") (pinfunction "4_4") (pintype "passive"))
    )
    (net (code "191") (name "Net-(SV53-Pad5)") (class "Default")
      (node (ref "SV53") (pin "5") (pinfunction "5_5") (pintype "passive"))
      (node (ref "SV54") (pin "5") (pinfunction "5_5") (pintype "passive"))
      (node (ref "SV55") (pin "5") (pinfunction "5_5") (pintype "passive"))
    )
    (net (code "192") (name "Net-(SV53-Pad6)") (class "Default")
      (node (ref "SV53") (pin "6") (pinfunction "6_6") (pintype "passive"))
      (node (ref "SV54") (pin "6") (pinfunction "6_6") (pintype "passive"))
      (node (ref "SV55") (pin "6") (pinfunction "6_6") (pintype "passive"))
    )
    (net (code "193") (name "Net-(SV53-Pad7)") (class "Default")
      (node (ref "SV53") (pin "7") (pinfunction "7_7") (pintype "passive"))
      (node (ref "SV54") (pin "7") (pinfunction "7_7") (pintype "passive"))
      (node (ref "SV55") (pin "7") (pinfunction "7_7") (pintype "passive"))
    )
    (net (code "194") (name "Net-(SV53-Pad8)") (class "Default")
      (node (ref "SV53") (pin "8") (pinfunction "8_8") (pintype "passive"))
      (node (ref "SV54") (pin "8") (pinfunction "8_8") (pintype "passive"))
      (node (ref "SV55") (pin "8") (pinfunction "8_8") (pintype "passive"))
    )
    (net (code "195") (name "Net-(SV53-Pad9)") (class "Default")
      (node (ref "SV53") (pin "9") (pinfunction "9_9") (pintype "passive"))
      (node (ref "SV54") (pin "9") (pinfunction "9_9") (pintype "passive"))
      (node (ref "SV55") (pin "9") (pinfunction "9_9") (pintype "passive"))
    )
    (net (code "196") (name "Net-(SV53-Pad10)") (class "Default")
      (node (ref "SV53") (pin "10") (pinfunction "10_10") (pintype "passive"))
      (node (ref "SV54") (pin "10") (pinfunction "10_10") (pintype "passive"))
      (node (ref "SV55") (pin "10") (pinfunction "10_10") (pintype "passive"))
    )
    (net (code "197") (name "Net-(SV56-Pad1)") (class "Default")
      (node (ref "SV56") (pin "1") (pinfunction "1_1") (pintype "passive"))
      (node (ref "SV57") (pin "1") (pinfunction "1_1") (pintype "passive"))
      (node (ref "SV58") (pin "1") (pinfunction "1_1") (pintype "passive"))
    )
    (net (code "198") (name "Net-(SV56-Pad2)") (class "Default")
      (node (ref "SV56") (pin "2") (pinfunction "2_2") (pintype "passive"))
      (node (ref "SV57") (pin "2") (pinfunction "2_2") (pintype "passive"))
      (node (ref "SV58") (pin "2") (pinfunction "2_2") (pintype "passive"))
    )
    (net (code "199") (name "Net-(SV56-Pad3)") (class "Default")
      (node (ref "SV56") (pin "3") (pinfunction "3_3") (pintype "passive"))
      (node (ref "SV57") (pin "3") (pinfunction "3_3") (pintype "passive"))
      (node (ref "SV58") (pin "3") (pinfunction "3_3") (pintype "passive"))
    )
    (net (code "200") (name "Net-(SV56-Pad4)") (class "Default")
      (node (ref "SV56") (pin "4") (pinfunction "4_4") (pintype "passive"))
      (node (ref "SV57") (pin "4") (pinfunction "4_4") (pintype "passive"))
      (node (ref "SV58") (pin "4") (pinfunction "4_4") (pintype "passive"))
    )
    (net (code "201") (name "Net-(SV56-Pad5)") (class "Default")
      (node (ref "SV56") (pin "5") (pinfunction "5_5") (pintype "passive"))
      (node (ref "SV57") (pin "5") (pinfunction "5_5") (pintype "passive"))
      (node (ref "SV58") (pin "5") (pinfunction "5_5") (pintype "passive"))
    )
    (net (code "202") (name "Net-(SV56-Pad6)") (class "Default")
      (node (ref "SV56") (pin "6") (pinfunction "6_6") (pintype "passive"))
      (node (ref "SV57") (pin "6") (pinfunction "6_6") (pintype "passive"))
      (node (ref "SV58") (pin "6") (pinfunction "6_6") (pintype "passive"))
    )
    (net (code "203") (name "Net-(SV56-Pad7)") (class "Default")
      (node (ref "SV56") (pin "7") (pinfunction "7_7") (pintype "passive"))
      (node (ref "SV57") (pin "7") (pinfunction "7_7") (pintype "passive"))
      (node (ref "SV58") (pin "7") (pinfunction "7_7") (pintype "passive"))
    )
    (net (code "204") (name "Net-(SV56-Pad8)") (class "Default")
      (node (ref "SV56") (pin "8") (pinfunction "8_8") (pintype "passive"))
      (node (ref "SV57") (pin "8") (pinfunction "8_8") (pintype "passive"))
      (node (ref "SV58") (pin "8") (pinfunction "8_8") (pintype "passive"))
    )
    (net (code "205") (name "Net-(SV56-Pad9)") (class "Default")
      (node (ref "SV56") (pin "9") (pinfunction "9_9") (pintype "passive"))
      (node (ref "SV57") (pin "9") (pinfunction "9_9") (pintype "passive"))
      (node (ref "SV58") (pin "9") (pinfunction "9_9") (pintype "passive"))
    )
    (net (code "206") (name "Net-(SV56-Pad10)") (class "Default")
      (node (ref "SV56") (pin "10") (pinfunction "10_10") (pintype "passive"))
      (node (ref "SV57") (pin "10") (pinfunction "10_10") (pintype "passive"))
      (node (ref "SV58") (pin "10") (pinfunction "10_10") (pintype "passive"))
    )
    (net (code "207") (name "Net-(U$1-P3_SCLK)") (class "Default")
      (node (ref "J125") (pin "P$1") (pinfunction "P$1_P$1") (pintype "bidirectional"))
      (node (ref "J125") (pin "P$2") (pinfunction "P$2_P$2") (pintype "bidirectional"))
      (node (ref "J125") (pin "P$3") (pinfunction "P$3_P$3") (pintype "bidirectional"))
      (node (ref "U$1") (pin "3") (pinfunction "P3_SCLK_3") (pintype "bidirectional"))
    )
    (net (code "208") (name "Net-(U$1-P4_SDA{slash}SPIMOSI)") (class "Default")
      (node (ref "J126") (pin "P$1") (pinfunction "P$1_P$1") (pintype "bidirectional"))
      (node (ref "J126") (pin "P$2") (pinfunction "P$2_P$2") (pintype "bidirectional"))
      (node (ref "J126") (pin "P$3") (pinfunction "P$3_P$3") (pintype "bidirectional"))
      (node (ref "U$1") (pin "4") (pinfunction "P4_SDA/SPIMOSI_4") (pintype "bidirectional"))
    )
    (net (code "209") (name "Net-(U$1-P5_EDA{slash}AUX-DA)") (class "Default")
      (node (ref "J127") (pin "P$1") (pinfunction "P$1_P$1") (pintype "bidirectional"))
      (node (ref "J127") (pin "P$2") (pinfunction "P$2_P$2") (pintype "bidirectional"))
      (node (ref "J127") (pin "P$3") (pinfunction "P$3_P$3") (pintype "bidirectional"))
      (node (ref "U$1") (pin "5") (pinfunction "P5_EDA/AUX-DA_5") (pintype "bidirectional"))
    )
    (net (code "210") (name "Net-(U$1-P6_ECL{slash}AUX-CL)") (class "Default")
      (node (ref "J128") (pin "P$1") (pinfunction "P$1_P$1") (pintype "bidirectional"))
      (node (ref "J128") (pin "P$2") (pinfunction "P$2_P$2") (pintype "bidirectional"))
      (node (ref "J128") (pin "P$3") (pinfunction "P$3_P$3") (pintype "bidirectional"))
      (node (ref "U$1") (pin "6") (pinfunction "P6_ECL/AUX-CL_6") (pintype "bidirectional"))
    )
    (net (code "211") (name "Net-(U$1-P7_ADO{slash}SPIMISO)") (class "Default")
      (node (ref "J129") (pin "P$1") (pinfunction "P$1_P$1") (pintype "bidirectional"))
      (node (ref "J129") (pin "P$2") (pinfunction "P$2_P$2") (pintype "bidirectional"))
      (node (ref "J129") (pin "P$3") (pinfunction "P$3_P$3") (pintype "bidirectional"))
      (node (ref "U$1") (pin "7") (pinfunction "P7_ADO/SPIMISO_7") (pintype "bidirectional"))
    )
    (net (code "212") (name "Net-(U$1-P8_INT)") (class "Default")
      (node (ref "J130") (pin "P$1") (pinfunction "P$1_P$1") (pintype "bidirectional"))
      (node (ref "J130") (pin "P$2") (pinfunction "P$2_P$2") (pintype "bidirectional"))
      (node (ref "J130") (pin "P$3") (pinfunction "P$3_P$3") (pintype "bidirectional"))
      (node (ref "U$1") (pin "8") (pinfunction "P8_INT_8") (pintype "bidirectional"))
    )
    (net (code "213") (name "Net-(U$1-P9_NCS)") (class "Default")
      (node (ref "J131") (pin "P$1") (pinfunction "P$1_P$1") (pintype "bidirectional"))
      (node (ref "J131") (pin "P$2") (pinfunction "P$2_P$2") (pintype "bidirectional"))
      (node (ref "J131") (pin "P$3") (pinfunction "P$3_P$3") (pintype "bidirectional"))
      (node (ref "U$1") (pin "9") (pinfunction "P9_NCS_9") (pintype "bidirectional"))
    )
    (net (code "214") (name "Net-(U$1-P10_FSYNC)") (class "Default")
      (node (ref "J132") (pin "P$1") (pinfunction "P$1_P$1") (pintype "bidirectional"))
      (node (ref "J132") (pin "P$2") (pinfunction "P$2_P$2") (pintype "bidirectional"))
      (node (ref "J132") (pin "P$3") (pinfunction "P$3_P$3") (pintype "bidirectional"))
      (node (ref "U$1") (pin "10") (pinfunction "P10_FSYNC_10") (pintype "bidirectional"))
    )
    (net (code "215") (name "Net-(U2-C1+)") (class "Default")
      (node (ref "C8") (pin "1") (pinfunction "1_1") (pintype "passive"))
      (node (ref "U2") (pin "1") (pinfunction "C1+_1") (pintype "bidirectional"))
    )
    (net (code "216") (name "Net-(U2-C1-)") (class "Default")
      (node (ref "C8") (pin "2") (pinfunction "2_2") (pintype "passive"))
      (node (ref "U2") (pin "3") (pinfunction "C1-_3") (pintype "bidirectional"))
    )
    (net (code "217") (name "Net-(U2-C2+)") (class "Default")
      (node (ref "C9") (pin "1") (pinfunction "1_1") (pintype "passive"))
      (node (ref "U2") (pin "4") (pinfunction "C2+_4") (pintype "bidirectional"))
    )
    (net (code "218") (name "Net-(U2-C2-)") (class "Default")
      (node (ref "C9") (pin "2") (pinfunction "2_2") (pintype "passive"))
      (node (ref "U2") (pin "5") (pinfunction "C2-_5") (pintype "bidirectional"))
    )
    (net (code "219") (name "Net-(U2-DIN2)") (class "Default")
      (node (ref "SV1") (pin "7") (pinfunction "7_7") (pintype "passive"))
      (node (ref "SV1") (pin "8") (pinfunction "8_8") (pintype "passive"))
      (node (ref "U2") (pin "10") (pinfunction "DIN2_10") (pintype "bidirectional"))
    )
    (net (code "220") (name "Net-(U2-ROUT2)") (class "Default")
      (node (ref "SV1") (pin "10") (pinfunction "10_10") (pintype "passive"))
      (node (ref "SV1") (pin "9") (pinfunction "9_9") (pintype "passive"))
      (node (ref "U2") (pin "9") (pinfunction "ROUT2_9") (pintype "bidirectional"))
    )
    (net (code "221") (name "Net-(U2-V+)") (class "Default")
      (node (ref "C7") (pin "2") (pinfunction "2_2") (pintype "passive"))
      (node (ref "U2") (pin "2") (pinfunction "V+_2") (pintype "bidirectional"))
    )
    (net (code "222") (name "Net-(U2-V-)") (class "Default")
      (node (ref "C10") (pin "1") (pinfunction "1_1") (pintype "passive"))
      (node (ref "U2") (pin "6") (pinfunction "V-_6") (pintype "bidirectional"))
    )
    (net (code "223") (name "Net-(U3-~{HOLD})") (class "Default")
      (node (ref "R25") (pin "1") (pinfunction "1_1") (pintype "passive"))
      (node (ref "U3") (pin "7") (pinfunction "~{HOLD}_7") (pintype "bidirectional"))
    )
    (net (code "224") (name "Net-(U4-C1+)") (class "Default")
      (node (ref "C16") (pin "1") (pinfunction "1_1") (pintype "passive"))
      (node (ref "U4") (pin "1") (pinfunction "C1+_1") (pintype "bidirectional"))
    )
    (net (code "225") (name "Net-(U4-C1-)") (class "Default")
      (node (ref "C16") (pin "2") (pinfunction "2_2") (pintype "passive"))
      (node (ref "U4") (pin "3") (pinfunction "C1-_3") (pintype "bidirectional"))
    )
    (net (code "226") (name "Net-(U4-C2+)") (class "Default")
      (node (ref "C17") (pin "1") (pinfunction "1_1") (pintype "passive"))
      (node (ref "U4") (pin "4") (pinfunction "C2+_4") (pintype "bidirectional"))
    )
    (net (code "227") (name "Net-(U4-C2-)") (class "Default")
      (node (ref "C17") (pin "2") (pinfunction "2_2") (pintype "passive"))
      (node (ref "U4") (pin "5") (pinfunction "C2-_5") (pintype "bidirectional"))
    )
    (net (code "228") (name "Net-(U4-DIN1)") (class "Default")
      (node (ref "SV4") (pin "5") (pinfunction "5_5") (pintype "passive"))
      (node (ref "SV4") (pin "6") (pinfunction "6_6") (pintype "passive"))
      (node (ref "U4") (pin "11") (pinfunction "DIN1_11") (pintype "bidirectional"))
    )
    (net (code "229") (name "Net-(U4-DIN2)") (class "Default")
      (node (ref "SV4") (pin "7") (pinfunction "7_7") (pintype "passive"))
      (node (ref "SV4") (pin "8") (pinfunction "8_8") (pintype "passive"))
      (node (ref "U4") (pin "10") (pinfunction "DIN2_10") (pintype "bidirectional"))
    )
    (net (code "230") (name "Net-(U4-ROUT1)") (class "Default")
      (node (ref "SV4") (pin "3") (pinfunction "3_3") (pintype "passive"))
      (node (ref "SV4") (pin "4") (pinfunction "4_4") (pintype "passive"))
      (node (ref "U4") (pin "12") (pinfunction "ROUT1_12") (pintype "bidirectional"))
    )
    (net (code "231") (name "Net-(U4-ROUT2)") (class "Default")
      (node (ref "SV4") (pin "10") (pinfunction "10_10") (pintype "passive"))
      (node (ref "SV4") (pin "9") (pinfunction "9_9") (pintype "passive"))
      (node (ref "U4") (pin "9") (pinfunction "ROUT2_9") (pintype "bidirectional"))
    )
    (net (code "232") (name "Net-(U4-V+)") (class "Default")
      (node (ref "C15") (pin "2") (pinfunction "2_2") (pintype "passive"))
      (node (ref "U4") (pin "2") (pinfunction "V+_2") (pintype "bidirectional"))
    )
    (net (code "233") (name "Net-(U4-V-)") (class "Default")
      (node (ref "C18") (pin "1") (pinfunction "1_1") (pintype "passive"))
      (node (ref "U4") (pin "6") (pinfunction "V-_6") (pintype "bidirectional"))
    )
    (net (code "234") (name "Net-(U5-IN2)") (class "Default")
      (node (ref "SV14") (pin "2") (pinfunction "2_2") (pintype "passive"))
      (node (ref "U5") (pin "P$2") (pinfunction "IN2_P$2") (pintype "bidirectional"))
    )
    (net (code "235") (name "Net-(U5-IN3)") (class "Default")
      (node (ref "SV14") (pin "3") (pinfunction "3_3") (pintype "passive"))
      (node (ref "U5") (pin "P$3") (pinfunction "IN3_P$3") (pintype "bidirectional"))
    )
    (net (code "236") (name "Net-(U5-OUT1)") (class "Default")
      (node (ref "SV13") (pin "1") (pinfunction "1_1") (pintype "passive"))
      (node (ref "U5") (pin "P$7") (pinfunction "OUT1_P$7") (pintype "bidirectional"))
    )
    (net (code "237") (name "Net-(U5-OUT3)") (class "Default")
      (node (ref "SV13") (pin "3") (pinfunction "3_3") (pintype "passive"))
      (node (ref "U5") (pin "P$5") (pinfunction "OUT3_P$5") (pintype "bidirectional"))
    )
    (net (code "238") (name "Net-(U6-3V3OUT)") (class "Default")
      (node (ref "C26") (pin "1") (pinfunction "1_1") (pintype "passive"))
      (node (ref "U6") (pin "17") (pinfunction "3V3OUT_17") (pintype "output"))
      (node (ref "U6") (pin "4") (pinfunction "VCCIO_4") (pintype "power_in"))
    )
    (net (code "239") (name "Net-(U6-CBUS2)") (class "Default")
      (node (ref "SV20") (pin "3") (pinfunction "3_3") (pintype "passive"))
      (node (ref "U6") (pin "13") (pinfunction "CBUS2_13") (pintype "bidirectional"))
    )
    (net (code "240") (name "Net-(U6-CBUS3)") (class "Default")
      (node (ref "SV20") (pin "7") (pinfunction "7_7") (pintype "passive"))
      (node (ref "U6") (pin "14") (pinfunction "CBUS3_14") (pintype "bidirectional"))
    )
    (net (code "241") (name "Net-(U6-CBUS4)") (class "Default")
      (node (ref "SV20") (pin "9") (pinfunction "9_9") (pintype "passive"))
      (node (ref "U6") (pin "12") (pinfunction "CBUS4_12") (pintype "bidirectional"))
    )
    (net (code "242") (name "Net-(U6-CTS#)") (class "Default")
      (node (ref "SV20") (pin "4") (pinfunction "4_4") (pintype "passive"))
      (node (ref "U6") (pin "11") (pinfunction "CTS#_11") (pintype "input"))
    )
    (net (code "243") (name "Net-(U6-DSR#)") (class "Default")
      (node (ref "SV20") (pin "1") (pinfunction "1_1") (pintype "passive"))
      (node (ref "U6") (pin "9") (pinfunction "DSR#_9") (pintype "input"))
    )
    (net (code "244") (name "Net-(U6-DTR#)") (class "Default")
      (node (ref "SV20") (pin "2") (pinfunction "2_2") (pintype "passive"))
      (node (ref "U6") (pin "2") (pinfunction "DTR#_2") (pintype "output"))
    )
    (net (code "245") (name "Net-(U6-USBDM)") (class "Default")
      (node (ref "C24") (pin "1") (pinfunction "1_1") (pintype "passive"))
      (node (ref "U6") (pin "16") (pinfunction "USBDM_16") (pintype "bidirectional"))
      (node (ref "X2") (pin "D-") (pinfunction "D-_D-") (pintype "bidirectional"))
    )
    (net (code "246") (name "Net-(U6-USBDP)") (class "Default")
      (node (ref "C25") (pin "1") (pinfunction "1_1") (pintype "passive"))
      (node (ref "U6") (pin "15") (pinfunction "USBDP_15") (pintype "bidirectional"))
      (node (ref "X2") (pin "D+") (pinfunction "D+_D+") (pintype "bidirectional"))
    )
    (net (code "247") (name "Net-(U11-VDD)") (class "Default")
      (node (ref "C20") (pin "1") (pinfunction "1_1") (pintype "passive"))
      (node (ref "U11") (pin "1") (pinfunction "VDD_1") (pintype "bidirectional"))
    )
    (net (code "248") (name "Net-(U11-VDD2)") (class "Default")
      (node (ref "C19") (pin "1") (pinfunction "1_1") (pintype "passive"))
      (node (ref "U11") (pin "11") (pinfunction "VDD2_11") (pintype "bidirectional"))
    )
    (net (code "249") (name "Net-(U11-{slash}XRS)") (class "Default")
      (node (ref "P1") (pin "1") (pinfunction "1_1") (pintype "bidirectional"))
      (node (ref "R38") (pin "1") (pinfunction "1_1") (pintype "passive"))
      (node (ref "U11") (pin "17") (pinfunction "/XRS_17") (pintype "bidirectional"))
    )
    (net (code "250") (name "RESET") (class "Default")
      (node (ref "J98") (pin "P$1") (pinfunction "P$1_P$1") (pintype "bidirectional"))
      (node (ref "J98") (pin "P$2") (pinfunction "P$2_P$2") (pintype "bidirectional"))
      (node (ref "J98") (pin "P$3") (pinfunction "P$3_P$3") (pintype "bidirectional"))
      (node (ref "L1") (pin "P$16") (pinfunction "RST_P$16") (pintype "bidirectional"))
    )
    (net (code "251") (name "RESET_2") (class "Default")
      (node (ref "J157") (pin "P$1") (pinfunction "P$1_P$1") (pintype "bidirectional"))
      (node (ref "J157") (pin "P$2") (pinfunction "P$2_P$2") (pintype "bidirectional"))
      (node (ref "J157") (pin "P$3") (pinfunction "P$3_P$3") (pintype "bidirectional"))
      (node (ref "L1") (pin "P$56") (pinfunction "RST_2_P$56") (pintype "bidirectional"))
    )
    (net (code "252") (name "RTS_FT232RL") (class "Default")
      (node (ref "SV20") (pin "6") (pinfunction "6_6") (pintype "passive"))
      (node (ref "U6") (pin "3") (pinfunction "RTS#_3") (pintype "output"))
    )
    (net (code "253") (name "RXD_FT232RL") (class "Default")
      (node (ref "SV20") (pin "8") (pinfunction "8_8") (pintype "passive"))
      (node (ref "U6") (pin "5") (pinfunction "RXD_5") (pintype "input"))
    )
    (net (code "254") (name "SCK_5V") (class "Default")
      (node (ref "IC2") (pin "22") (pinfunction "A5_22") (pintype "bidirectional"))
      (node (ref "U10") (pin "5") (pinfunction "SCK_5") (pintype "bidirectional"))
      (node (ref "U7") (pin "5") (pinfunction "SCK_5") (pintype "bidirectional"))
      (node (ref "U8") (pin "5") (pinfunction "SCK_5") (pintype "bidirectional"))
      (node (ref "U9") (pin "5") (pinfunction "SCK_5") (pintype "bidirectional"))
    )
    (net (code "255") (name "SPI1_ENCA") (class "Default")
      (node (ref "SV23") (pin "5") (pinfunction "5_5") (pintype "passive"))
      (node (ref "U7") (pin "12") (pinfunction "A_12") (pintype "bidirectional"))
    )
    (net (code "256") (name "SPI1_ENCB") (class "Default")
      (node (ref "SV23") (pin "9") (pinfunction "9_9") (pintype "passive"))
      (node (ref "U7") (pin "11") (pinfunction "B_11") (pintype "bidirectional"))
    )
    (net (code "257") (name "SPI2_ENCA") (class "Default")
      (node (ref "SV23") (pin "6") (pinfunction "6_6") (pintype "passive"))
      (node (ref "U8") (pin "12") (pinfunction "A_12") (pintype "bidirectional"))
    )
    (net (code "258") (name "SPI2_ENCB") (class "Default")
      (node (ref "SV23") (pin "10") (pinfunction "10_10") (pintype "passive"))
      (node (ref "U8") (pin "11") (pinfunction "B_11") (pintype "bidirectional"))
    )
    (net (code "259") (name "SPI3_ENCA") (class "Default")
      (node (ref "SV24") (pin "5") (pinfunction "5_5") (pintype "passive"))
      (node (ref "U9") (pin "12") (pinfunction "A_12") (pintype "bidirectional"))
    )
    (net (code "260") (name "SPI3_ENCB") (class "Default")
      (node (ref "SV24") (pin "9") (pinfunction "9_9") (pintype "passive"))
      (node (ref "U9") (pin "11") (pinfunction "B_11") (pintype "bidirectional"))
    )
    (net (code "261") (name "SPI4_ENCA") (class "Default")
      (node (ref "SV24") (pin "6") (pinfunction "6_6") (pintype "passive"))
      (node (ref "U10") (pin "12") (pinfunction "A_12") (pintype "bidirectional"))
    )
    (net (code "262") (name "SPI4_ENCB") (class "Default")
      (node (ref "SV24") (pin "10") (pinfunction "10_10") (pintype "passive"))
      (node (ref "U10") (pin "11") (pinfunction "B_11") (pintype "bidirectional"))
    )
    (net (code "263") (name "SS1_5V") (class "Default")
      (node (ref "IC2") (pin "11") (pinfunction "A5_11") (pintype "bidirectional"))
      (node (ref "U7") (pin "4") (pinfunction "SS/_4") (pintype "bidirectional"))
    )
    (net (code "264") (name "SS2_5V") (class "Default")
      (node (ref "IC2") (pin "9") (pinfunction "A4_9") (pintype "bidirectional"))
      (node (ref "U8") (pin "4") (pinfunction "SS/_4") (pintype "bidirectional"))
    )
    (net (code "265") (name "SS3_5V") (class "Default")
      (node (ref "IC2") (pin "7") (pinfunction "A3_7") (pintype "bidirectional"))
      (node (ref "U9") (pin "4") (pinfunction "SS/_4") (pintype "bidirectional"))
    )
    (net (code "266") (name "SS4_5V") (class "Default")
      (node (ref "IC2") (pin "5") (pinfunction "A2_5") (pintype "bidirectional"))
      (node (ref "U10") (pin "4") (pinfunction "SS/_4") (pintype "bidirectional"))
    )
    (net (code "267") (name "TCK") (class "Default")
      (node (ref "SV15") (pin "11") (pinfunction "11_11") (pintype "passive"))
      (node (ref "SV15") (pin "9") (pinfunction "9_9") (pintype "passive"))
      (node (ref "U11") (pin "31") (pinfunction "GPIO38/XCLKIN(TCK)_31") (pintype "bidirectional"))
    )
    (net (code "268") (name "TDI") (class "Default")
      (node (ref "SV15") (pin "3") (pinfunction "3_3") (pintype "passive"))
      (node (ref "U11") (pin "28") (pinfunction "GPIO35(TDI)_28") (pintype "bidirectional"))
    )
    (net (code "269") (name "TDO") (class "Default")
      (node (ref "R8") (pin "2") (pinfunction "2_2") (pintype "passive"))
      (node (ref "SV15") (pin "7") (pinfunction "7_7") (pintype "passive"))
      (node (ref "U11") (pin "30") (pinfunction "GPIO37(TDO)_30") (pintype "bidirectional"))
    )
    (net (code "270") (name "TMS") (class "Default")
      (node (ref "SV15") (pin "1") (pinfunction "1_1") (pintype "passive"))
      (node (ref "U11") (pin "29") (pinfunction "GPIO36(TMS)_29") (pintype "bidirectional"))
    )
    (net (code "271") (name "TRSTN") (class "Default")
      (node (ref "R7") (pin "1") (pinfunction "1_1") (pintype "passive"))
      (node (ref "SV15") (pin "2") (pinfunction "2_2") (pintype "passive"))
      (node (ref "U11") (pin "16") (pinfunction "/TRST_16") (pintype "bidirectional"))
    )
    (net (code "272") (name "TXD_FT232RL") (class "Default")
      (node (ref "SV20") (pin "10") (pinfunction "10_10") (pintype "passive"))
      (node (ref "U6") (pin "1") (pinfunction "TXD_1") (pintype "output"))
    )
    (net (code "273") (name "UART00_RX") (class "Default")
      (node (ref "U2") (pin "13") (pinfunction "RIN1_13") (pintype "bidirectional"))
      (node (ref "X1") (pin "2") (pinfunction "2_2") (pintype "passive"))
    )
    (net (code "274") (name "UART00_TX") (class "Default")
      (node (ref "U2") (pin "14") (pinfunction "DOUT1_14") (pintype "bidirectional"))
      (node (ref "X1") (pin "3") (pinfunction "3_3") (pintype "passive"))
    )
    (net (code "275") (name "UART01_RX") (class "Default")
      (node (ref "SV6") (pin "1") (pinfunction "1_1") (pintype "passive"))
      (node (ref "U2") (pin "8") (pinfunction "RIN2_8") (pintype "bidirectional"))
    )
    (net (code "276") (name "UART01_TX") (class "Default")
      (node (ref "SV6") (pin "3") (pinfunction "3_3") (pintype "passive"))
      (node (ref "U2") (pin "7") (pinfunction "DOUT2_7") (pintype "bidirectional"))
    )
    (net (code "277") (name "UART02_RX") (class "Default")
      (node (ref "SV3") (pin "1") (pinfunction "1_1") (pintype "passive"))
      (node (ref "U4") (pin "13") (pinfunction "RIN1_13") (pintype "bidirectional"))
    )
    (net (code "278") (name "UART02_TX") (class "Default")
      (node (ref "SV3") (pin "3") (pinfunction "3_3") (pintype "passive"))
      (node (ref "U4") (pin "14") (pinfunction "DOUT1_14") (pintype "bidirectional"))
    )
    (net (code "279") (name "UART03_RX") (class "Default")
      (node (ref "SV3") (pin "10") (pinfunction "10_10") (pintype "passive"))
      (node (ref "U4") (pin "8") (pinfunction "RIN2_8") (pintype "bidirectional"))
    )
    (net (code "280") (name "UART03_TX") (class "Default")
      (node (ref "SV3") (pin "8") (pinfunction "8_8") (pintype "passive"))
      (node (ref "U4") (pin "7") (pinfunction "DOUT2_7") (pintype "bidirectional"))
    )
    (net (code "281") (name "USB_VCC") (class "Default")
      (node (ref "C28") (pin "1") (pinfunction "1_1") (pintype "passive"))
      (node (ref "C29") (pin "1") (pinfunction "1_1") (pintype "passive"))
      (node (ref "L2") (pin "2") (pinfunction "2_2") (pintype "passive"))
      (node (ref "R30") (pin "2") (pinfunction "2_2") (pintype "passive"))
      (node (ref "R31") (pin "2") (pinfunction "2_2") (pintype "passive"))
      (node (ref "R32") (pin "2") (pinfunction "2_2") (pintype "passive"))
      (node (ref "U6") (pin "20") (pinfunction "VCC_20") (pintype "power_in"))
    )
    (net (code "282") (name "unconnected-(ETH1-NC-PadP$9)") (class "Default")
      (node (ref "ETH1") (pin "P$9") (pinfunction "NC_P$9") (pintype "bidirectional"))
    )
    (net (code "283") (name "unconnected-(IC2A-A1-Pad3)") (class "Default")
      (node (ref "IC2") (pin "3") (pinfunction "A1_3") (pintype "bidirectional"))
    )
    (net (code "284") (name "unconnected-(IC2A-B1-Pad2)") (class "Default")
      (node (ref "IC2") (pin "2") (pinfunction "B1_2") (pintype "bidirectional"))
    )
    (net (code "285") (name "unconnected-(IC3-2.5V-Pad7)") (class "Default")
      (node (ref "IC3") (pin "7") (pinfunction "2.5V_7") (pintype "bidirectional"))
    )
    (net (code "286") (name "unconnected-(IC3-CMID-Pad4)") (class "Default")
      (node (ref "IC3") (pin "4") (pinfunction "CMID_4") (pintype "bidirectional"))
    )
    (net (code "287") (name "unconnected-(IC3-CP1-Pad19)") (class "Default")
      (node (ref "IC3") (pin "19") (pinfunction "CP1_19") (pintype "bidirectional"))
    )
    (net (code "288") (name "unconnected-(IC3-CP2-Pad20)") (class "Default")
      (node (ref "IC3") (pin "20") (pinfunction "CP2_20") (pintype "bidirectional"))
    )
    (net (code "289") (name "unconnected-(IC3-CP3-Pad17)") (class "Default")
      (node (ref "IC3") (pin "17") (pinfunction "CP3_17") (pintype "bidirectional"))
    )
    (net (code "290") (name "unconnected-(IC3-CP4-Pad18)") (class "Default")
      (node (ref "IC3") (pin "18") (pinfunction "CP4_18") (pintype "bidirectional"))
    )
    (net (code "291") (name "unconnected-(IC3-CP5-Pad14)") (class "Default")
      (node (ref "IC3") (pin "14") (pinfunction "CP5_14") (pintype "bidirectional"))
    )
    (net (code "292") (name "unconnected-(IC3-NC-Pad5)") (class "Default")
      (node (ref "IC3") (pin "5") (pinfunction "NC_5") (pintype "bidirectional"))
    )
    (net (code "293") (name "unconnected-(IC3-NC-Pad6)") (class "Default")
      (node (ref "IC3") (pin "6") (pinfunction "NC_6") (pintype "bidirectional"))
    )
    (net (code "294") (name "unconnected-(IC3-NC-Pad15)") (class "Default")
      (node (ref "IC3") (pin "15") (pinfunction "NC_15") (pintype "bidirectional"))
    )
    (net (code "295") (name "unconnected-(IC3-NC-Pad16)") (class "Default")
      (node (ref "IC3") (pin "16") (pinfunction "NC_16") (pintype "bidirectional"))
    )
    (net (code "296") (name "unconnected-(IC3-ST1-Pad11)") (class "Default")
      (node (ref "IC3") (pin "11") (pinfunction "ST1_11") (pintype "bidirectional"))
    )
    (net (code "297") (name "unconnected-(IC3-ST2-Pad10)") (class "Default")
      (node (ref "IC3") (pin "10") (pinfunction "ST2_10") (pintype "bidirectional"))
    )
    (net (code "298") (name "unconnected-(IC3-SUMJ-Pad3)") (class "Default")
      (node (ref "IC3") (pin "3") (pinfunction "SUMJ_3") (pintype "bidirectional"))
    )
    (net (code "299") (name "unconnected-(IC3-TEMP-Pad9)") (class "Default")
      (node (ref "IC3") (pin "9") (pinfunction "TEMP_9") (pintype "bidirectional"))
    )
    (net (code "300") (name "unconnected-(QG1-TS-Pad1)") (class "Default")
      (node (ref "QG1") (pin "1") (pinfunction "TS_1") (pintype "passive"))
    )
    (net (code "301") (name "unconnected-(R11-Pad2)") (class "Default")
      (node (ref "R11") (pin "2") (pinfunction "2_2") (pintype "passive"))
    )
    (net (code "302") (name "unconnected-(R13-Pad2)") (class "Default")
      (node (ref "R13") (pin "2") (pinfunction "2_2") (pintype "passive"))
    )
    (net (code "303") (name "unconnected-(R15-Pad2)") (class "Default")
      (node (ref "R15") (pin "2") (pinfunction "2_2") (pintype "passive"))
    )
    (net (code "304") (name "unconnected-(SV3-Pad2)") (class "Default")
      (node (ref "SV3") (pin "2") (pinfunction "2_2") (pintype "passive"))
    )
    (net (code "305") (name "unconnected-(SV3-Pad4)") (class "Default")
      (node (ref "SV3") (pin "4") (pinfunction "4_4") (pintype "passive"))
    )
    (net (code "306") (name "unconnected-(SV3-Pad7)") (class "Default")
      (node (ref "SV3") (pin "7") (pinfunction "7_7") (pintype "passive"))
    )
    (net (code "307") (name "unconnected-(SV3-Pad9)") (class "Default")
      (node (ref "SV3") (pin "9") (pinfunction "9_9") (pintype "passive"))
    )
    (net (code "308") (name "unconnected-(SV6-Pad2)") (class "Default")
      (node (ref "SV6") (pin "2") (pinfunction "2_2") (pintype "passive"))
    )
    (net (code "309") (name "unconnected-(SV6-Pad4)") (class "Default")
      (node (ref "SV6") (pin "4") (pinfunction "4_4") (pintype "passive"))
    )
    (net (code "310") (name "unconnected-(SV6-Pad6)") (class "Default")
      (node (ref "SV6") (pin "6") (pinfunction "6_6") (pintype "passive"))
    )
    (net (code "311") (name "unconnected-(SV6-Pad7)") (class "Default")
      (node (ref "SV6") (pin "7") (pinfunction "7_7") (pintype "passive"))
    )
    (net (code "312") (name "unconnected-(SV6-Pad8)") (class "Default")
      (node (ref "SV6") (pin "8") (pinfunction "8_8") (pintype "passive"))
    )
    (net (code "313") (name "unconnected-(SV6-Pad9)") (class "Default")
      (node (ref "SV6") (pin "9") (pinfunction "9_9") (pintype "passive"))
    )
    (net (code "314") (name "unconnected-(SV6-Pad10)") (class "Default")
      (node (ref "SV6") (pin "10") (pinfunction "10_10") (pintype "passive"))
    )
    (net (code "315") (name "unconnected-(SV10-Pad4)") (class "Default")
      (node (ref "SV10") (pin "4") (pinfunction "4_4") (pintype "passive"))
    )
    (net (code "316") (name "unconnected-(SV15-Pad6)") (class "Default")
      (node (ref "SV15") (pin "6") (pinfunction "6_6") (pintype "passive"))
    )
    (net (code "317") (name "unconnected-(SV15-Pad13)") (class "Default")
      (node (ref "SV15") (pin "13") (pinfunction "13_13") (pintype "passive"))
    )
    (net (code "318") (name "unconnected-(SV15-Pad14)") (class "Default")
      (node (ref "SV15") (pin "14") (pinfunction "14_14") (pintype "passive"))
    )
    (net (code "319") (name "unconnected-(SV18-Pad5)") (class "Default")
      (node (ref "SV18") (pin "5") (pinfunction "5_5") (pintype "passive"))
    )
    (net (code "320") (name "unconnected-(SV18-Pad6)") (class "Default")
      (node (ref "SV18") (pin "6") (pinfunction "6_6") (pintype "passive"))
    )
    (net (code "321") (name "unconnected-(SV18-Pad8)") (class "Default")
      (node (ref "SV18") (pin "8") (pinfunction "8_8") (pintype "passive"))
    )
    (net (code "322") (name "unconnected-(SV18-Pad10)") (class "Default")
      (node (ref "SV18") (pin "10") (pinfunction "10_10") (pintype "passive"))
    )
    (net (code "323") (name "unconnected-(SV20-Pad5)") (class "Default")
      (node (ref "SV20") (pin "5") (pinfunction "5_5") (pintype "passive"))
    )
    (net (code "324") (name "unconnected-(SV21-Pad3)") (class "Default")
      (node (ref "SV21") (pin "3") (pinfunction "3_3") (pintype "passive"))
    )
    (net (code "325") (name "unconnected-(SV21-Pad4)") (class "Default")
      (node (ref "SV21") (pin "4") (pinfunction "4_4") (pintype "passive"))
    )
    (net (code "326") (name "unconnected-(SV23-Pad3)") (class "Default")
      (node (ref "SV23") (pin "3") (pinfunction "3_3") (pintype "passive"))
    )
    (net (code "327") (name "unconnected-(SV23-Pad4)") (class "Default")
      (node (ref "SV23") (pin "4") (pinfunction "4_4") (pintype "passive"))
    )
    (net (code "328") (name "unconnected-(SV24-Pad3)") (class "Default")
      (node (ref "SV24") (pin "3") (pinfunction "3_3") (pintype "passive"))
    )
    (net (code "329") (name "unconnected-(SV24-Pad4)") (class "Default")
      (node (ref "SV24") (pin "4") (pinfunction "4_4") (pintype "passive"))
    )
    (net (code "330") (name "unconnected-(SV26-Pad6)") (class "Default")
      (node (ref "SV26") (pin "6") (pinfunction "6_6") (pintype "passive"))
    )
    (net (code "331") (name "unconnected-(SV26-Pad8)") (class "Default")
      (node (ref "SV26") (pin "8") (pinfunction "8_8") (pintype "passive"))
    )
    (net (code "332") (name "unconnected-(SV26-Pad10)") (class "Default")
      (node (ref "SV26") (pin "10") (pinfunction "10_10") (pintype "passive"))
    )
    (net (code "333") (name "unconnected-(SV28-Pad1)") (class "Default")
      (node (ref "SV28") (pin "1") (pinfunction "1_1") (pintype "passive"))
    )
    (net (code "334") (name "unconnected-(SV28-Pad3)") (class "Default")
      (node (ref "SV28") (pin "3") (pinfunction "3_3") (pintype "passive"))
    )
    (net (code "335") (name "unconnected-(SV28-Pad4)") (class "Default")
      (node (ref "SV28") (pin "4") (pinfunction "4_4") (pintype "passive"))
    )
    (net (code "336") (name "unconnected-(SV28-Pad5)") (class "Default")
      (node (ref "SV28") (pin "5") (pinfunction "5_5") (pintype "passive"))
    )
    (net (code "337") (name "unconnected-(SV28-Pad7)") (class "Default")
      (node (ref "SV28") (pin "7") (pinfunction "7_7") (pintype "passive"))
    )
    (net (code "338") (name "unconnected-(SV28-Pad9)") (class "Default")
      (node (ref "SV28") (pin "9") (pinfunction "9_9") (pintype "passive"))
    )
    (net (code "339") (name "unconnected-(SV30-Pad4)") (class "Default")
      (node (ref "SV30") (pin "4") (pinfunction "4_4") (pintype "passive"))
    )
    (net (code "340") (name "unconnected-(U3-DNU-Pad3)") (class "Default")
      (node (ref "U3") (pin "3") (pinfunction "DNU_3") (pintype "bidirectional"))
    )
    (net (code "341") (name "unconnected-(U6-DCD#-Pad10)") (class "Default")
      (node (ref "U6") (pin "10") (pinfunction "DCD#_10") (pintype "input"))
    )
    (net (code "342") (name "unconnected-(U6-OSCI-Pad27)") (class "Default")
      (node (ref "U6") (pin "27") (pinfunction "OSCI_27") (pintype "input"))
    )
    (net (code "343") (name "unconnected-(U6-OSCO-Pad28)") (class "Default")
      (node (ref "U6") (pin "28") (pinfunction "OSCO_28") (pintype "output"))
    )
    (net (code "344") (name "unconnected-(U6-RESET#-Pad19)") (class "Default")
      (node (ref "U6") (pin "19") (pinfunction "RESET#_19") (pintype "input"))
    )
    (net (code "345") (name "unconnected-(U6-RI#-Pad6)") (class "Default")
      (node (ref "U6") (pin "6") (pinfunction "RI#_6") (pintype "input"))
    )
    (net (code "346") (name "unconnected-(U7-CNT_EN-Pad13)") (class "Default")
      (node (ref "U7") (pin "13") (pinfunction "CNT_EN_13") (pintype "bidirectional"))
    )
    (net (code "347") (name "unconnected-(U7-DFLAG{slash}-Pad9)") (class "Default")
      (node (ref "U7") (pin "9") (pinfunction "DFLAG/_9") (pintype "bidirectional"))
    )
    (net (code "348") (name "unconnected-(U7-FCKO-Pad1)") (class "Default")
      (node (ref "U7") (pin "1") (pinfunction "FCKO_1") (pintype "bidirectional"))
    )
    (net (code "349") (name "unconnected-(U7-INDEX{slash}-Pad10)") (class "Default")
      (node (ref "U7") (pin "10") (pinfunction "INDEX/_10") (pintype "bidirectional"))
    )
    (net (code "350") (name "unconnected-(U7-LFLAG{slash}-Pad8)") (class "Default")
      (node (ref "U7") (pin "8") (pinfunction "LFLAG/_8") (pintype "bidirectional"))
    )
    (net (code "351") (name "unconnected-(U8-CNT_EN-Pad13)") (class "Default")
      (node (ref "U8") (pin "13") (pinfunction "CNT_EN_13") (pintype "bidirectional"))
    )
    (net (code "352") (name "unconnected-(U8-DFLAG{slash}-Pad9)") (class "Default")
      (node (ref "U8") (pin "9") (pinfunction "DFLAG/_9") (pintype "bidirectional"))
    )
    (net (code "353") (name "unconnected-(U8-FCKO-Pad1)") (class "Default")
      (node (ref "U8") (pin "1") (pinfunction "FCKO_1") (pintype "bidirectional"))
    )
    (net (code "354") (name "unconnected-(U8-INDEX{slash}-Pad10)") (class "Default")
      (node (ref "U8") (pin "10") (pinfunction "INDEX/_10") (pintype "bidirectional"))
    )
    (net (code "355") (name "unconnected-(U8-LFLAG{slash}-Pad8)") (class "Default")
      (node (ref "U8") (pin "8") (pinfunction "LFLAG/_8") (pintype "bidirectional"))
    )
    (net (code "356") (name "unconnected-(U9-CNT_EN-Pad13)") (class "Default")
      (node (ref "U9") (pin "13") (pinfunction "CNT_EN_13") (pintype "bidirectional"))
    )
    (net (code "357") (name "unconnected-(U9-DFLAG{slash}-Pad9)") (class "Default")
      (node (ref "U9") (pin "9") (pinfunction "DFLAG/_9") (pintype "bidirectional"))
    )
    (net (code "358") (name "unconnected-(U9-FCKO-Pad1)") (class "Default")
      (node (ref "U9") (pin "1") (pinfunction "FCKO_1") (pintype "bidirectional"))
    )
    (net (code "359") (name "unconnected-(U9-INDEX{slash}-Pad10)") (class "Default")
      (node (ref "U9") (pin "10") (pinfunction "INDEX/_10") (pintype "bidirectional"))
    )
    (net (code "360") (name "unconnected-(U9-LFLAG{slash}-Pad8)") (class "Default")
      (node (ref "U9") (pin "8") (pinfunction "LFLAG/_8") (pintype "bidirectional"))
    )
    (net (code "361") (name "unconnected-(U10-CNT_EN-Pad13)") (class "Default")
      (node (ref "U10") (pin "13") (pinfunction "CNT_EN_13") (pintype "bidirectional"))
    )
    (net (code "362") (name "unconnected-(U10-DFLAG{slash}-Pad9)") (class "Default")
      (node (ref "U10") (pin "9") (pinfunction "DFLAG/_9") (pintype "bidirectional"))
    )
    (net (code "363") (name "unconnected-(U10-FCKO-Pad1)") (class "Default")
      (node (ref "U10") (pin "1") (pinfunction "FCKO_1") (pintype "bidirectional"))
    )
    (net (code "364") (name "unconnected-(U10-INDEX{slash}-Pad10)") (class "Default")
      (node (ref "U10") (pin "10") (pinfunction "INDEX/_10") (pintype "bidirectional"))
    )
    (net (code "365") (name "unconnected-(U10-LFLAG{slash}-Pad8)") (class "Default")
      (node (ref "U10") (pin "8") (pinfunction "LFLAG/_8") (pintype "bidirectional"))
    )
    (net (code "366") (name "unconnected-(U11-TEST-Pad38)") (class "Default")
      (node (ref "U11") (pin "38") (pinfunction "TEST_38") (pintype "bidirectional"))
    )
    (net (code "367") (name "unconnected-(U15-P1_VIN-PadP$1)") (class "Default")
      (node (ref "U15") (pin "P$1") (pinfunction "P1_VIN_P$1") (pintype "bidirectional"))
    )
    (net (code "368") (name "unconnected-(U15-P6_VREF-PadP$6)") (class "Default")
      (node (ref "U15") (pin "P$6") (pinfunction "P6_VREF_P$6") (pintype "bidirectional"))
    )
    (net (code "369") (name "unconnected-(U15-P9_PWR_DOWN-PadP$9)") (class "Default")
      (node (ref "U15") (pin "P$9") (pinfunction "P9_PWR_DOWN_P$9") (pintype "bidirectional"))
    )
    (net (code "370") (name "unconnected-(U15-P10_SELFTEST-PadP$10)") (class "Default")
      (node (ref "U15") (pin "P$10") (pinfunction "P10_SELFTEST_P$10") (pintype "bidirectional"))
    )
    (net (code "371") (name "unconnected-(U15-P12_HIGHPASS_RST-PadP$12)") (class "Default")
      (node (ref "U15") (pin "P$12") (pinfunction "P12_HIGHPASS_RST_P$12") (pintype "bidirectional"))
    )
    (net (code "372") (name "unconnected-(X1-Pad1)") (class "Default")
      (node (ref "X1") (pin "1") (pinfunction "1_1") (pintype "passive"))
    )
    (net (code "373") (name "unconnected-(X1-Pad4)") (class "Default")
      (node (ref "X1") (pin "4") (pinfunction "4_4") (pintype "passive"))
    )
    (net (code "374") (name "unconnected-(X1-Pad6)") (class "Default")
      (node (ref "X1") (pin "6") (pinfunction "6_6") (pintype "passive"))
    )
    (net (code "375") (name "unconnected-(X1-Pad7)") (class "Default")
      (node (ref "X1") (pin "7") (pinfunction "7_7") (pintype "passive"))
    )
    (net (code "376") (name "unconnected-(X1-Pad8)") (class "Default")
      (node (ref "X1") (pin "8") (pinfunction "8_8") (pintype "passive"))
    )
    (net (code "377") (name "unconnected-(X1-Pad9)") (class "Default")
      (node (ref "X1") (pin "9") (pinfunction "9_9") (pintype "passive"))
    )
  )
)
